# soundcard_v1_1.net
KiCad netlist of a schematic drawn in EAGLE
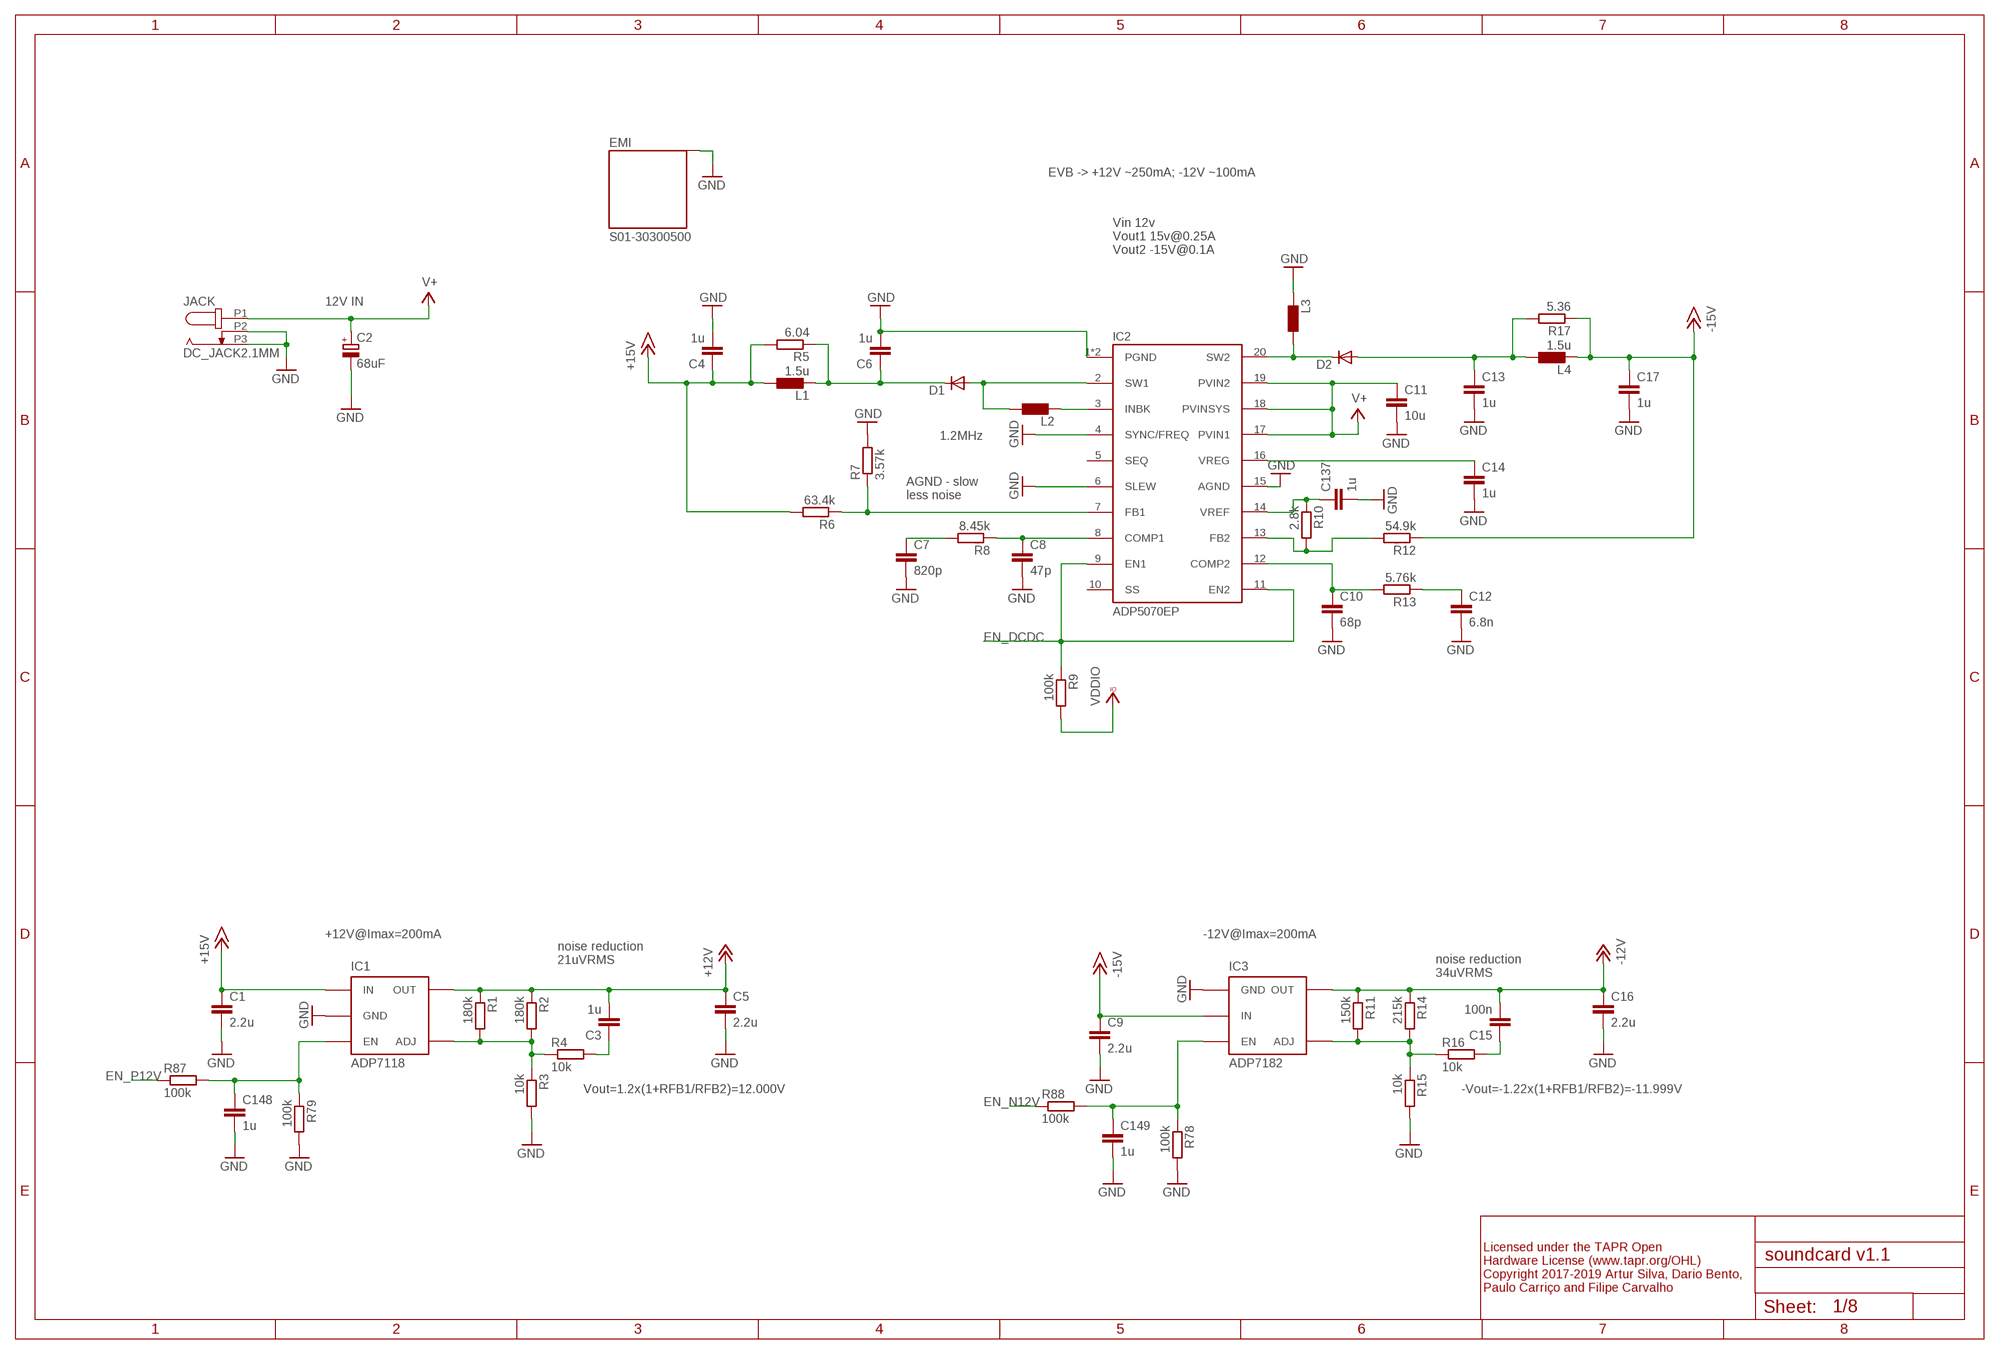
[diagram p0: schematic, sheet 1]
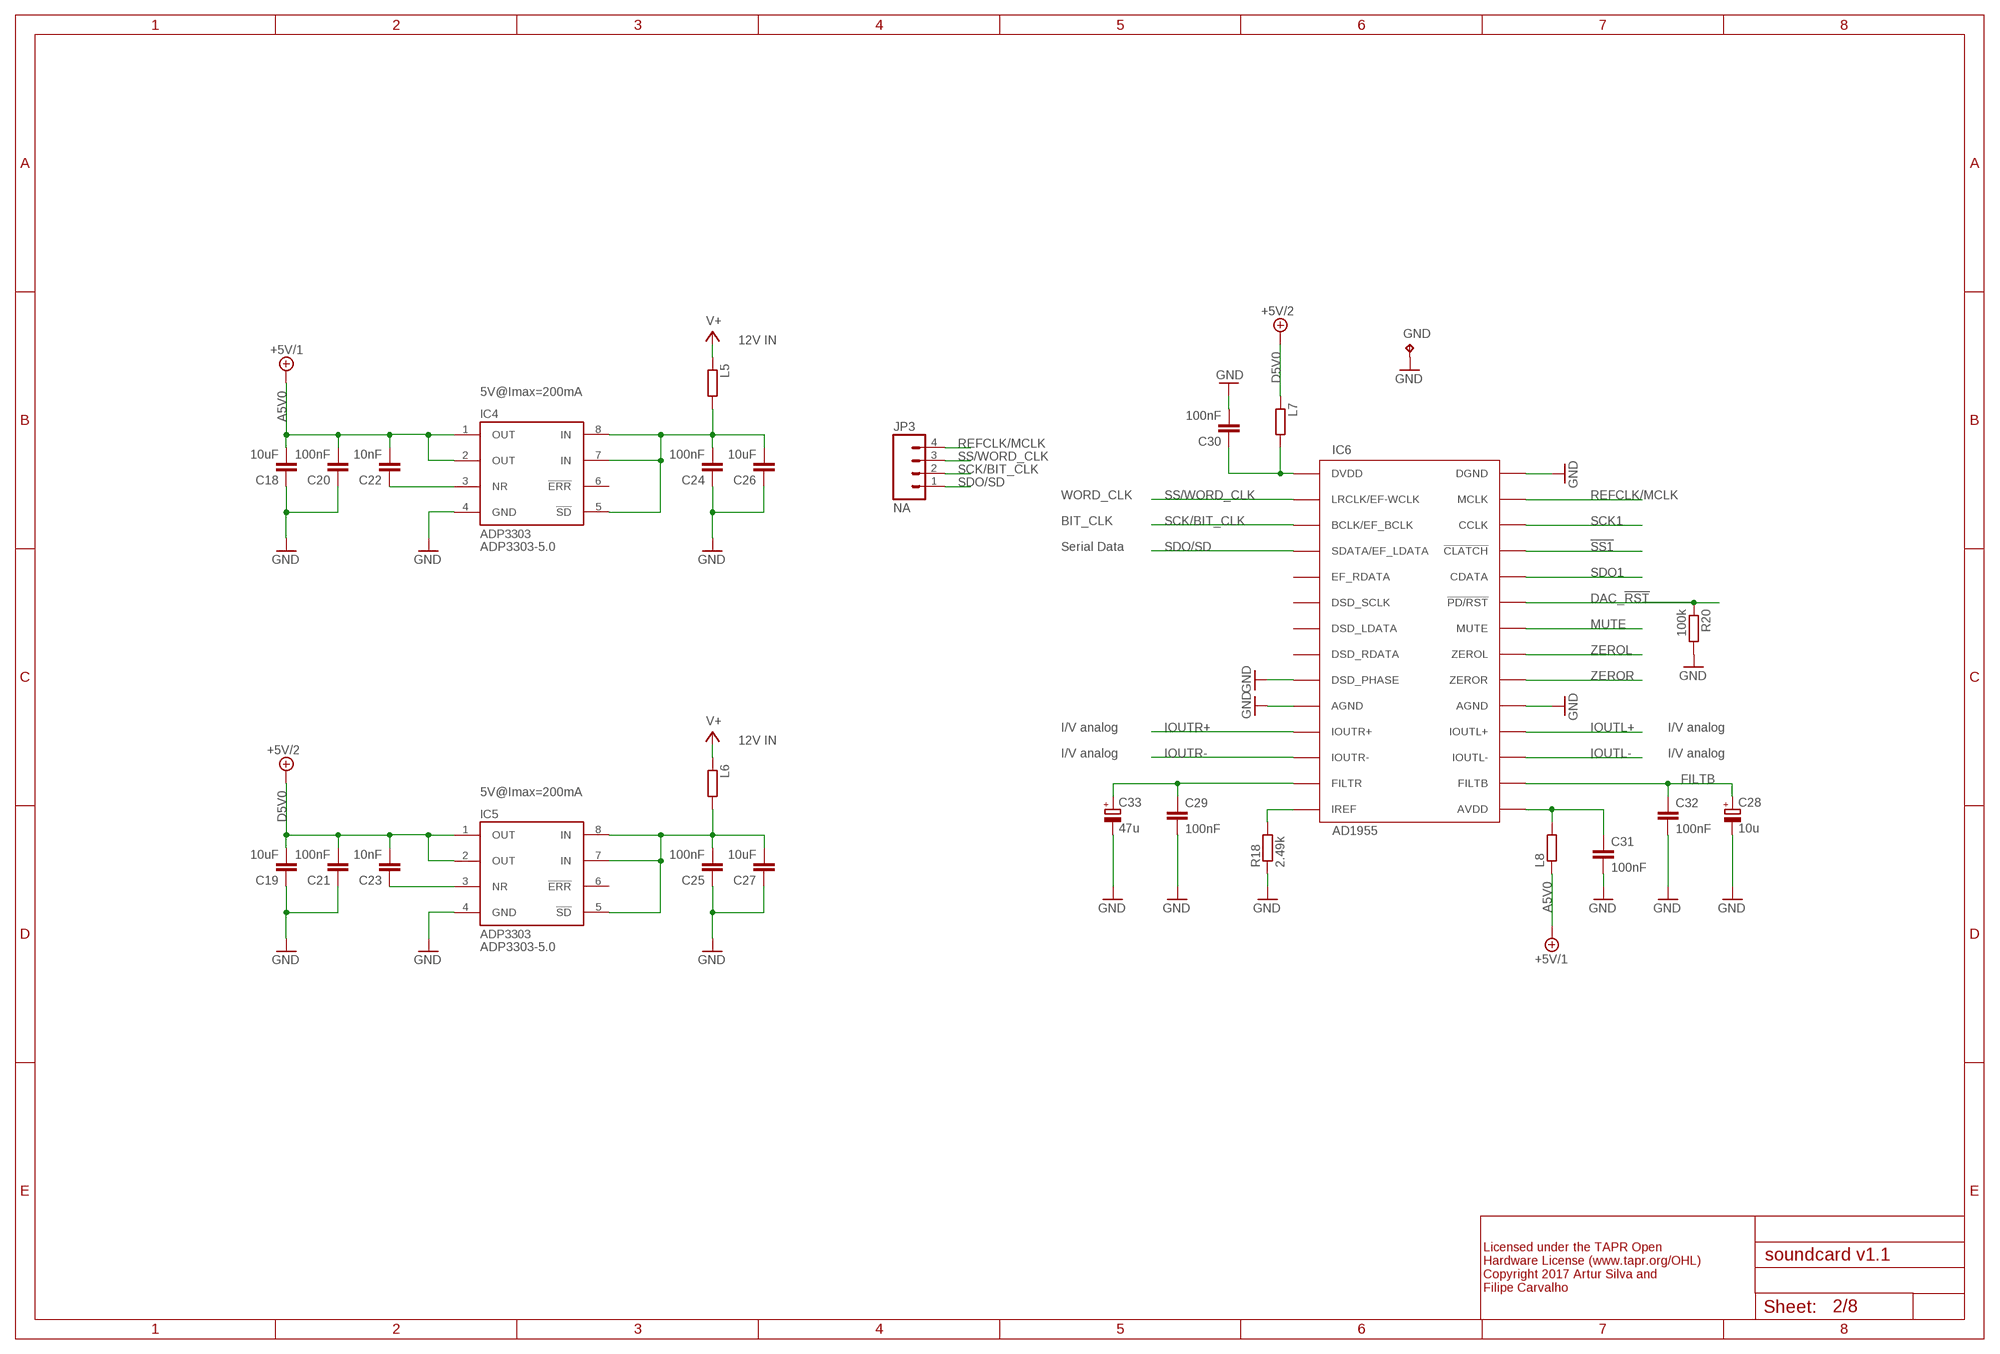
[diagram p1: schematic, sheet 2]
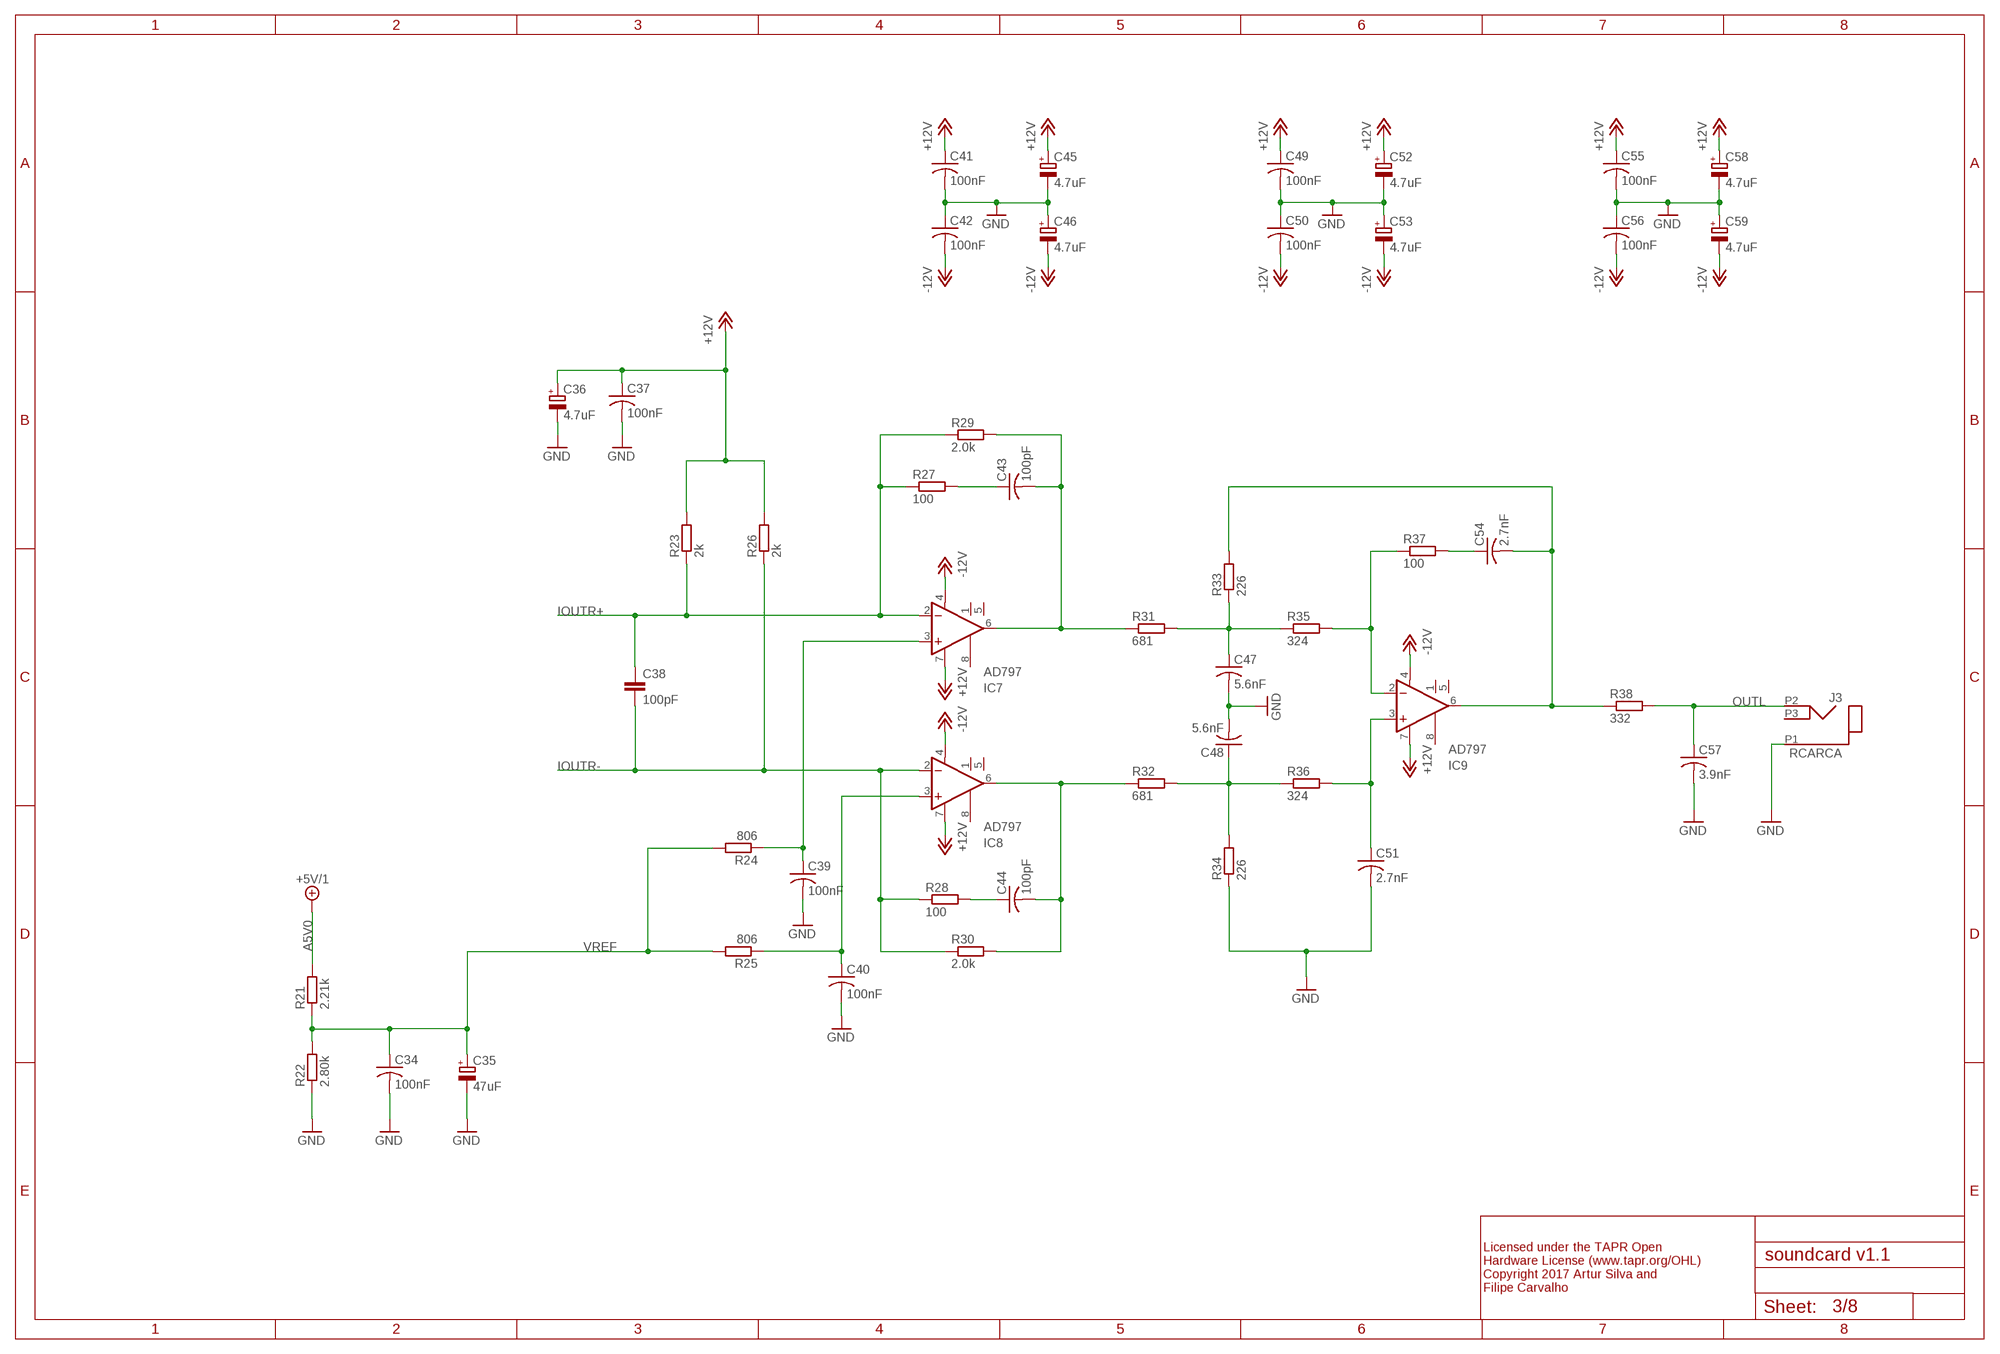
[diagram p2: schematic, sheet 3]
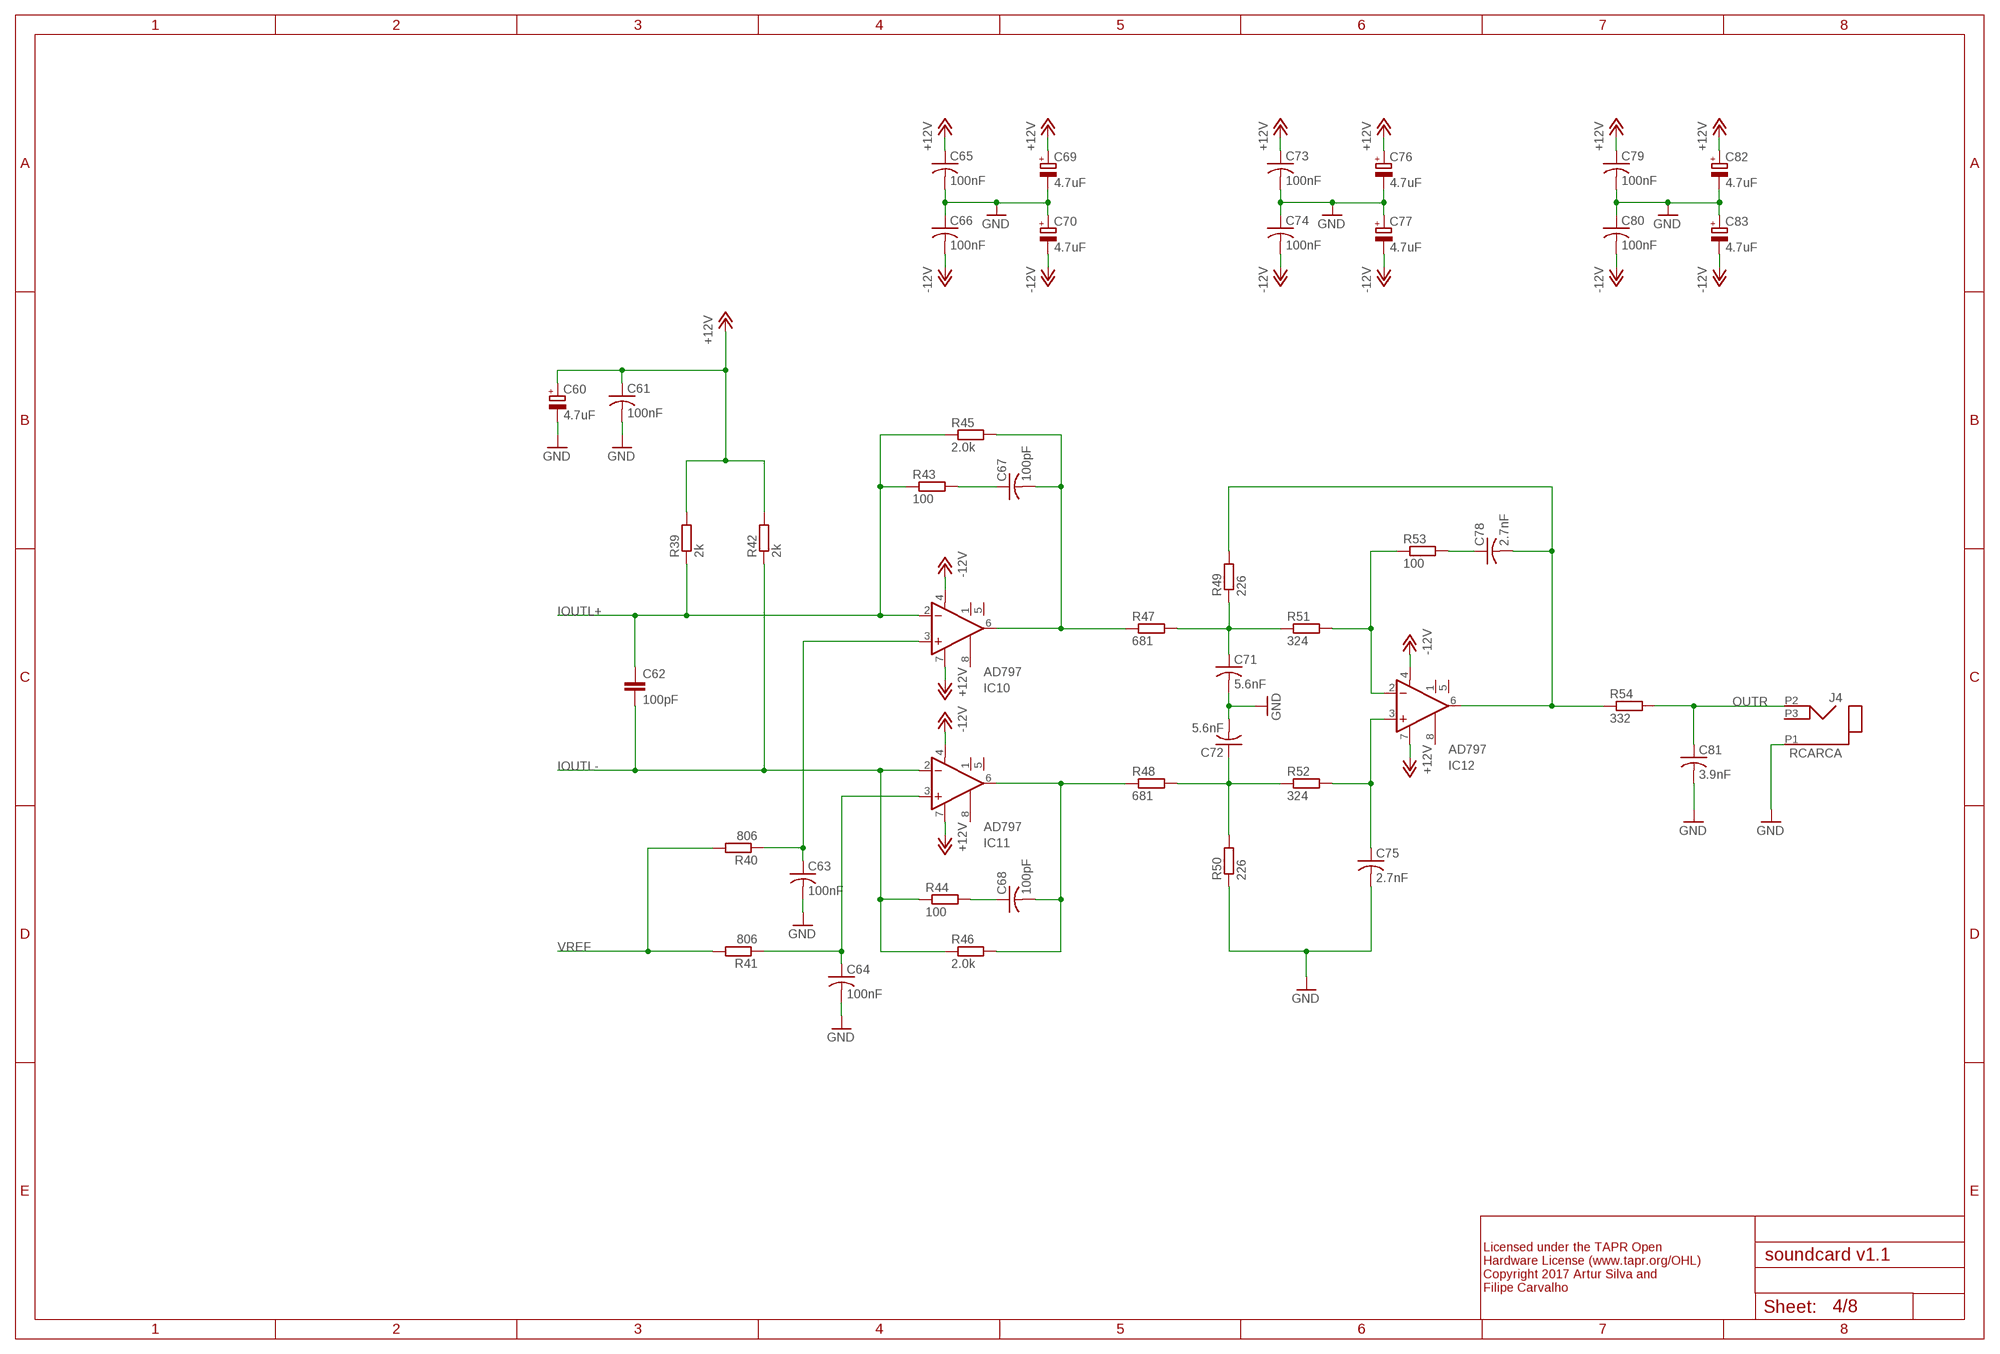
[diagram p3: schematic, sheet 4]
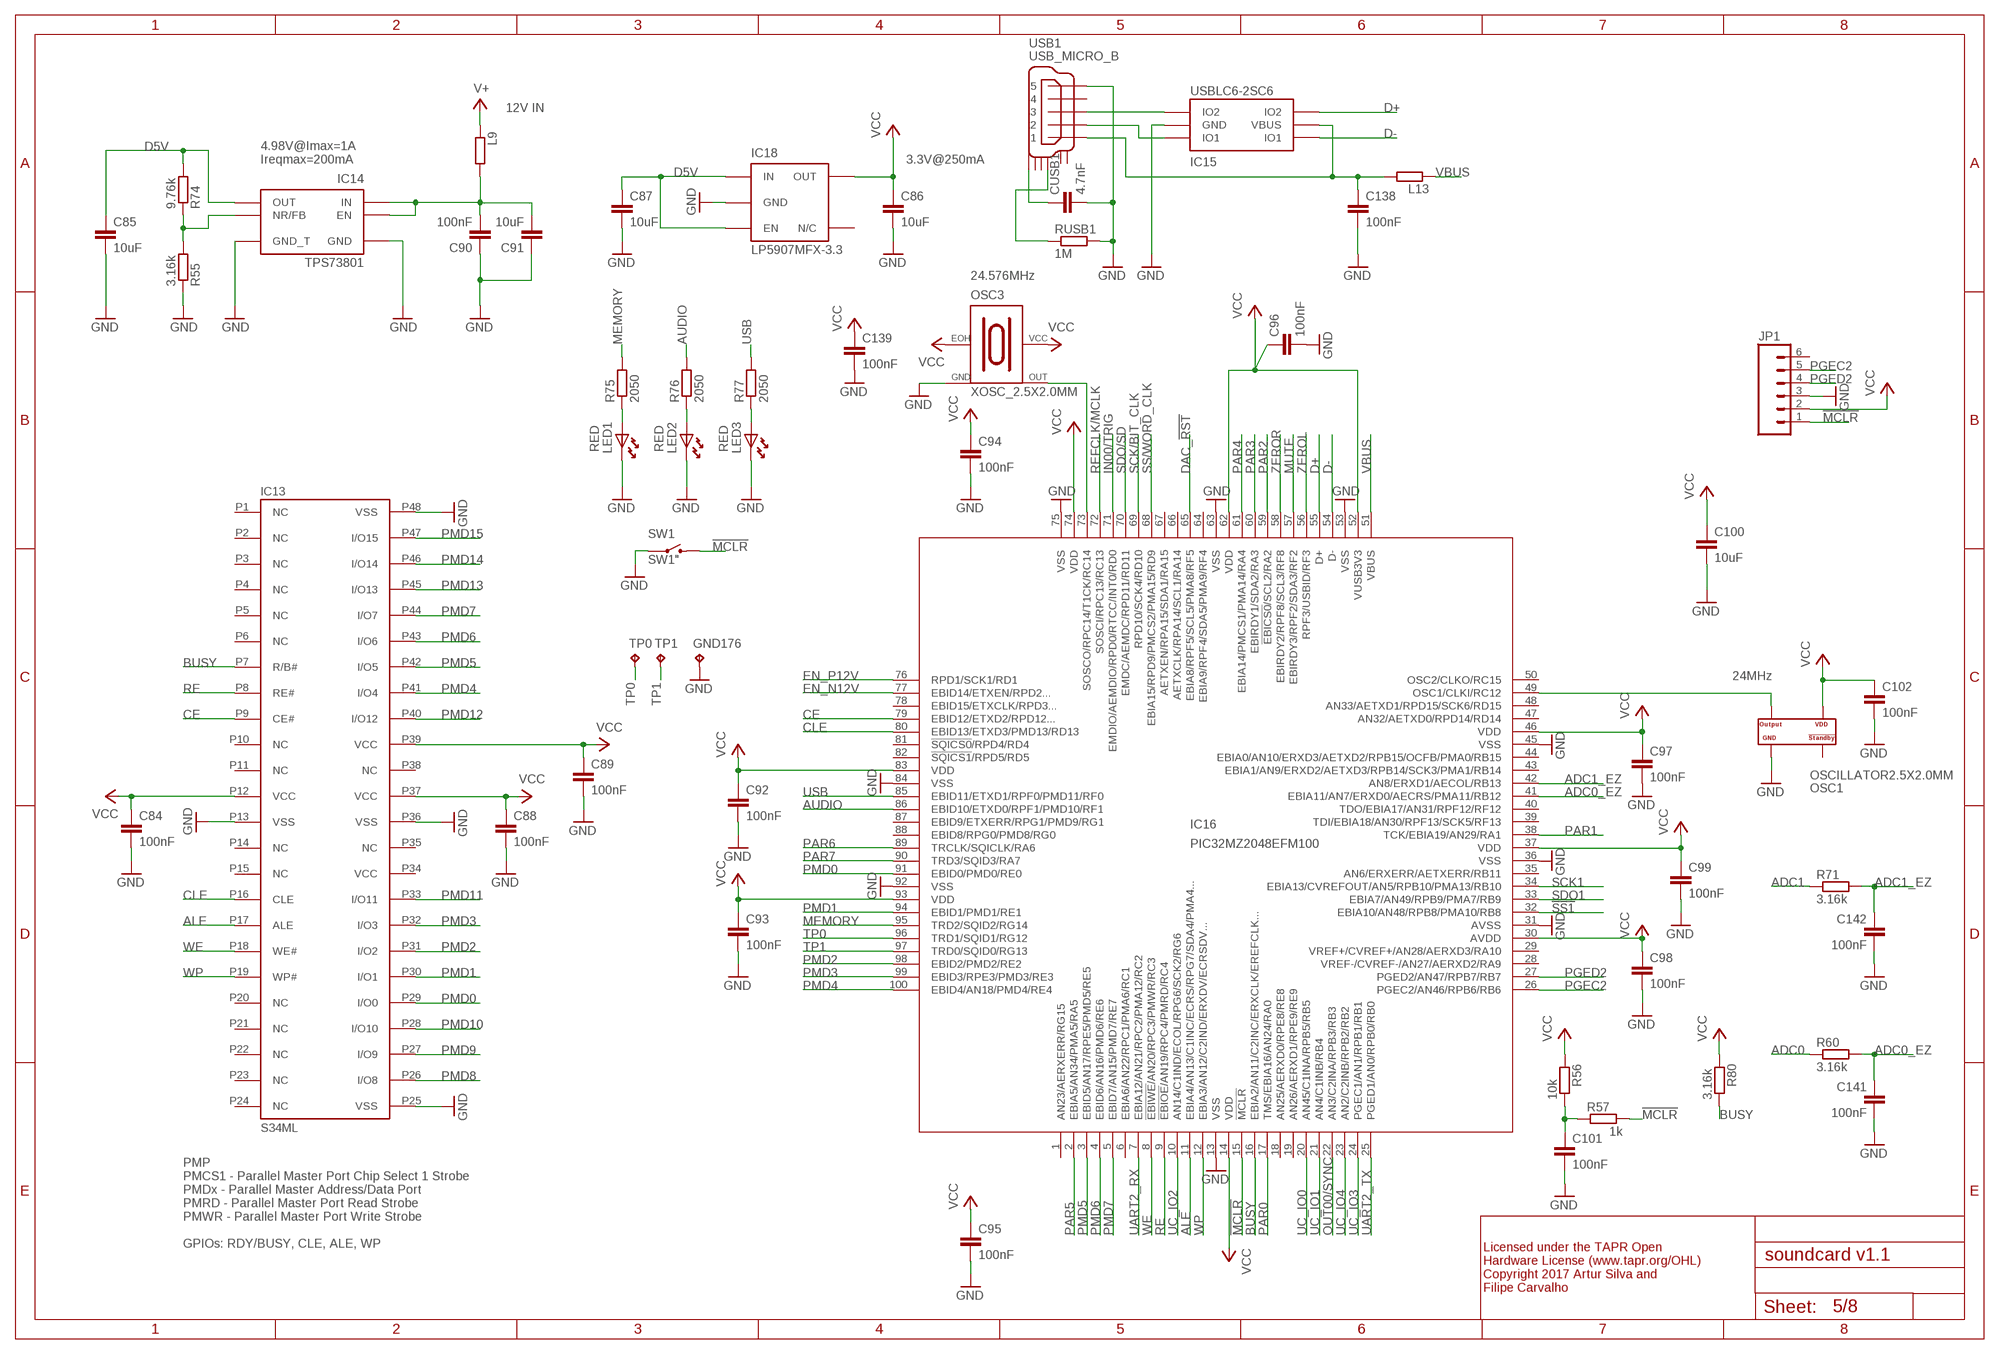
[diagram p4: schematic, sheet 5]
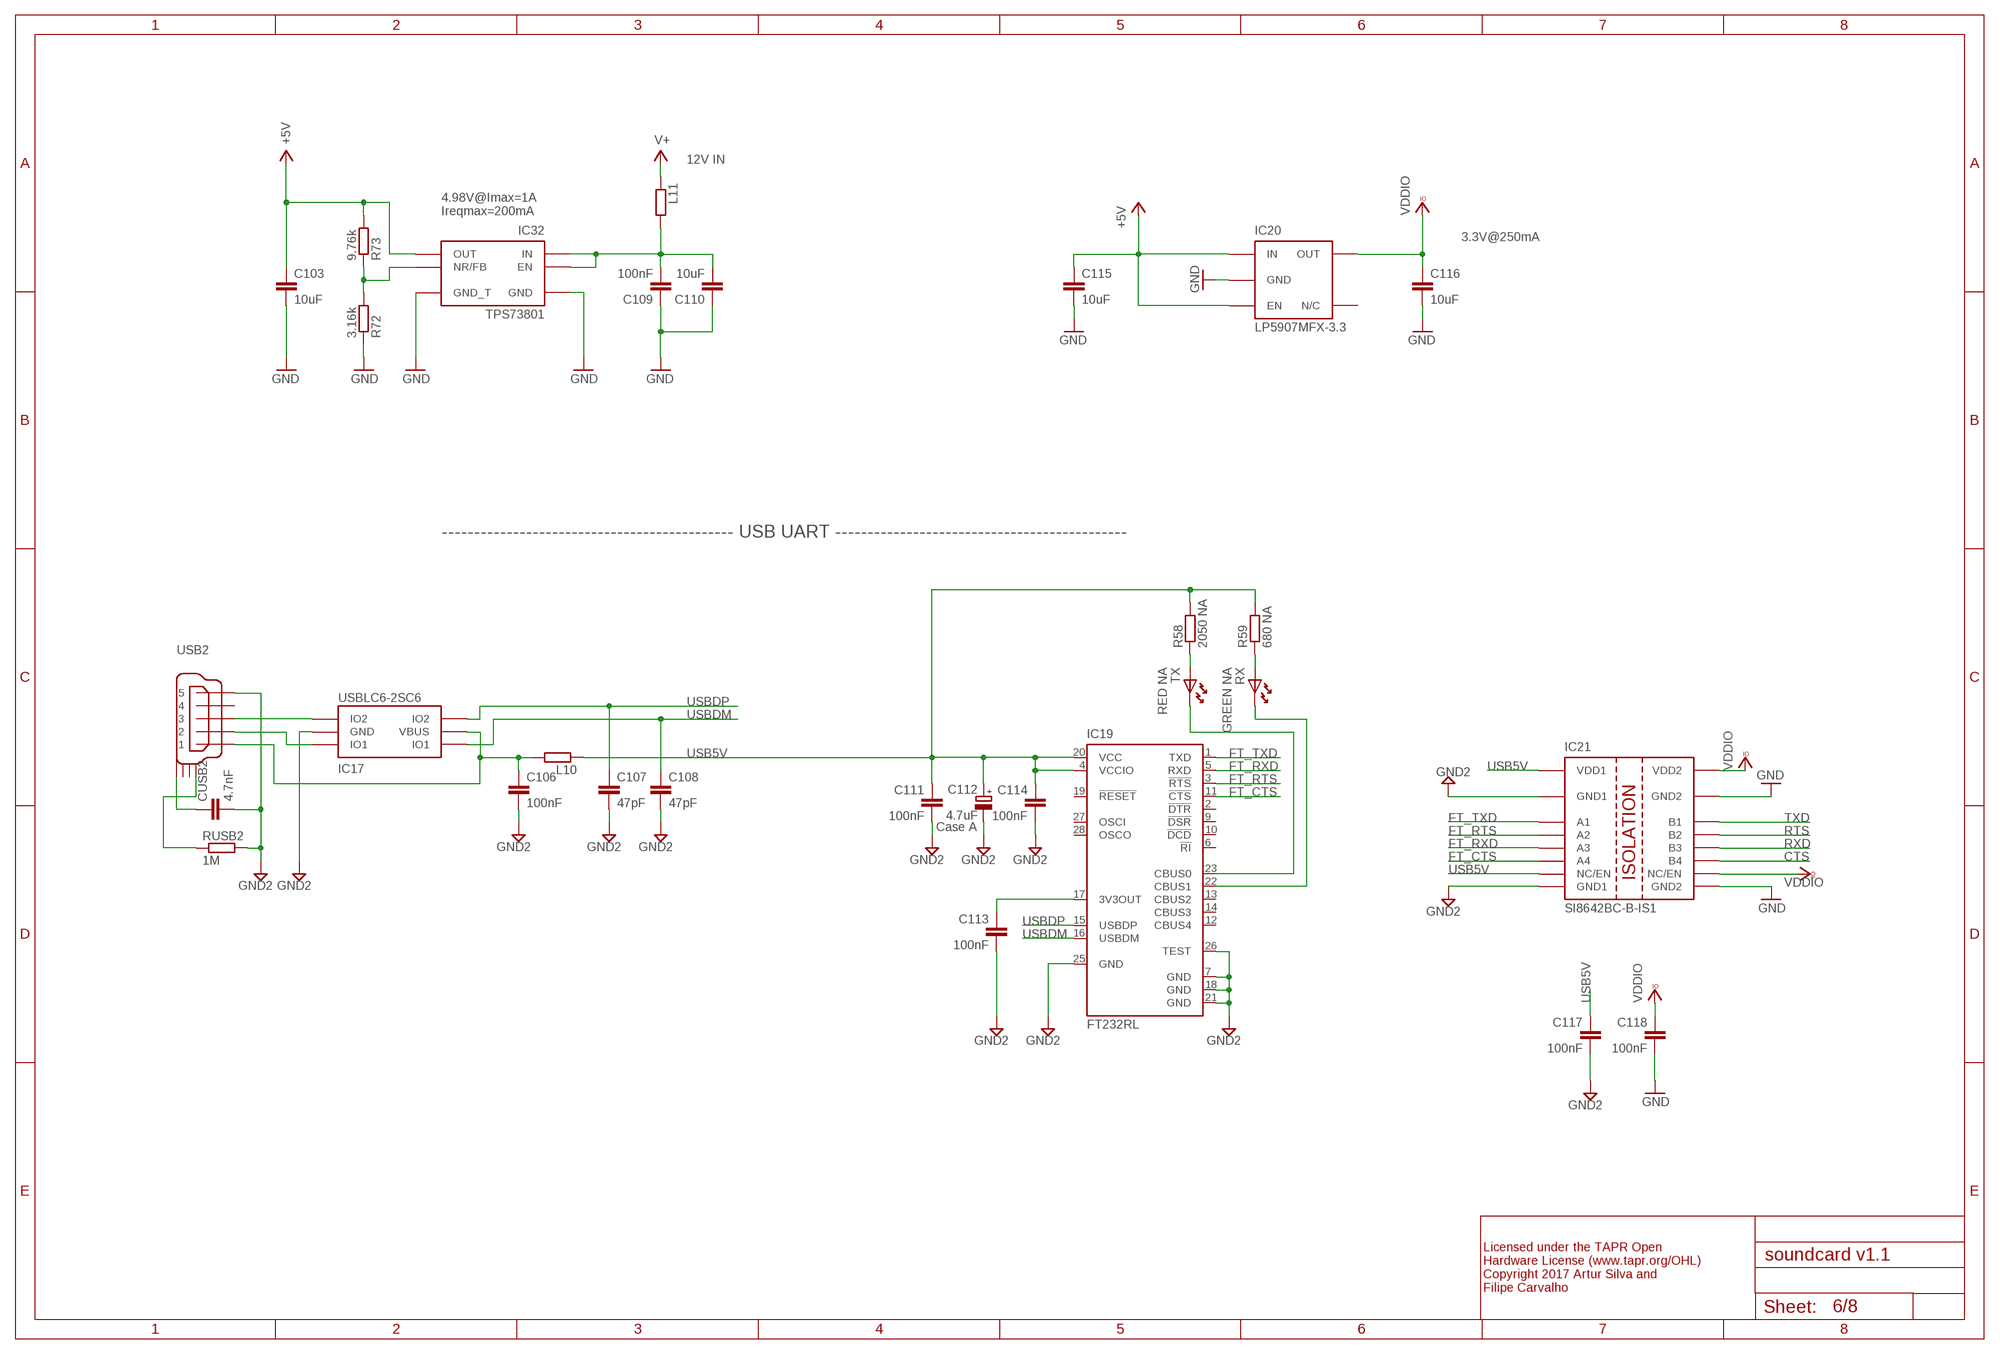
[diagram p5: schematic, sheet 6]
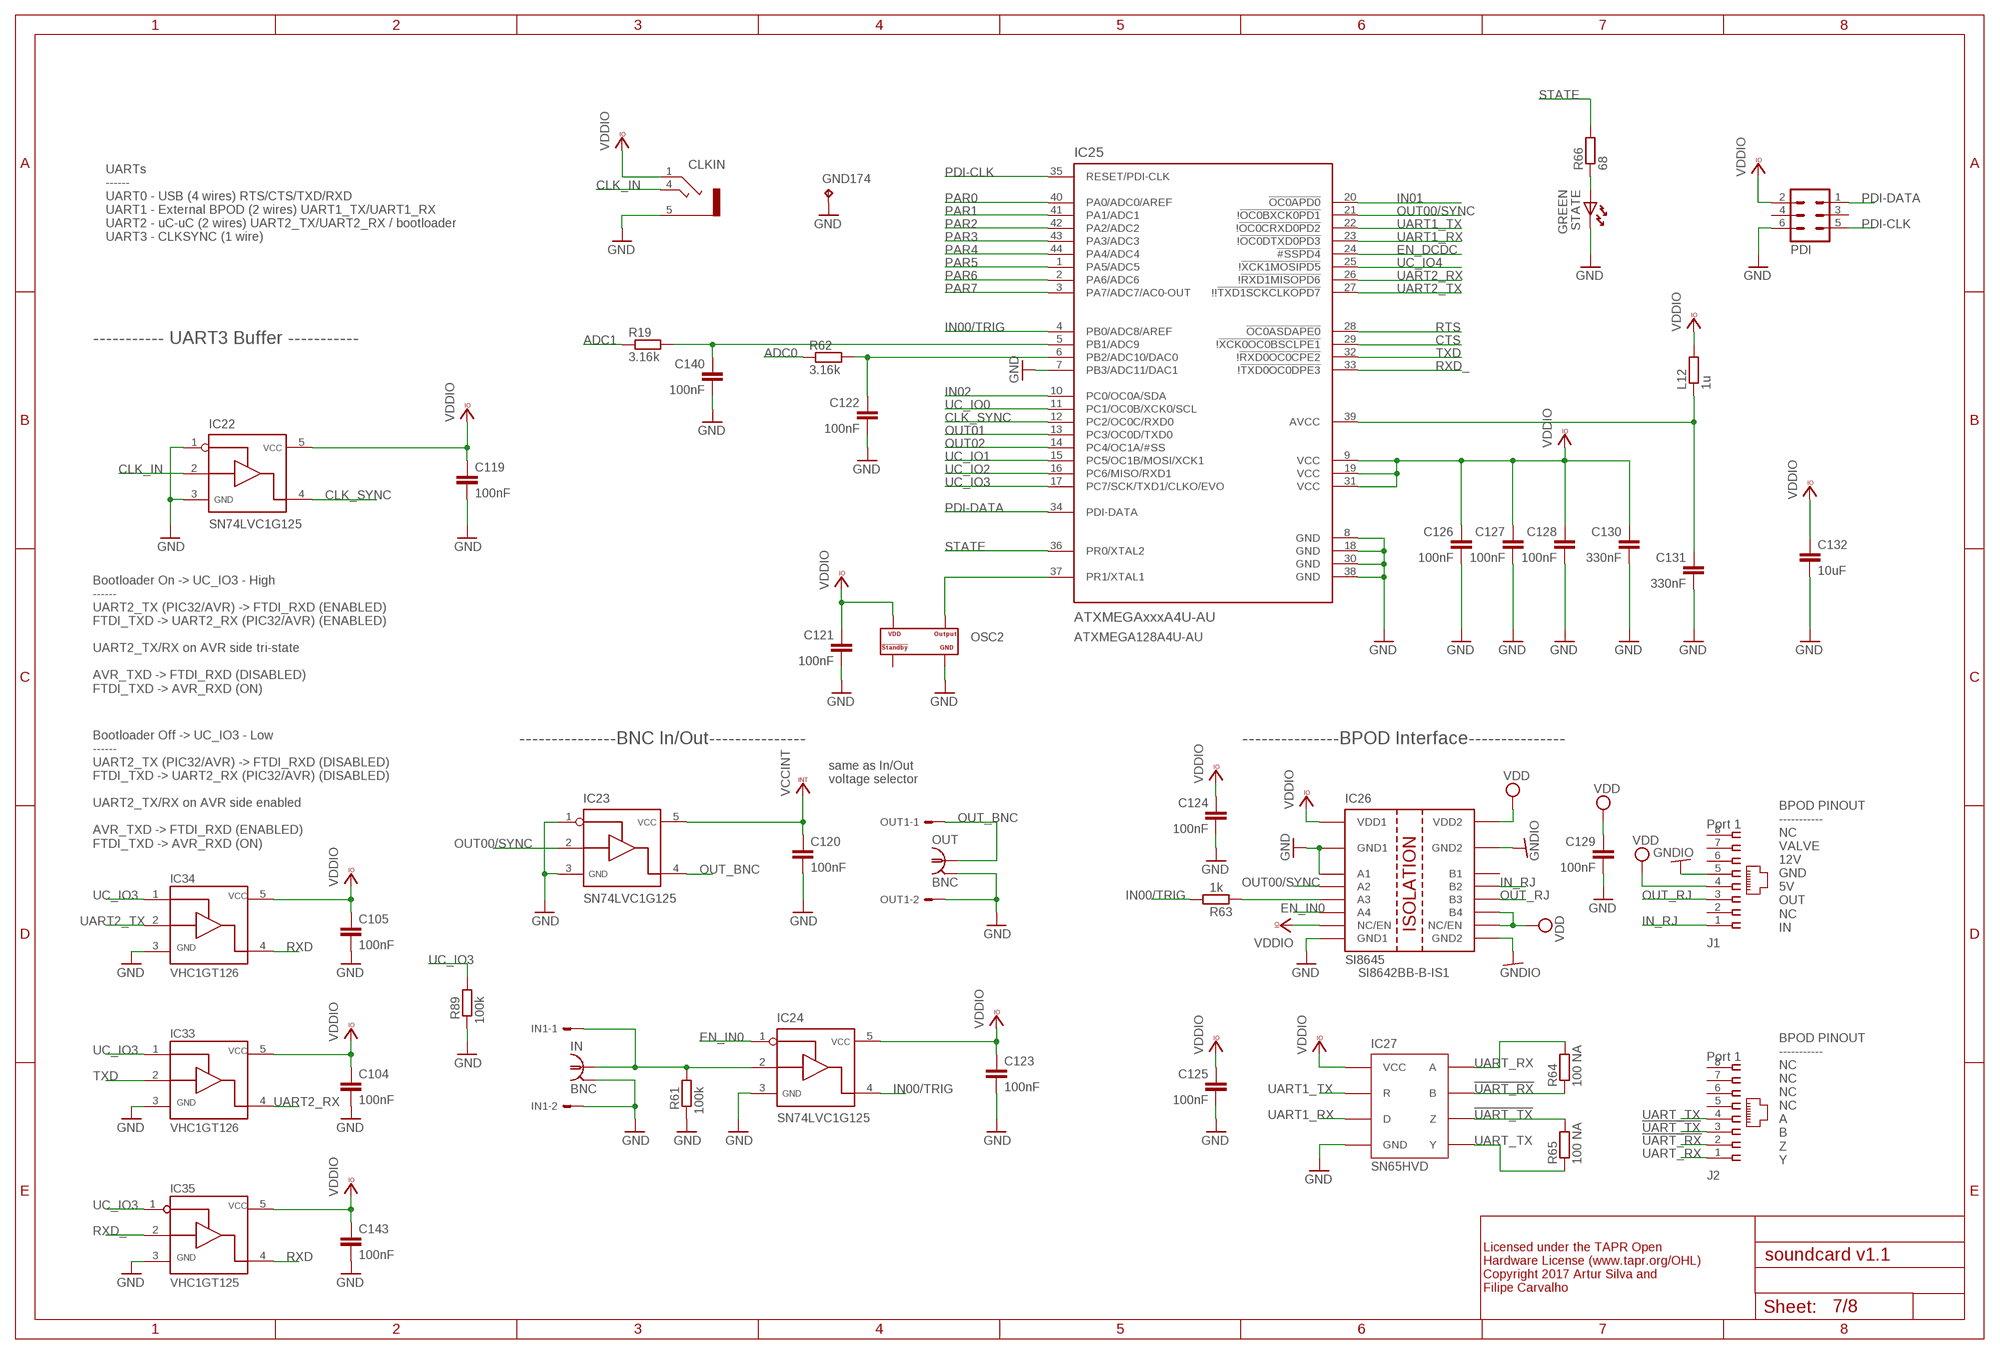
[diagram p6: schematic, sheet 7]
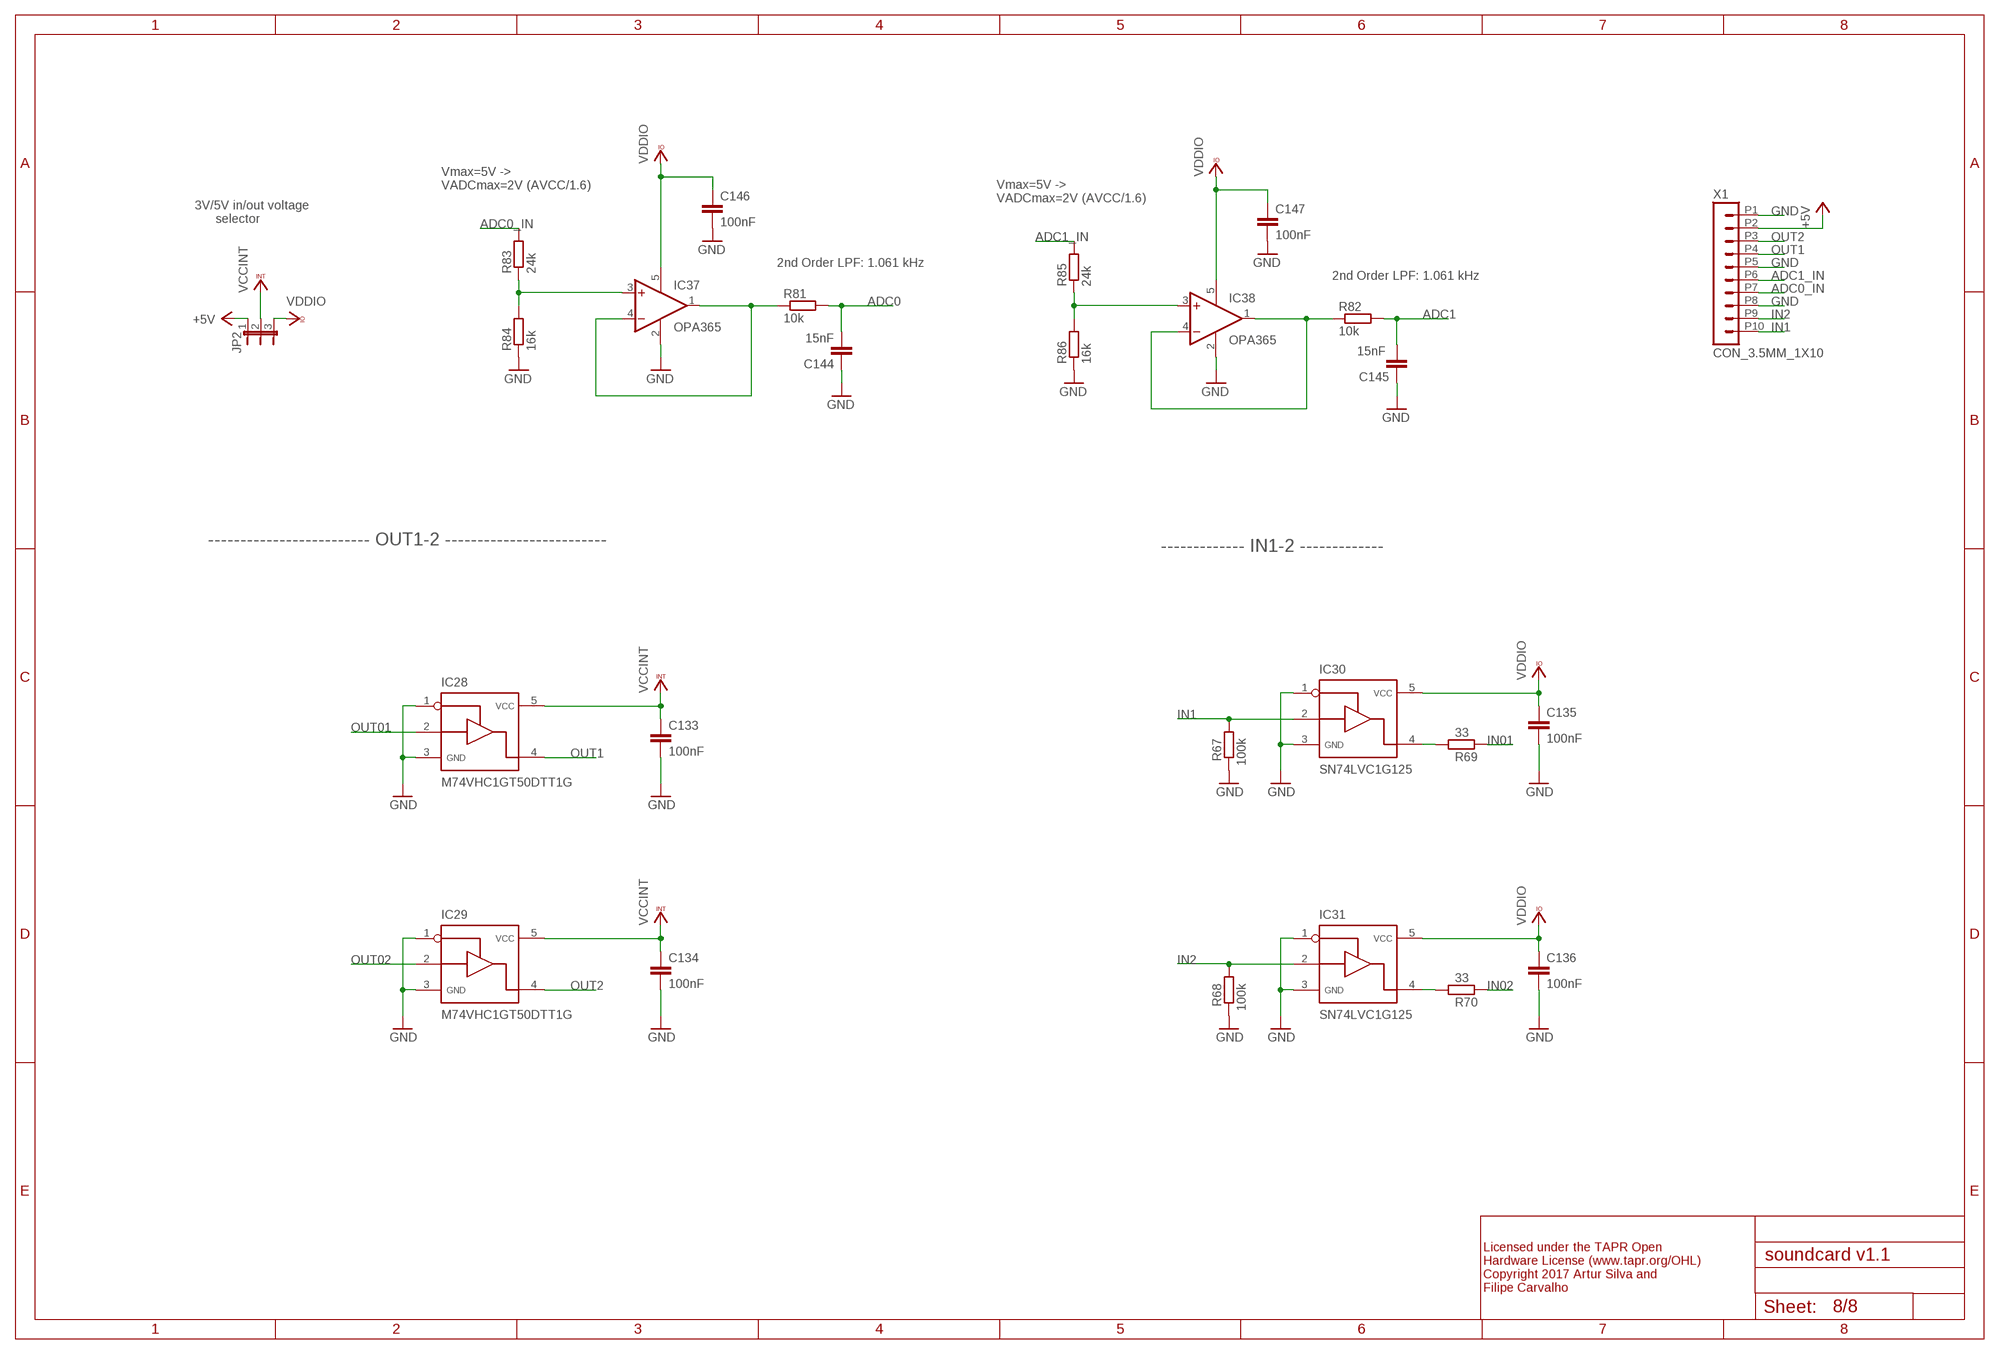
[diagram p7: schematic, sheet 8]

(export (version "E")
  (design (tool "Eeschema 10.0.6"))
  (components
    (comp (ref "C133")
      (value "100nF")
      (footprint "eagle-import:C0402")
      (libsource (lib "eagle-import") (part "C-EUC0402"))
    )
    (comp (ref "C134")
      (value "100nF")
      (footprint "eagle-import:C0402")
      (libsource (lib "eagle-import") (part "C-EUC0402"))
    )
    (comp (ref "C135")
      (value "100nF")
      (footprint "eagle-import:C0402")
      (libsource (lib "eagle-import") (part "C-EUC0402"))
    )
    (comp (ref "C136")
      (value "100nF")
      (footprint "eagle-import:C0402")
      (libsource (lib "eagle-import") (part "C-EUC0402"))
    )
    (comp (ref "C144")
      (value "15nF")
      (footprint "eagle-import:C0402")
      (libsource (lib "eagle-import") (part "C-EUC0402"))
    )
    (comp (ref "C145")
      (value "15nF")
      (footprint "eagle-import:C0402")
      (libsource (lib "eagle-import") (part "C-EUC0402"))
    )
    (comp (ref "C146")
      (value "100nF")
      (footprint "eagle-import:C0402")
      (libsource (lib "eagle-import") (part "C-EUC0402"))
    )
    (comp (ref "C147")
      (value "100nF")
      (footprint "eagle-import:C0402")
      (libsource (lib "eagle-import") (part "C-EUC0402"))
    )
    (comp (ref "IC28")
      (value "M74VHC1GT50DTT1G")
      (footprint "eagle-import:SOT23-5")
      (libsource (lib "eagle-import") (part "SN74LVC1G125"))
    )
    (comp (ref "IC29")
      (value "M74VHC1GT50DTT1G")
      (footprint "eagle-import:SOT23-5")
      (libsource (lib "eagle-import") (part "SN74LVC1G125"))
    )
    (comp (ref "IC30")
      (value "SN74LVC1G125")
      (footprint "eagle-import:SOT23-5")
      (libsource (lib "eagle-import") (part "SN74LVC1G125"))
    )
    (comp (ref "IC31")
      (value "SN74LVC1G125")
      (footprint "eagle-import:SOT23-5")
      (libsource (lib "eagle-import") (part "SN74LVC1G125"))
    )
    (comp (ref "IC37")
      (value "OPA365")
      (footprint "eagle-import:SOT23-5")
      (libsource (lib "eagle-import") (part "OPA365"))
    )
    (comp (ref "IC38")
      (value "OPA365")
      (footprint "eagle-import:SOT23-5")
      (libsource (lib "eagle-import") (part "OPA365"))
    )
    (comp (ref "JP2")
      (value "JP2E")
      (footprint "eagle-import:JP2")
      (libsource (lib "eagle-import") (part "JP2E"))
    )
    (comp (ref "R67")
      (value "100k")
      (footprint "eagle-import:R0402")
      (libsource (lib "eagle-import") (part "R-EU_R0402"))
    )
    (comp (ref "R68")
      (value "100k")
      (footprint "eagle-import:R0402")
      (libsource (lib "eagle-import") (part "R-EU_R0402"))
    )
    (comp (ref "R69")
      (value "33")
      (footprint "eagle-import:R0402")
      (libsource (lib "eagle-import") (part "R-EU_R0402"))
    )
    (comp (ref "R70")
      (value "33")
      (footprint "eagle-import:R0402")
      (libsource (lib "eagle-import") (part "R-EU_R0402"))
    )
    (comp (ref "R81")
      (value "10k")
      (footprint "eagle-import:R0402")
      (libsource (lib "eagle-import") (part "R-EU_R0402"))
    )
    (comp (ref "R82")
      (value "10k")
      (footprint "eagle-import:R0402")
      (libsource (lib "eagle-import") (part "R-EU_R0402"))
    )
    (comp (ref "R83")
      (value "24k")
      (footprint "eagle-import:R0402")
      (libsource (lib "eagle-import") (part "R-EU_R0402"))
    )
    (comp (ref "R84")
      (value "16k")
      (footprint "eagle-import:R0402")
      (libsource (lib "eagle-import") (part "R-EU_R0402"))
    )
    (comp (ref "R85")
      (value "24k")
      (footprint "eagle-import:R0402")
      (libsource (lib "eagle-import") (part "R-EU_R0402"))
    )
    (comp (ref "R86")
      (value "16k")
      (footprint "eagle-import:R0402")
      (libsource (lib "eagle-import") (part "R-EU_R0402"))
    )
    (comp (ref "X1")
      (value "CON_3.5MM_1X10")
      (footprint "eagle-import:CON_3.5MM_1X10")
      (libsource (lib "eagle-import") (part "CON_3.5MM_1X10"))
    )
    (comp (ref "C1")
      (value "2.2u")
      (footprint "eagle-import:C0603")
      (libsource (lib "eagle-import") (part "C-EUC0603"))
    )
    (comp (ref "C2")
      (value "68uF")
      (footprint "eagle-import:E2-5")
      (libsource (lib "eagle-import") (part "resistor_CPOL-EUE2-5"))
    )
    (comp (ref "C3")
      (value "1u")
      (footprint "eagle-import:C0402")
      (libsource (lib "eagle-import") (part "C-EUC0402"))
    )
    (comp (ref "C4")
      (value "1u")
      (footprint "eagle-import:C0603")
      (libsource (lib "eagle-import") (part "C-EUC0603"))
    )
    (comp (ref "C5")
      (value "2.2u")
      (footprint "eagle-import:C0603")
      (libsource (lib "eagle-import") (part "C-EUC0603"))
    )
    (comp (ref "C6")
      (value "1u")
      (footprint "eagle-import:C0603")
      (libsource (lib "eagle-import") (part "C-EUC0603"))
    )
    (comp (ref "C7")
      (value "820p")
      (footprint "eagle-import:C0402")
      (libsource (lib "eagle-import") (part "C-EUC0402"))
    )
    (comp (ref "C8")
      (value "47p")
      (footprint "eagle-import:C0402")
      (libsource (lib "eagle-import") (part "C-EUC0402"))
    )
    (comp (ref "C9")
      (value "2.2u")
      (footprint "eagle-import:C0603")
      (libsource (lib "eagle-import") (part "C-EUC0603"))
    )
    (comp (ref "C10")
      (value "68p")
      (footprint "eagle-import:C0402")
      (libsource (lib "eagle-import") (part "C-EUC0402"))
    )
    (comp (ref "C11")
      (value "10u")
      (footprint "eagle-import:C1206")
      (libsource (lib "eagle-import") (part "C-EUC1206"))
    )
    (comp (ref "C12")
      (value "6.8n")
      (footprint "eagle-import:C0402")
      (libsource (lib "eagle-import") (part "C-EUC0402"))
    )
    (comp (ref "C13")
      (value "1u")
      (footprint "eagle-import:C0603")
      (libsource (lib "eagle-import") (part "C-EUC0603"))
    )
    (comp (ref "C14")
      (value "1u")
      (footprint "eagle-import:C0402")
      (libsource (lib "eagle-import") (part "C-EUC0402"))
    )
    (comp (ref "C15")
      (value "100n")
      (footprint "eagle-import:C0402")
      (libsource (lib "eagle-import") (part "C-EUC0402"))
    )
    (comp (ref "C16")
      (value "2.2u")
      (footprint "eagle-import:C0603")
      (libsource (lib "eagle-import") (part "C-EUC0603"))
    )
    (comp (ref "C17")
      (value "1u")
      (footprint "eagle-import:C0603")
      (libsource (lib "eagle-import") (part "C-EUC0603"))
    )
    (comp (ref "C137")
      (value "1u")
      (footprint "eagle-import:C0402")
      (libsource (lib "eagle-import") (part "C-EUC0402"))
    )
    (comp (ref "C148")
      (value "1u")
      (footprint "eagle-import:C0603")
      (libsource (lib "eagle-import") (part "C-EUC0603"))
    )
    (comp (ref "C149")
      (value "1u")
      (footprint "eagle-import:C0603")
      (libsource (lib "eagle-import") (part "C-EUC0603"))
    )
    (comp (ref "D1")
      (value "DIODE-SOD323-R")
      (footprint "eagle-import:SOD323-R")
      (libsource (lib "eagle-import") (part "DIODE-SOD323-R"))
    )
    (comp (ref "D2")
      (value "DIODE-SOD323-R")
      (footprint "eagle-import:SOD323-R")
      (libsource (lib "eagle-import") (part "DIODE-SOD323-R"))
    )
    (comp (ref "EMI")
      (value "S01-30300500")
      (footprint "eagle-import:S01-30300500")
      (libsource (lib "eagle-import") (part "S01-30300500"))
    )
    (comp (ref "IC1")
      (value "ADP7118")
      (footprint "eagle-import:TSOT23-5")
      (libsource (lib "eagle-import") (part "ADP7118"))
    )
    (comp (ref "IC2")
      (value "ADP5070EP")
      (footprint "eagle-import:TSSOP-EP-20")
      (libsource (lib "eagle-import") (part "ADP5070EP"))
    )
    (comp (ref "IC3")
      (value "ADP7182")
      (footprint "eagle-import:TSOT23-5")
      (libsource (lib "eagle-import") (part "ADP7182"))
    )
    (comp (ref "JACK")
      (value "DC_JACK2.1MM")
      (footprint "eagle-import:DC_POWER_INPUT_2.1MM")
      (libsource (lib "eagle-import") (part "DC_JACK2.1MM"))
    )
    (comp (ref "L1")
      (value "1.5u")
      (footprint "eagle-import:IND_LPS4012")
      (libsource (lib "eagle-import") (part "INDLPS4012"))
    )
    (comp (ref "L2")
      (value "INDLPS6225")
      (footprint "eagle-import:IND_LPS6225")
      (libsource (lib "eagle-import") (part "INDLPS6225"))
    )
    (comp (ref "L3")
      (value "INDLPS6225")
      (footprint "eagle-import:IND_LPS6225")
      (libsource (lib "eagle-import") (part "INDLPS6225"))
    )
    (comp (ref "L4")
      (value "1.5u")
      (footprint "eagle-import:IND_LPS4012")
      (libsource (lib "eagle-import") (part "INDLPS4012"))
    )
    (comp (ref "R1")
      (value "180k")
      (footprint "eagle-import:R0402")
      (libsource (lib "eagle-import") (part "R-EU_R0402"))
    )
    (comp (ref "R2")
      (value "180k")
      (footprint "eagle-import:R0402")
      (libsource (lib "eagle-import") (part "R-EU_R0402"))
    )
    (comp (ref "R3")
      (value "10k")
      (footprint "eagle-import:R0402")
      (libsource (lib "eagle-import") (part "R-EU_R0402"))
    )
    (comp (ref "R4")
      (value "10k")
      (footprint "eagle-import:R0402")
      (libsource (lib "eagle-import") (part "R-EU_R0402"))
    )
    (comp (ref "R5")
      (value "6.04")
      (footprint "eagle-import:R0402")
      (libsource (lib "eagle-import") (part "R-EU_R0402"))
    )
    (comp (ref "R6")
      (value "63.4k")
      (footprint "eagle-import:R0402")
      (libsource (lib "eagle-import") (part "R-EU_R0402"))
    )
    (comp (ref "R7")
      (value "3.57k")
      (footprint "eagle-import:R0402")
      (libsource (lib "eagle-import") (part "R-EU_R0402"))
    )
    (comp (ref "R8")
      (value "8.45k")
      (footprint "eagle-import:R0402")
      (libsource (lib "eagle-import") (part "R-EU_R0402"))
    )
    (comp (ref "R9")
      (value "100k")
      (footprint "eagle-import:R0402")
      (libsource (lib "eagle-import") (part "R-EU_R0402"))
    )
    (comp (ref "R10")
      (value "2.8k")
      (footprint "eagle-import:R0402")
      (libsource (lib "eagle-import") (part "R-EU_R0402"))
    )
    (comp (ref "R11")
      (value "150k")
      (footprint "eagle-import:R0402")
      (libsource (lib "eagle-import") (part "R-EU_R0402"))
    )
    (comp (ref "R12")
      (value "54.9k")
      (footprint "eagle-import:R0402")
      (libsource (lib "eagle-import") (part "R-EU_R0402"))
    )
    (comp (ref "R13")
      (value "5.76k")
      (footprint "eagle-import:R0402")
      (libsource (lib "eagle-import") (part "R-EU_R0402"))
    )
    (comp (ref "R14")
      (value "215k")
      (footprint "eagle-import:R0402")
      (libsource (lib "eagle-import") (part "R-EU_R0402"))
    )
    (comp (ref "R15")
      (value "10k")
      (footprint "eagle-import:R0402")
      (libsource (lib "eagle-import") (part "R-EU_R0402"))
    )
    (comp (ref "R16")
      (value "10k")
      (footprint "eagle-import:R0402")
      (libsource (lib "eagle-import") (part "R-EU_R0402"))
    )
    (comp (ref "R17")
      (value "5.36")
      (footprint "eagle-import:R0402")
      (libsource (lib "eagle-import") (part "R-EU_R0402"))
    )
    (comp (ref "R78")
      (value "100k")
      (footprint "eagle-import:R0402")
      (libsource (lib "eagle-import") (part "R-EU_R0402"))
    )
    (comp (ref "R79")
      (value "100k")
      (footprint "eagle-import:R0402")
      (libsource (lib "eagle-import") (part "R-EU_R0402"))
    )
    (comp (ref "R87")
      (value "100k")
      (footprint "eagle-import:R0402")
      (libsource (lib "eagle-import") (part "R-EU_R0402"))
    )
    (comp (ref "R88")
      (value "100k")
      (footprint "eagle-import:R0402")
      (libsource (lib "eagle-import") (part "R-EU_R0402"))
    )
    (comp (ref "C18")
      (value "10uF")
      (footprint "eagle-import:C0603")
      (libsource (lib "eagle-import") (part "C-EUC0603"))
    )
    (comp (ref "C19")
      (value "10uF")
      (footprint "eagle-import:C0603")
      (libsource (lib "eagle-import") (part "C-EUC0603"))
    )
    (comp (ref "C20")
      (value "100nF")
      (footprint "eagle-import:C0402")
      (libsource (lib "eagle-import") (part "C-EUC0402"))
    )
    (comp (ref "C21")
      (value "100nF")
      (footprint "eagle-import:C0402")
      (libsource (lib "eagle-import") (part "C-EUC0402"))
    )
    (comp (ref "C22")
      (value "10nF")
      (footprint "eagle-import:C0402")
      (libsource (lib "eagle-import") (part "C-EUC0402"))
    )
    (comp (ref "C23")
      (value "10nF")
      (footprint "eagle-import:C0402")
      (libsource (lib "eagle-import") (part "C-EUC0402"))
    )
    (comp (ref "C24")
      (value "100nF")
      (footprint "eagle-import:C0402")
      (libsource (lib "eagle-import") (part "C-EUC0402"))
    )
    (comp (ref "C25")
      (value "100nF")
      (footprint "eagle-import:C0402")
      (libsource (lib "eagle-import") (part "C-EUC0402"))
    )
    (comp (ref "C26")
      (value "10uF")
      (footprint "eagle-import:C0603")
      (libsource (lib "eagle-import") (part "C-EUC0603"))
    )
    (comp (ref "C27")
      (value "10uF")
      (footprint "eagle-import:C0603")
      (libsource (lib "eagle-import") (part "C-EUC0603"))
    )
    (comp (ref "C28")
      (value "10u")
      (footprint "eagle-import:B_3528-21W")
      (libsource (lib "eagle-import") (part "CPOL-EUB/3528-21W"))
    )
    (comp (ref "C29")
      (value "100nF")
      (footprint "eagle-import:C0402")
      (libsource (lib "eagle-import") (part "C-EUC0402"))
    )
    (comp (ref "C30")
      (value "100nF")
      (footprint "eagle-import:C0402")
      (libsource (lib "eagle-import") (part "C-EUC0402"))
    )
    (comp (ref "C31")
      (value "100nF")
      (footprint "eagle-import:C0402")
      (libsource (lib "eagle-import") (part "C-EUC0402"))
    )
    (comp (ref "C32")
      (value "100nF")
      (footprint "eagle-import:C0402")
      (libsource (lib "eagle-import") (part "C-EUC0402"))
    )
    (comp (ref "C33")
      (value "47u")
      (footprint "eagle-import:C_6032-28W")
      (libsource (lib "eagle-import") (part "CPOL-EUC/6032-28W"))
    )
    (comp (ref "GND")
      (value "TP")
      (footprint "eagle-import:TP_1")
      (libsource (lib "eagle-import") (part "TP"))
    )
    (comp (ref "IC4")
      (value "ADP3303")
      (footprint "eagle-import:SO08")
      (libsource (lib "eagle-import") (part "ADP3303"))
    )
    (comp (ref "IC5")
      (value "ADP3303")
      (footprint "eagle-import:SO08")
      (libsource (lib "eagle-import") (part "ADP3303"))
    )
    (comp (ref "IC6")
      (value "AD1955")
      (footprint "eagle-import:SSOP28")
      (libsource (lib "eagle-import") (part "AD1955"))
    )
    (comp (ref "JP3")
      (value "NA")
      (footprint "eagle-import:1X04_NO_SILK")
      (libsource (lib "eagle-import") (part "M041X04_NO_SILK"))
    )
    (comp (ref "L5")
      (value "600@100M")
      (footprint "eagle-import:R0805")
      (libsource (lib "eagle-import") (part "R-EU_R0805"))
    )
    (comp (ref "L6")
      (value "600@100M")
      (footprint "eagle-import:R0805")
      (libsource (lib "eagle-import") (part "R-EU_R0805"))
    )
    (comp (ref "L7")
      (value "600@100M")
      (footprint "eagle-import:R0805")
      (libsource (lib "eagle-import") (part "R-EU_R0805"))
    )
    (comp (ref "L8")
      (value "600@100M")
      (footprint "eagle-import:R0805")
      (libsource (lib "eagle-import") (part "R-EU_R0805"))
    )
    (comp (ref "R18")
      (value "2.49k")
      (footprint "eagle-import:0207_12")
      (libsource (lib "eagle-import") (part "resistor_R-EU_0207/12"))
    )
    (comp (ref "R20")
      (value "100k")
      (footprint "eagle-import:R0402")
      (libsource (lib "eagle-import") (part "R-EU_R0402"))
    )
    (comp (ref "C60")
      (value "4.7uF")
      (footprint "eagle-import:E2-5")
      (libsource (lib "eagle-import") (part "resistor_CPOL-EUE2-5"))
    )
    (comp (ref "C61")
      (value "100nF")
      (footprint "eagle-import:C050-025X075")
      (libsource (lib "eagle-import") (part "C-US050-025X075"))
    )
    (comp (ref "C62")
      (value "100pF")
      (footprint "eagle-import:C0603")
      (libsource (lib "eagle-import") (part "C-EUC0603"))
    )
    (comp (ref "C63")
      (value "100nF")
      (footprint "eagle-import:C050-025X075")
      (libsource (lib "eagle-import") (part "C-US050-025X075"))
    )
    (comp (ref "C64")
      (value "100nF")
      (footprint "eagle-import:C050-025X075")
      (libsource (lib "eagle-import") (part "C-US050-025X075"))
    )
    (comp (ref "C65")
      (value "100nF")
      (footprint "eagle-import:C050-025X075")
      (libsource (lib "eagle-import") (part "C-US050-025X075"))
    )
    (comp (ref "C66")
      (value "100nF")
      (footprint "eagle-import:C050-025X075")
      (libsource (lib "eagle-import") (part "C-US050-025X075"))
    )
    (comp (ref "C67")
      (value "100pF")
      (footprint "eagle-import:C050-025X075")
      (libsource (lib "eagle-import") (part "C-US050-025X075"))
    )
    (comp (ref "C68")
      (value "100pF")
      (footprint "eagle-import:C050-025X075")
      (libsource (lib "eagle-import") (part "C-US050-025X075"))
    )
    (comp (ref "C69")
      (value "4.7uF")
      (footprint "eagle-import:E2-5")
      (libsource (lib "eagle-import") (part "resistor_CPOL-EUE2-5"))
    )
    (comp (ref "C70")
      (value "4.7uF")
      (footprint "eagle-import:E2-5")
      (libsource (lib "eagle-import") (part "resistor_CPOL-EUE2-5"))
    )
    (comp (ref "C71")
      (value "5.6nF")
      (footprint "eagle-import:C050-025X075")
      (libsource (lib "eagle-import") (part "C-US050-025X075"))
    )
    (comp (ref "C72")
      (value "5.6nF")
      (footprint "eagle-import:C050-025X075")
      (libsource (lib "eagle-import") (part "C-US050-025X075"))
    )
    (comp (ref "C73")
      (value "100nF")
      (footprint "eagle-import:C050-025X075")
      (libsource (lib "eagle-import") (part "C-US050-025X075"))
    )
    (comp (ref "C74")
      (value "100nF")
      (footprint "eagle-import:C050-025X075")
      (libsource (lib "eagle-import") (part "C-US050-025X075"))
    )
    (comp (ref "C75")
      (value "2.7nF")
      (footprint "eagle-import:C050-025X075")
      (libsource (lib "eagle-import") (part "C-US050-025X075"))
    )
    (comp (ref "C76")
      (value "4.7uF")
      (footprint "eagle-import:E2-5")
      (libsource (lib "eagle-import") (part "resistor_CPOL-EUE2-5"))
    )
    (comp (ref "C77")
      (value "4.7uF")
      (footprint "eagle-import:E2-5")
      (libsource (lib "eagle-import") (part "resistor_CPOL-EUE2-5"))
    )
    (comp (ref "C78")
      (value "2.7nF")
      (footprint "eagle-import:C050-025X075")
      (libsource (lib "eagle-import") (part "C-US050-025X075"))
    )
    (comp (ref "C79")
      (value "100nF")
      (footprint "eagle-import:C050-025X075")
      (libsource (lib "eagle-import") (part "C-US050-025X075"))
    )
    (comp (ref "C80")
      (value "100nF")
      (footprint "eagle-import:C050-025X075")
      (libsource (lib "eagle-import") (part "C-US050-025X075"))
    )
    (comp (ref "C81")
      (value "3.9nF")
      (footprint "eagle-import:C050-025X075")
      (libsource (lib "eagle-import") (part "C-US050-025X075"))
    )
    (comp (ref "C82")
      (value "4.7uF")
      (footprint "eagle-import:E2-5")
      (libsource (lib "eagle-import") (part "resistor_CPOL-EUE2-5"))
    )
    (comp (ref "C83")
      (value "4.7uF")
      (footprint "eagle-import:E2-5")
      (libsource (lib "eagle-import") (part "resistor_CPOL-EUE2-5"))
    )
    (comp (ref "IC10")
      (value "AD797")
      (footprint "eagle-import:SO08")
      (libsource (lib "eagle-import") (part "AD797"))
    )
    (comp (ref "IC11")
      (value "AD797")
      (footprint "eagle-import:SO08")
      (libsource (lib "eagle-import") (part "AD797"))
    )
    (comp (ref "IC12")
      (value "AD797")
      (footprint "eagle-import:SO08")
      (libsource (lib "eagle-import") (part "AD797"))
    )
    (comp (ref "J4")
      (value "RCARCA")
      (footprint "eagle-import:RCA")
      (libsource (lib "eagle-import") (part "RCARCA"))
    )
    (comp (ref "R39")
      (value "2k")
      (footprint "eagle-import:0207_12")
      (libsource (lib "eagle-import") (part "resistor_R-EU_0207/12"))
    )
    (comp (ref "R40")
      (value "806")
      (footprint "eagle-import:0207_12")
      (libsource (lib "eagle-import") (part "resistor_R-EU_0207/12"))
    )
    (comp (ref "R41")
      (value "806")
      (footprint "eagle-import:0207_12")
      (libsource (lib "eagle-import") (part "resistor_R-EU_0207/12"))
    )
    (comp (ref "R42")
      (value "2k")
      (footprint "eagle-import:0207_12")
      (libsource (lib "eagle-import") (part "resistor_R-EU_0207/12"))
    )
    (comp (ref "R43")
      (value "100")
      (footprint "eagle-import:0207_12")
      (libsource (lib "eagle-import") (part "resistor_R-EU_0207/12"))
    )
    (comp (ref "R44")
      (value "100")
      (footprint "eagle-import:0207_12")
      (libsource (lib "eagle-import") (part "resistor_R-EU_0207/12"))
    )
    (comp (ref "R45")
      (value "2.0k")
      (footprint "eagle-import:0207_12")
      (libsource (lib "eagle-import") (part "resistor_R-EU_0207/12"))
    )
    (comp (ref "R46")
      (value "2.0k")
      (footprint "eagle-import:0207_12")
      (libsource (lib "eagle-import") (part "resistor_R-EU_0207/12"))
    )
    (comp (ref "R47")
      (value "681")
      (footprint "eagle-import:0207_12")
      (libsource (lib "eagle-import") (part "resistor_R-EU_0207/12"))
    )
    (comp (ref "R48")
      (value "681")
      (footprint "eagle-import:0207_12")
      (libsource (lib "eagle-import") (part "resistor_R-EU_0207/12"))
    )
    (comp (ref "R49")
      (value "226")
      (footprint "eagle-import:0207_12")
      (libsource (lib "eagle-import") (part "resistor_R-EU_0207/12"))
    )
    (comp (ref "R50")
      (value "226")
      (footprint "eagle-import:0207_12")
      (libsource (lib "eagle-import") (part "resistor_R-EU_0207/12"))
    )
    (comp (ref "R51")
      (value "324")
      (footprint "eagle-import:0207_12")
      (libsource (lib "eagle-import") (part "resistor_R-EU_0207/12"))
    )
    (comp (ref "R52")
      (value "324")
      (footprint "eagle-import:0207_12")
      (libsource (lib "eagle-import") (part "resistor_R-EU_0207/12"))
    )
    (comp (ref "R53")
      (value "100")
      (footprint "eagle-import:0207_12")
      (libsource (lib "eagle-import") (part "resistor_R-EU_0207/12"))
    )
    (comp (ref "R54")
      (value "332")
      (footprint "eagle-import:0207_12")
      (libsource (lib "eagle-import") (part "resistor_R-EU_0207/12"))
    )
    (comp (ref "C103")
      (value "10uF")
      (footprint "eagle-import:C0603")
      (libsource (lib "eagle-import") (part "C-EUC0603"))
    )
    (comp (ref "C106")
      (value "100nF")
      (footprint "eagle-import:C0402")
      (libsource (lib "eagle-import") (part "C-EUC0402"))
    )
    (comp (ref "C107")
      (value "47pF")
      (footprint "eagle-import:C0402")
      (libsource (lib "eagle-import") (part "C-EUC0402"))
    )
    (comp (ref "C108")
      (value "47pF")
      (footprint "eagle-import:C0402")
      (libsource (lib "eagle-import") (part "C-EUC0402"))
    )
    (comp (ref "C109")
      (value "100nF")
      (footprint "eagle-import:C0402")
      (libsource (lib "eagle-import") (part "C-EUC0402"))
    )
    (comp (ref "C110")
      (value "10uF")
      (footprint "eagle-import:C0603")
      (libsource (lib "eagle-import") (part "C-EUC0603"))
    )
    (comp (ref "C111")
      (value "100nF")
      (footprint "eagle-import:C0402")
      (libsource (lib "eagle-import") (part "C-EUC0402"))
    )
    (comp (ref "C112")
      (value "4.7uF")
      (footprint "eagle-import:A_3216-18W")
      (libsource (lib "eagle-import") (part "CPOL-EUA/3216-18W"))
    )
    (comp (ref "C113")
      (value "100nF")
      (footprint "eagle-import:C0402")
      (libsource (lib "eagle-import") (part "C-EUC0402"))
    )
    (comp (ref "C114")
      (value "100nF")
      (footprint "eagle-import:C0402")
      (libsource (lib "eagle-import") (part "C-EUC0402"))
    )
    (comp (ref "C115")
      (value "10uF")
      (footprint "eagle-import:C0603")
      (libsource (lib "eagle-import") (part "C-EUC0603"))
    )
    (comp (ref "C116")
      (value "10uF")
      (footprint "eagle-import:C0603")
      (libsource (lib "eagle-import") (part "C-EUC0603"))
    )
    (comp (ref "C117")
      (value "100nF")
      (footprint "eagle-import:C0402")
      (libsource (lib "eagle-import") (part "C-EUC0402"))
    )
    (comp (ref "C118")
      (value "100nF")
      (footprint "eagle-import:C0402")
      (libsource (lib "eagle-import") (part "C-EUC0402"))
    )
    (comp (ref "CUSB2")
      (value "4.7nF")
      (footprint "eagle-import:C0402")
      (libsource (lib "eagle-import") (part "C-EUC0402"))
    )
    (comp (ref "IC17")
      (value "USBLC6-2SC6")
      (footprint "eagle-import:SOT23-6L")
      (libsource (lib "eagle-import") (part "USBLC6-2"))
    )
    (comp (ref "IC19")
      (value "FT232RL")
      (footprint "eagle-import:SSOP28")
      (libsource (lib "eagle-import") (part "FT232RL"))
    )
    (comp (ref "IC20")
      (value "LP5907MFX-3.3")
      (footprint "eagle-import:TSOT23-5")
      (libsource (lib "eagle-import") (part "TLV700XX"))
    )
    (comp (ref "IC21")
      (value "SI8642BC-B-IS1")
      (footprint "eagle-import:NSOIC-16")
      (libsource (lib "eagle-import") (part "SI8645"))
    )
    (comp (ref "IC32")
      (value "TPS73801")
      (footprint "eagle-import:SOT223-6")
      (libsource (lib "eagle-import") (part "TPS73801"))
    )
    (comp (ref "L10")
      (value "???")
      (footprint "eagle-import:R0805")
      (libsource (lib "eagle-import") (part "R-EU_R0805"))
    )
    (comp (ref "L11")
      (value "600@100M")
      (footprint "eagle-import:R0805")
      (libsource (lib "eagle-import") (part "R-EU_R0805"))
    )
    (comp (ref "R58")
      (value "2050 NA")
      (footprint "eagle-import:R0402")
      (libsource (lib "eagle-import") (part "R-EU_R0402"))
    )
    (comp (ref "R59")
      (value "680 NA")
      (footprint "eagle-import:R0402")
      (libsource (lib "eagle-import") (part "R-EU_R0402"))
    )
    (comp (ref "R72")
      (value "3.16k")
      (footprint "eagle-import:R0402")
      (libsource (lib "eagle-import") (part "R-EU_R0402"))
    )
    (comp (ref "R73")
      (value "9.76k")
      (footprint "eagle-import:R0402")
      (libsource (lib "eagle-import") (part "R-EU_R0402"))
    )
    (comp (ref "RUSB2")
      (value "1M")
      (footprint "eagle-import:R0402")
      (libsource (lib "eagle-import") (part "R-EU_R0402"))
    )
    (comp (ref "RX")
      (value "GREEN NA")
      (footprint "eagle-import:LED_HAND")
      (libsource (lib "eagle-import") (part "LEDHAND"))
    )
    (comp (ref "TX")
      (value "RED NA")
      (footprint "eagle-import:LED_HAND")
      (libsource (lib "eagle-import") (part "LEDHAND"))
    )
    (comp (ref "USB2")
      (value "USB_MINI_B")
      (footprint "eagle-import:240-0002-1")
      (libsource (lib "eagle-import") (part "USB_MINI_B"))
    )
    (comp (ref "C34")
      (value "100nF")
      (footprint "eagle-import:C050-025X075")
      (libsource (lib "eagle-import") (part "C-US050-025X075"))
    )
    (comp (ref "C35")
      (value "47uF")
      (footprint "eagle-import:E2-5")
      (libsource (lib "eagle-import") (part "resistor_CPOL-EUE2-5"))
    )
    (comp (ref "C36")
      (value "4.7uF")
      (footprint "eagle-import:E2-5")
      (libsource (lib "eagle-import") (part "resistor_CPOL-EUE2-5"))
    )
    (comp (ref "C37")
      (value "100nF")
      (footprint "eagle-import:C050-025X075")
      (libsource (lib "eagle-import") (part "C-US050-025X075"))
    )
    (comp (ref "C38")
      (value "100pF")
      (footprint "eagle-import:C0603")
      (libsource (lib "eagle-import") (part "C-EUC0603"))
    )
    (comp (ref "C39")
      (value "100nF")
      (footprint "eagle-import:C050-025X075")
      (libsource (lib "eagle-import") (part "C-US050-025X075"))
    )
    (comp (ref "C40")
      (value "100nF")
      (footprint "eagle-import:C050-025X075")
      (libsource (lib "eagle-import") (part "C-US050-025X075"))
    )
    (comp (ref "C41")
      (value "100nF")
      (footprint "eagle-import:C050-025X075")
      (libsource (lib "eagle-import") (part "C-US050-025X075"))
    )
    (comp (ref "C42")
      (value "100nF")
      (footprint "eagle-import:C050-025X075")
      (libsource (lib "eagle-import") (part "C-US050-025X075"))
    )
    (comp (ref "C43")
      (value "100pF")
      (footprint "eagle-import:C050-025X075")
      (libsource (lib "eagle-import") (part "C-US050-025X075"))
    )
    (comp (ref "C44")
      (value "100pF")
      (footprint "eagle-import:C050-025X075")
      (libsource (lib "eagle-import") (part "C-US050-025X075"))
    )
    (comp (ref "C45")
      (value "4.7uF")
      (footprint "eagle-import:E2-5")
      (libsource (lib "eagle-import") (part "resistor_CPOL-EUE2-5"))
    )
    (comp (ref "C46")
      (value "4.7uF")
      (footprint "eagle-import:E2-5")
      (libsource (lib "eagle-import") (part "resistor_CPOL-EUE2-5"))
    )
    (comp (ref "C47")
      (value "5.6nF")
      (footprint "eagle-import:C050-025X075")
      (libsource (lib "eagle-import") (part "C-US050-025X075"))
    )
    (comp (ref "C48")
      (value "5.6nF")
      (footprint "eagle-import:C050-025X075")
      (libsource (lib "eagle-import") (part "C-US050-025X075"))
    )
    (comp (ref "C49")
      (value "100nF")
      (footprint "eagle-import:C050-025X075")
      (libsource (lib "eagle-import") (part "C-US050-025X075"))
    )
    (comp (ref "C50")
      (value "100nF")
      (footprint "eagle-import:C050-025X075")
      (libsource (lib "eagle-import") (part "C-US050-025X075"))
    )
    (comp (ref "C51")
      (value "2.7nF")
      (footprint "eagle-import:C050-025X075")
      (libsource (lib "eagle-import") (part "C-US050-025X075"))
    )
    (comp (ref "C52")
      (value "4.7uF")
      (footprint "eagle-import:E2-5")
      (libsource (lib "eagle-import") (part "resistor_CPOL-EUE2-5"))
    )
    (comp (ref "C53")
      (value "4.7uF")
      (footprint "eagle-import:E2-5")
      (libsource (lib "eagle-import") (part "resistor_CPOL-EUE2-5"))
    )
    (comp (ref "C54")
      (value "2.7nF")
      (footprint "eagle-import:C050-025X075")
      (libsource (lib "eagle-import") (part "C-US050-025X075"))
    )
    (comp (ref "C55")
      (value "100nF")
      (footprint "eagle-import:C050-025X075")
      (libsource (lib "eagle-import") (part "C-US050-025X075"))
    )
    (comp (ref "C56")
      (value "100nF")
      (footprint "eagle-import:C050-025X075")
      (libsource (lib "eagle-import") (part "C-US050-025X075"))
    )
    (comp (ref "C57")
      (value "3.9nF")
      (footprint "eagle-import:C050-025X075")
      (libsource (lib "eagle-import") (part "C-US050-025X075"))
    )
    (comp (ref "C58")
      (value "4.7uF")
      (footprint "eagle-import:E2-5")
      (libsource (lib "eagle-import") (part "resistor_CPOL-EUE2-5"))
    )
    (comp (ref "C59")
      (value "4.7uF")
      (footprint "eagle-import:E2-5")
      (libsource (lib "eagle-import") (part "resistor_CPOL-EUE2-5"))
    )
    (comp (ref "IC7")
      (value "AD797")
      (footprint "eagle-import:SO08")
      (libsource (lib "eagle-import") (part "AD797"))
    )
    (comp (ref "IC8")
      (value "AD797")
      (footprint "eagle-import:SO08")
      (libsource (lib "eagle-import") (part "AD797"))
    )
    (comp (ref "IC9")
      (value "AD797")
      (footprint "eagle-import:SO08")
      (libsource (lib "eagle-import") (part "AD797"))
    )
    (comp (ref "J3")
      (value "RCARCA")
      (footprint "eagle-import:RCA")
      (libsource (lib "eagle-import") (part "RCARCA"))
    )
    (comp (ref "R21")
      (value "2.21k")
      (footprint "eagle-import:0207_12")
      (libsource (lib "eagle-import") (part "resistor_R-EU_0207/12"))
    )
    (comp (ref "R22")
      (value "2.80k")
      (footprint "eagle-import:0207_12")
      (libsource (lib "eagle-import") (part "resistor_R-EU_0207/12"))
    )
    (comp (ref "R23")
      (value "2k")
      (footprint "eagle-import:0207_12")
      (libsource (lib "eagle-import") (part "resistor_R-EU_0207/12"))
    )
    (comp (ref "R24")
      (value "806")
      (footprint "eagle-import:0207_12")
      (libsource (lib "eagle-import") (part "resistor_R-EU_0207/12"))
    )
    (comp (ref "R25")
      (value "806")
      (footprint "eagle-import:0207_12")
      (libsource (lib "eagle-import") (part "resistor_R-EU_0207/12"))
    )
    (comp (ref "R26")
      (value "2k")
      (footprint "eagle-import:0207_12")
      (libsource (lib "eagle-import") (part "resistor_R-EU_0207/12"))
    )
    (comp (ref "R27")
      (value "100")
      (footprint "eagle-import:0207_12")
      (libsource (lib "eagle-import") (part "resistor_R-EU_0207/12"))
    )
    (comp (ref "R28")
      (value "100")
      (footprint "eagle-import:0207_12")
      (libsource (lib "eagle-import") (part "resistor_R-EU_0207/12"))
    )
    (comp (ref "R29")
      (value "2.0k")
      (footprint "eagle-import:0207_12")
      (libsource (lib "eagle-import") (part "resistor_R-EU_0207/12"))
    )
    (comp (ref "R30")
      (value "2.0k")
      (footprint "eagle-import:0207_12")
      (libsource (lib "eagle-import") (part "resistor_R-EU_0207/12"))
    )
    (comp (ref "R31")
      (value "681")
      (footprint "eagle-import:0207_12")
      (libsource (lib "eagle-import") (part "resistor_R-EU_0207/12"))
    )
    (comp (ref "R32")
      (value "681")
      (footprint "eagle-import:0207_12")
      (libsource (lib "eagle-import") (part "resistor_R-EU_0207/12"))
    )
    (comp (ref "R33")
      (value "226")
      (footprint "eagle-import:0207_12")
      (libsource (lib "eagle-import") (part "resistor_R-EU_0207/12"))
    )
    (comp (ref "R34")
      (value "226")
      (footprint "eagle-import:0207_12")
      (libsource (lib "eagle-import") (part "resistor_R-EU_0207/12"))
    )
    (comp (ref "R35")
      (value "324")
      (footprint "eagle-import:0207_12")
      (libsource (lib "eagle-import") (part "resistor_R-EU_0207/12"))
    )
    (comp (ref "R36")
      (value "324")
      (footprint "eagle-import:0207_12")
      (libsource (lib "eagle-import") (part "resistor_R-EU_0207/12"))
    )
    (comp (ref "R37")
      (value "100")
      (footprint "eagle-import:0207_12")
      (libsource (lib "eagle-import") (part "resistor_R-EU_0207/12"))
    )
    (comp (ref "R38")
      (value "332")
      (footprint "eagle-import:0207_12")
      (libsource (lib "eagle-import") (part "resistor_R-EU_0207/12"))
    )
    (comp (ref "C104")
      (value "100nF")
      (footprint "eagle-import:C0402")
      (libsource (lib "eagle-import") (part "C-EUC0402"))
    )
    (comp (ref "C105")
      (value "100nF")
      (footprint "eagle-import:C0402")
      (libsource (lib "eagle-import") (part "C-EUC0402"))
    )
    (comp (ref "C119")
      (value "100nF")
      (footprint "eagle-import:C0402")
      (libsource (lib "eagle-import") (part "C-EUC0402"))
    )
    (comp (ref "C120")
      (value "100nF")
      (footprint "eagle-import:C0402")
      (libsource (lib "eagle-import") (part "C-EUC0402"))
    )
    (comp (ref "C121")
      (value "100nF")
      (footprint "eagle-import:C0402")
      (libsource (lib "eagle-import") (part "C-EUC0402"))
    )
    (comp (ref "C122")
      (value "100nF")
      (footprint "eagle-import:C0402")
      (libsource (lib "eagle-import") (part "C-EUC0402"))
    )
    (comp (ref "C123")
      (value "100nF")
      (footprint "eagle-import:C0402")
      (libsource (lib "eagle-import") (part "C-EUC0402"))
    )
    (comp (ref "C124")
      (value "100nF")
      (footprint "eagle-import:C0402")
      (libsource (lib "eagle-import") (part "C-EUC0402"))
    )
    (comp (ref "C125")
      (value "100nF")
      (footprint "eagle-import:C0402")
      (libsource (lib "eagle-import") (part "C-EUC0402"))
    )
    (comp (ref "C126")
      (value "100nF")
      (footprint "eagle-import:C0402")
      (libsource (lib "eagle-import") (part "C-EUC0402"))
    )
    (comp (ref "C127")
      (value "100nF")
      (footprint "eagle-import:C0402")
      (libsource (lib "eagle-import") (part "C-EUC0402"))
    )
    (comp (ref "C128")
      (value "100nF")
      (footprint "eagle-import:C0402")
      (libsource (lib "eagle-import") (part "C-EUC0402"))
    )
    (comp (ref "C129")
      (value "100nF")
      (footprint "eagle-import:C0402")
      (libsource (lib "eagle-import") (part "C-EUC0402"))
    )
    (comp (ref "C130")
      (value "330nF")
      (footprint "eagle-import:C0402")
      (libsource (lib "eagle-import") (part "C-EUC0402"))
    )
    (comp (ref "C131")
      (value "330nF")
      (footprint "eagle-import:C0402")
      (libsource (lib "eagle-import") (part "C-EUC0402"))
    )
    (comp (ref "C132")
      (value "10uF")
      (footprint "eagle-import:C0603")
      (libsource (lib "eagle-import") (part "C-EUC0603"))
    )
    (comp (ref "C140")
      (value "100nF")
      (footprint "eagle-import:C0402")
      (libsource (lib "eagle-import") (part "C-EUC0402"))
    )
    (comp (ref "C143")
      (value "100nF")
      (footprint "eagle-import:C0402")
      (libsource (lib "eagle-import") (part "C-EUC0402"))
    )
    (comp (ref "CLKIN")
      (value "STEREO_JACK")
      (footprint "eagle-import:35RASMT2BHNTRX")
      (libsource (lib "eagle-import") (part "STEREO_JACK"))
    )
    (comp (ref "GND174")
      (value "TP")
      (footprint "eagle-import:TP_1")
      (libsource (lib "eagle-import") (part "TP"))
    )
    (comp (ref "IC22")
      (value "SN74LVC1G125")
      (footprint "eagle-import:SOT23-5")
      (libsource (lib "eagle-import") (part "SN74LVC1G125"))
    )
    (comp (ref "IC23")
      (value "SN74LVC1G125")
      (footprint "eagle-import:SOT23-5")
      (libsource (lib "eagle-import") (part "SN74LVC1G125"))
    )
    (comp (ref "IC24")
      (value "SN74LVC1G125")
      (footprint "eagle-import:SOT23-5")
      (libsource (lib "eagle-import") (part "SN74LVC1G125"))
    )
    (comp (ref "IC25")
      (value "ATXMEGAxxxA4U-AU")
      (footprint "eagle-import:QFP80P1200X1200X120-44N")
      (libsource (lib "eagle-import") (part "AT-XMEGA-XXA4-AU"))
    )
    (comp (ref "IC26")
      (value "SI8645")
      (footprint "eagle-import:NSOIC-16")
      (libsource (lib "eagle-import") (part "SI8645"))
    )
    (comp (ref "IC27")
      (value "SN65HVD")
      (footprint "eagle-import:SO08")
      (libsource (lib "eagle-import") (part "SN65HVD"))
    )
    (comp (ref "IC33")
      (value "VHC1GT126")
      (footprint "eagle-import:SC-70-5")
      (libsource (lib "eagle-import") (part "VHC1GT126"))
    )
    (comp (ref "IC34")
      (value "VHC1GT126")
      (footprint "eagle-import:SC-70-5")
      (libsource (lib "eagle-import") (part "VHC1GT126"))
    )
    (comp (ref "IC35")
      (value "VHC1GT125")
      (footprint "eagle-import:SC-70-5")
      (libsource (lib "eagle-import") (part "VHC1GT125"))
    )
    (comp (ref "IN")
      (value "BNC")
      (footprint "eagle-import:BNC_RA")
      (libsource (lib "eagle-import") (part "BNC"))
    )
    (comp (ref "IN1")
      (value "22-05-7028-02")
      (footprint "eagle-import:7395-02")
      (libsource (lib "eagle-import") (part "22-?-0205-7028"))
    )
    (comp (ref "J1")
      (value "Port 1")
      (footprint "eagle-import:520426-4")
      (libsource (lib "eagle-import") (part "520426-4"))
    )
    (comp (ref "J2")
      (value "Port 1")
      (footprint "eagle-import:520426-4")
      (libsource (lib "eagle-import") (part "520426-4"))
    )
    (comp (ref "L12")
      (value "1u")
      (footprint "eagle-import:R0603")
      (libsource (lib "eagle-import") (part "R-EU_R0603"))
    )
    (comp (ref "OSC2")
      (value "OSCILLATOR")
      (footprint "eagle-import:OSCILLATOR_3.2X2.5")
      (libsource (lib "eagle-import") (part "OSCILLATOR"))
    )
    (comp (ref "OUT")
      (value "BNC")
      (footprint "eagle-import:BNC_RA")
      (libsource (lib "eagle-import") (part "BNC"))
    )
    (comp (ref "OUT1")
      (value "22-05-7028-02")
      (footprint "eagle-import:7395-02")
      (libsource (lib "eagle-import") (part "22-?-0205-7028"))
    )
    (comp (ref "PDI")
      (value "MA03-2")
      (footprint "eagle-import:MA03-2")
      (libsource (lib "eagle-import") (part "MA03-2"))
    )
    (comp (ref "R19")
      (value "3.16k")
      (footprint "eagle-import:R0402")
      (libsource (lib "eagle-import") (part "R-EU_R0402"))
    )
    (comp (ref "R61")
      (value "100k")
      (footprint "eagle-import:R0402")
      (libsource (lib "eagle-import") (part "R-EU_R0402"))
    )
    (comp (ref "R62")
      (value "3.16k")
      (footprint "eagle-import:R0402")
      (libsource (lib "eagle-import") (part "R-EU_R0402"))
    )
    (comp (ref "R63")
      (value "1k")
      (footprint "eagle-import:R0402")
      (libsource (lib "eagle-import") (part "R-EU_R0402"))
    )
    (comp (ref "R64")
      (value "100 NA")
      (footprint "eagle-import:R0402")
      (libsource (lib "eagle-import") (part "R-EU_R0402"))
    )
    (comp (ref "R65")
      (value "100 NA")
      (footprint "eagle-import:R0402")
      (libsource (lib "eagle-import") (part "R-EU_R0402"))
    )
    (comp (ref "R66")
      (value "68")
      (footprint "eagle-import:R0402")
      (libsource (lib "eagle-import") (part "R-EU_R0402"))
    )
    (comp (ref "R89")
      (value "100k")
      (footprint "eagle-import:R0402")
      (libsource (lib "eagle-import") (part "R-EU_R0402"))
    )
    (comp (ref "STATE")
      (value "GREEN")
      (footprint "eagle-import:LED_HAND")
      (libsource (lib "eagle-import") (part "LEDHAND"))
    )
    (comp (ref "C84")
      (value "100nF")
      (footprint "eagle-import:C0402")
      (libsource (lib "eagle-import") (part "C-EUC0402"))
    )
    (comp (ref "C85")
      (value "10uF")
      (footprint "eagle-import:C0603")
      (libsource (lib "eagle-import") (part "C-EUC0603"))
    )
    (comp (ref "C86")
      (value "10uF")
      (footprint "eagle-import:C0603")
      (libsource (lib "eagle-import") (part "C-EUC0603"))
    )
    (comp (ref "C87")
      (value "10uF")
      (footprint "eagle-import:C0603")
      (libsource (lib "eagle-import") (part "C-EUC0603"))
    )
    (comp (ref "C88")
      (value "100nF")
      (footprint "eagle-import:C0402")
      (libsource (lib "eagle-import") (part "C-EUC0402"))
    )
    (comp (ref "C89")
      (value "100nF")
      (footprint "eagle-import:C0402")
      (libsource (lib "eagle-import") (part "C-EUC0402"))
    )
    (comp (ref "C90")
      (value "100nF")
      (footprint "eagle-import:C0402")
      (libsource (lib "eagle-import") (part "C-EUC0402"))
    )
    (comp (ref "C91")
      (value "10uF")
      (footprint "eagle-import:C0603")
      (libsource (lib "eagle-import") (part "C-EUC0603"))
    )
    (comp (ref "C92")
      (value "100nF")
      (footprint "eagle-import:C0402")
      (libsource (lib "eagle-import") (part "C-EUC0402"))
    )
    (comp (ref "C93")
      (value "100nF")
      (footprint "eagle-import:C0402")
      (libsource (lib "eagle-import") (part "C-EUC0402"))
    )
    (comp (ref "C94")
      (value "100nF")
      (footprint "eagle-import:C0402")
      (libsource (lib "eagle-import") (part "C-EUC0402"))
    )
    (comp (ref "C95")
      (value "100nF")
      (footprint "eagle-import:C0402")
      (libsource (lib "eagle-import") (part "C-EUC0402"))
    )
    (comp (ref "C96")
      (value "100nF")
      (footprint "eagle-import:C0402")
      (libsource (lib "eagle-import") (part "C-EUC0402"))
    )
    (comp (ref "C97")
      (value "100nF")
      (footprint "eagle-import:C0402")
      (libsource (lib "eagle-import") (part "C-EUC0402"))
    )
    (comp (ref "C98")
      (value "100nF")
      (footprint "eagle-import:C0402")
      (libsource (lib "eagle-import") (part "C-EUC0402"))
    )
    (comp (ref "C99")
      (value "100nF")
      (footprint "eagle-import:C0402")
      (libsource (lib "eagle-import") (part "C-EUC0402"))
    )
    (comp (ref "C100")
      (value "10uF")
      (footprint "eagle-import:C0603")
      (libsource (lib "eagle-import") (part "C-EUC0603"))
    )
    (comp (ref "C101")
      (value "100nF")
      (footprint "eagle-import:C0402")
      (libsource (lib "eagle-import") (part "C-EUC0402"))
    )
    (comp (ref "C102")
      (value "100nF")
      (footprint "eagle-import:C0402")
      (libsource (lib "eagle-import") (part "C-EUC0402"))
    )
    (comp (ref "C138")
      (value "100nF")
      (footprint "eagle-import:C0402")
      (libsource (lib "eagle-import") (part "C-EUC0402"))
    )
    (comp (ref "C139")
      (value "100nF")
      (footprint "eagle-import:C0402")
      (libsource (lib "eagle-import") (part "C-EUC0402"))
    )
    (comp (ref "C141")
      (value "100nF")
      (footprint "eagle-import:C0402")
      (libsource (lib "eagle-import") (part "C-EUC0402"))
    )
    (comp (ref "C142")
      (value "100nF")
      (footprint "eagle-import:C0402")
      (libsource (lib "eagle-import") (part "C-EUC0402"))
    )
    (comp (ref "CUSB1")
      (value "4.7nF")
      (footprint "eagle-import:C0402")
      (libsource (lib "eagle-import") (part "C-EUC0402"))
    )
    (comp (ref "GND176")
      (value "TP")
      (footprint "eagle-import:TP_1")
      (libsource (lib "eagle-import") (part "TP"))
    )
    (comp (ref "IC13")
      (value "S34ML")
      (footprint "eagle-import:TSOP-48")
      (libsource (lib "eagle-import") (part "S34ML"))
    )
    (comp (ref "IC14")
      (value "TPS73801")
      (footprint "eagle-import:SOT223-6")
      (libsource (lib "eagle-import") (part "TPS73801"))
    )
    (comp (ref "IC15")
      (value "USBLC6-2SC6")
      (footprint "eagle-import:SOT23-6L")
      (libsource (lib "eagle-import") (part "USBLC6-2"))
    )
    (comp (ref "IC16")
      (value "PIC32MZ2048EFM100")
      (footprint "eagle-import:TQFP-100")
      (libsource (lib "eagle-import") (part "PIC32MZ2048EFM100"))
    )
    (comp (ref "IC18")
      (value "LP5907MFX-3.3")
      (footprint "eagle-import:TSOT23-5")
      (libsource (lib "eagle-import") (part "TLV700XX"))
    )
    (comp (ref "JP1")
      (value "M06NO_SILK")
      (footprint "eagle-import:1X06_NO_SILK")
      (libsource (lib "eagle-import") (part "M06NO_SILK"))
    )
    (comp (ref "L9")
      (value "600@100M")
      (footprint "eagle-import:R0805")
      (libsource (lib "eagle-import") (part "R-EU_R0805"))
    )
    (comp (ref "L13")
      (value "???")
      (footprint "eagle-import:R0805")
      (libsource (lib "eagle-import") (part "R-EU_R0805"))
    )
    (comp (ref "LED1")
      (value "RED")
      (footprint "eagle-import:LED_HAND")
      (libsource (lib "eagle-import") (part "LEDHAND"))
    )
    (comp (ref "LED2")
      (value "RED")
      (footprint "eagle-import:LED_HAND")
      (libsource (lib "eagle-import") (part "LEDHAND"))
    )
    (comp (ref "LED3")
      (value "RED")
      (footprint "eagle-import:LED_HAND")
      (libsource (lib "eagle-import") (part "LEDHAND"))
    )
    (comp (ref "OSC1")
      (value "OSCILLATOR2.5X2.0MM")
      (footprint "eagle-import:CRYSTAL_2.5X2.0MM")
      (libsource (lib "eagle-import") (part "OSCILLATOR2.5X2.0MM"))
    )
    (comp (ref "OSC3")
      (value "XOSC_2.5X2.0MM")
      (footprint "eagle-import:CRYSTAL_2.5X2.0MM")
      (libsource (lib "eagle-import") (part "XOSC_2.5X2.0MM"))
    )
    (comp (ref "R55")
      (value "3.16k")
      (footprint "eagle-import:R0402")
      (libsource (lib "eagle-import") (part "R-EU_R0402"))
    )
    (comp (ref "R56")
      (value "10k")
      (footprint "eagle-import:R0402")
      (libsource (lib "eagle-import") (part "R-EU_R0402"))
    )
    (comp (ref "R57")
      (value "1k")
      (footprint "eagle-import:R0402")
      (libsource (lib "eagle-import") (part "R-EU_R0402"))
    )
    (comp (ref "R60")
      (value "3.16k")
      (footprint "eagle-import:R0402")
      (libsource (lib "eagle-import") (part "R-EU_R0402"))
    )
    (comp (ref "R71")
      (value "3.16k")
      (footprint "eagle-import:R0402")
      (libsource (lib "eagle-import") (part "R-EU_R0402"))
    )
    (comp (ref "R74")
      (value "9.76k")
      (footprint "eagle-import:R0402")
      (libsource (lib "eagle-import") (part "R-EU_R0402"))
    )
    (comp (ref "R75")
      (value "2050")
      (footprint "eagle-import:R0402")
      (libsource (lib "eagle-import") (part "R-EU_R0402"))
    )
    (comp (ref "R76")
      (value "2050")
      (footprint "eagle-import:R0402")
      (libsource (lib "eagle-import") (part "R-EU_R0402"))
    )
    (comp (ref "R77")
      (value "2050")
      (footprint "eagle-import:R0402")
      (libsource (lib "eagle-import") (part "R-EU_R0402"))
    )
    (comp (ref "R80")
      (value "3.16k")
      (footprint "eagle-import:R0402")
      (libsource (lib "eagle-import") (part "R-EU_R0402"))
    )
    (comp (ref "RUSB1")
      (value "1M")
      (footprint "eagle-import:R0402")
      (libsource (lib "eagle-import") (part "R-EU_R0402"))
    )
    (comp (ref "SW1")
      (value "SW1\"")
      (footprint "eagle-import:SWITCH_KSS")
      (libsource (lib "eagle-import") (part "SW1{dblquote}"))
    )
    (comp (ref "TP0")
      (value "TP")
      (footprint "eagle-import:TP_1")
      (libsource (lib "eagle-import") (part "TP"))
    )
    (comp (ref "TP1")
      (value "TP")
      (footprint "eagle-import:TP_1")
      (libsource (lib "eagle-import") (part "TP"))
    )
    (comp (ref "USB1")
      (value "USB_MICRO_B")
      (footprint "eagle-import:ZX62D-B-5P8")
      (libsource (lib "eagle-import") (part "USB_MICRO_B"))
    )
  )
  (nets
    (net (code "1") (name "+5V") (class "Default")
      (node (ref "C103") (pin "1") (pinfunction "1_1") (pintype "passive"))
      (node (ref "C115") (pin "1") (pinfunction "1_1") (pintype "passive"))
      (node (ref "IC20") (pin "1") (pinfunction "IN_1") (pintype "bidirectional"))
      (node (ref "IC20") (pin "3") (pinfunction "EN_3") (pintype "bidirectional"))
      (node (ref "IC32") (pin "P$2") (pinfunction "OUT_P$2") (pintype "bidirectional"))
      (node (ref "JP2") (pin "1") (pinfunction "1_1") (pintype "passive"))
      (node (ref "R73") (pin "2") (pinfunction "2_2") (pintype "passive"))
      (node (ref "X1") (pin "P2") (pinfunction "2_P2") (pintype "passive"))
    )
    (net (code "2") (name "+12V") (class "Default")
      (node (ref "C3") (pin "2") (pinfunction "2_2") (pintype "passive"))
      (node (ref "C36") (pin "+") (pinfunction "+_+") (pintype "passive"))
      (node (ref "C37") (pin "1") (pinfunction "1_1") (pintype "passive"))
      (node (ref "C41") (pin "1") (pinfunction "1_1") (pintype "passive"))
      (node (ref "C45") (pin "+") (pinfunction "+_+") (pintype "passive"))
      (node (ref "C49") (pin "1") (pinfunction "1_1") (pintype "passive"))
      (node (ref "C5") (pin "1") (pinfunction "1_1") (pintype "passive"))
      (node (ref "C52") (pin "+") (pinfunction "+_+") (pintype "passive"))
      (node (ref "C55") (pin "1") (pinfunction "1_1") (pintype "passive"))
      (node (ref "C58") (pin "+") (pinfunction "+_+") (pintype "passive"))
      (node (ref "C60") (pin "+") (pinfunction "+_+") (pintype "passive"))
      (node (ref "C61") (pin "1") (pinfunction "1_1") (pintype "passive"))
      (node (ref "C65") (pin "1") (pinfunction "1_1") (pintype "passive"))
      (node (ref "C69") (pin "+") (pinfunction "+_+") (pintype "passive"))
      (node (ref "C73") (pin "1") (pinfunction "1_1") (pintype "passive"))
      (node (ref "C76") (pin "+") (pinfunction "+_+") (pintype "passive"))
      (node (ref "C79") (pin "1") (pinfunction "1_1") (pintype "passive"))
      (node (ref "C82") (pin "+") (pinfunction "+_+") (pintype "passive"))
      (node (ref "IC1") (pin "5") (pinfunction "OUT_5") (pintype "bidirectional"))
      (node (ref "IC10") (pin "7") (pinfunction "V+_7") (pintype "power_in"))
      (node (ref "IC11") (pin "7") (pinfunction "V+_7") (pintype "power_in"))
      (node (ref "IC12") (pin "7") (pinfunction "V+_7") (pintype "power_in"))
      (node (ref "IC7") (pin "7") (pinfunction "V+_7") (pintype "power_in"))
      (node (ref "IC8") (pin "7") (pinfunction "V+_7") (pintype "power_in"))
      (node (ref "IC9") (pin "7") (pinfunction "V+_7") (pintype "power_in"))
      (node (ref "R1") (pin "1") (pinfunction "1_1") (pintype "passive"))
      (node (ref "R2") (pin "1") (pinfunction "1_1") (pintype "passive"))
      (node (ref "R23") (pin "2") (pinfunction "2_2") (pintype "passive"))
      (node (ref "R26") (pin "2") (pinfunction "2_2") (pintype "passive"))
      (node (ref "R39") (pin "2") (pinfunction "2_2") (pintype "passive"))
      (node (ref "R42") (pin "2") (pinfunction "2_2") (pintype "passive"))
    )
    (net (code "3") (name "+15V") (class "Default")
      (node (ref "C1") (pin "1") (pinfunction "1_1") (pintype "passive"))
      (node (ref "C4") (pin "1") (pinfunction "1_1") (pintype "passive"))
      (node (ref "IC1") (pin "1") (pinfunction "IN_1") (pintype "bidirectional"))
      (node (ref "L1") (pin "1") (pinfunction "1_1") (pintype "passive"))
      (node (ref "R5") (pin "2") (pinfunction "2_2") (pintype "passive"))
      (node (ref "R6") (pin "2") (pinfunction "2_2") (pintype "passive"))
    )
    (net (code "4") (name "-12V") (class "Default")
      (node (ref "C15") (pin "2") (pinfunction "2_2") (pintype "passive"))
      (node (ref "C16") (pin "1") (pinfunction "1_1") (pintype "passive"))
      (node (ref "C42") (pin "2") (pinfunction "2_2") (pintype "passive"))
      (node (ref "C46") (pin "-") (pinfunction "-_-") (pintype "passive"))
      (node (ref "C50") (pin "2") (pinfunction "2_2") (pintype "passive"))
      (node (ref "C53") (pin "-") (pinfunction "-_-") (pintype "passive"))
      (node (ref "C56") (pin "2") (pinfunction "2_2") (pintype "passive"))
      (node (ref "C59") (pin "-") (pinfunction "-_-") (pintype "passive"))
      (node (ref "C66") (pin "2") (pinfunction "2_2") (pintype "passive"))
      (node (ref "C70") (pin "-") (pinfunction "-_-") (pintype "passive"))
      (node (ref "C74") (pin "2") (pinfunction "2_2") (pintype "passive"))
      (node (ref "C77") (pin "-") (pinfunction "-_-") (pintype "passive"))
      (node (ref "C80") (pin "2") (pinfunction "2_2") (pintype "passive"))
      (node (ref "C83") (pin "-") (pinfunction "-_-") (pintype "passive"))
      (node (ref "IC10") (pin "4") (pinfunction "V-_4") (pintype "power_in"))
      (node (ref "IC11") (pin "4") (pinfunction "V-_4") (pintype "power_in"))
      (node (ref "IC12") (pin "4") (pinfunction "V-_4") (pintype "power_in"))
      (node (ref "IC3") (pin "5") (pinfunction "OUT_5") (pintype "bidirectional"))
      (node (ref "IC7") (pin "4") (pinfunction "V-_4") (pintype "power_in"))
      (node (ref "IC8") (pin "4") (pinfunction "V-_4") (pintype "power_in"))
      (node (ref "IC9") (pin "4") (pinfunction "V-_4") (pintype "power_in"))
      (node (ref "R11") (pin "1") (pinfunction "1_1") (pintype "passive"))
      (node (ref "R14") (pin "1") (pinfunction "1_1") (pintype "passive"))
    )
    (net (code "5") (name "-15V") (class "Default")
      (node (ref "C17") (pin "1") (pinfunction "1_1") (pintype "passive"))
      (node (ref "C9") (pin "1") (pinfunction "1_1") (pintype "passive"))
      (node (ref "IC3") (pin "2") (pinfunction "IN_2") (pintype "bidirectional"))
      (node (ref "L4") (pin "2") (pinfunction "2_2") (pintype "passive"))
      (node (ref "R12") (pin "1") (pinfunction "1_1") (pintype "passive"))
      (node (ref "R17") (pin "1") (pinfunction "1_1") (pintype "passive"))
    )
    (net (code "6") (name "A5V0") (class "Default")
      (node (ref "C18") (pin "2") (pinfunction "2_2") (pintype "passive"))
      (node (ref "C20") (pin "2") (pinfunction "2_2") (pintype "passive"))
      (node (ref "C22") (pin "2") (pinfunction "2_2") (pintype "passive"))
      (node (ref "IC4") (pin "1") (pinfunction "OUT_1") (pintype "bidirectional"))
      (node (ref "IC4") (pin "2") (pinfunction "OUT_2") (pintype "bidirectional"))
      (node (ref "L8") (pin "1") (pinfunction "1_1") (pintype "passive"))
      (node (ref "R21") (pin "2") (pinfunction "2_2") (pintype "passive"))
    )
    (net (code "7") (name "ADC0") (class "Default")
      (node (ref "C144") (pin "2") (pinfunction "2_2") (pintype "passive"))
      (node (ref "R60") (pin "1") (pinfunction "1_1") (pintype "passive"))
      (node (ref "R62") (pin "1") (pinfunction "1_1") (pintype "passive"))
      (node (ref "R81") (pin "2") (pinfunction "2_2") (pintype "passive"))
    )
    (net (code "8") (name "ADC0_EZ") (class "Default")
      (node (ref "C141") (pin "1") (pinfunction "1_1") (pintype "passive"))
      (node (ref "IC16") (pin "41") (pinfunction "EBIA11/AN7/ERXD0/AECRS/PMA11/RB12_41") (pintype "bidirectional"))
      (node (ref "R60") (pin "2") (pinfunction "2_2") (pintype "passive"))
    )
    (net (code "9") (name "ADC0_IN") (class "Default")
      (node (ref "R83") (pin "2") (pinfunction "2_2") (pintype "passive"))
      (node (ref "X1") (pin "P7") (pinfunction "7_P7") (pintype "passive"))
    )
    (net (code "10") (name "ADC1") (class "Default")
      (node (ref "C145") (pin "2") (pinfunction "2_2") (pintype "passive"))
      (node (ref "R19") (pin "1") (pinfunction "1_1") (pintype "passive"))
      (node (ref "R71") (pin "1") (pinfunction "1_1") (pintype "passive"))
      (node (ref "R82") (pin "2") (pinfunction "2_2") (pintype "passive"))
    )
    (net (code "11") (name "ADC1_EZ") (class "Default")
      (node (ref "C142") (pin "1") (pinfunction "1_1") (pintype "passive"))
      (node (ref "IC16") (pin "42") (pinfunction "AN8/ERXD1/AECOL/RB13_42") (pintype "bidirectional"))
      (node (ref "R71") (pin "2") (pinfunction "2_2") (pintype "passive"))
    )
    (net (code "12") (name "ADC1_IN") (class "Default")
      (node (ref "R85") (pin "2") (pinfunction "2_2") (pintype "passive"))
      (node (ref "X1") (pin "P6") (pinfunction "6_P6") (pintype "passive"))
    )
    (net (code "13") (name "ALE") (class "Default")
      (node (ref "IC13") (pin "P17") (pinfunction "ALE_P17") (pintype "bidirectional"))
      (node (ref "IC16") (pin "11") (pinfunction "EBIA4/AN13/C1INC/ECRS/RPG7/SDA4/PMA4..._11") (pintype "bidirectional"))
    )
    (net (code "14") (name "AUDIO") (class "Default")
      (node (ref "IC16") (pin "86") (pinfunction "EBID10/ETXD0/RPF1/PMD10/RF1_86") (pintype "bidirectional"))
      (node (ref "R76") (pin "2") (pinfunction "2_2") (pintype "passive"))
    )
    (net (code "15") (name "BUSY") (class "Default")
      (node (ref "IC13") (pin "P7") (pinfunction "R/B#_P7") (pintype "bidirectional"))
      (node (ref "IC16") (pin "16") (pinfunction "EBIA2/AN11/C2INC/ERXCLK/EREFCLK..._16") (pintype "bidirectional"))
      (node (ref "R80") (pin "1") (pinfunction "1_1") (pintype "passive"))
    )
    (net (code "16") (name "CE") (class "Default")
      (node (ref "IC13") (pin "P9") (pinfunction "CE#_P9") (pintype "bidirectional"))
      (node (ref "IC16") (pin "79") (pinfunction "EBID12/ETXD2/RPD12..._79") (pintype "bidirectional"))
    )
    (net (code "17") (name "CLE") (class "Default")
      (node (ref "IC13") (pin "P16") (pinfunction "CLE_P16") (pintype "bidirectional"))
      (node (ref "IC16") (pin "80") (pinfunction "EBID13/ETXD3/PMD13/RD13_80") (pintype "bidirectional"))
    )
    (net (code "18") (name "CLK_IN") (class "Default")
      (node (ref "CLKIN") (pin "4") (pinfunction "4_4") (pintype "passive"))
      (node (ref "IC22") (pin "2") (pinfunction "P$2_2") (pintype "bidirectional"))
    )
    (net (code "19") (name "CLK_SYNC") (class "Default")
      (node (ref "IC22") (pin "4") (pinfunction "P$4_4") (pintype "bidirectional"))
      (node (ref "IC25") (pin "12") (pinfunction "PC2/OC0C/RXD0_12") (pintype "bidirectional"))
    )
    (net (code "20") (name "CTS") (class "Default")
      (node (ref "IC21") (pin "11") (pinfunction "B4_11") (pintype "bidirectional"))
      (node (ref "IC25") (pin "29") (pinfunction "~XCK0OC0BSCLPE1_29") (pintype "bidirectional"))
    )
    (net (code "21") (name "D+") (class "Default")
      (node (ref "IC15") (pin "P$4") (pinfunction "IO2_P$4") (pintype "bidirectional"))
      (node (ref "IC16") (pin "55") (pinfunction "D+_55") (pintype "bidirectional"))
    )
    (net (code "22") (name "D-") (class "Default")
      (node (ref "IC15") (pin "P$6") (pinfunction "IO1_P$6") (pintype "bidirectional"))
      (node (ref "IC16") (pin "54") (pinfunction "D-_54") (pintype "bidirectional"))
    )
    (net (code "23") (name "D5V") (class "Default")
      (node (ref "C85") (pin "1") (pinfunction "1_1") (pintype "passive"))
      (node (ref "C87") (pin "1") (pinfunction "1_1") (pintype "passive"))
      (node (ref "IC14") (pin "P$2") (pinfunction "OUT_P$2") (pintype "bidirectional"))
      (node (ref "IC18") (pin "1") (pinfunction "IN_1") (pintype "bidirectional"))
      (node (ref "IC18") (pin "3") (pinfunction "EN_3") (pintype "bidirectional"))
      (node (ref "R74") (pin "2") (pinfunction "2_2") (pintype "passive"))
    )
    (net (code "24") (name "D5V0") (class "Default")
      (node (ref "C19") (pin "2") (pinfunction "2_2") (pintype "passive"))
      (node (ref "C21") (pin "2") (pinfunction "2_2") (pintype "passive"))
      (node (ref "C23") (pin "2") (pinfunction "2_2") (pintype "passive"))
      (node (ref "IC5") (pin "1") (pinfunction "OUT_1") (pintype "bidirectional"))
      (node (ref "IC5") (pin "2") (pinfunction "OUT_2") (pintype "bidirectional"))
      (node (ref "L7") (pin "1") (pinfunction "1_1") (pintype "passive"))
    )
    (net (code "25") (name "DAC_~{RST}") (class "Default")
      (node (ref "IC16") (pin "65") (pinfunction "EBIA8/RPF5/SCL5/PMA8/RF5_65") (pintype "bidirectional"))
      (node (ref "IC6") (pin "P23") (pinfunction "~{PD/RST}_P23") (pintype "bidirectional"))
      (node (ref "R20") (pin "1") (pinfunction "1_1") (pintype "passive"))
    )
    (net (code "26") (name "EN_DCDC") (class "Default")
      (node (ref "IC2") (pin "11") (pinfunction "EN2_11") (pintype "bidirectional"))
      (node (ref "IC2") (pin "9") (pinfunction "EN1_9") (pintype "bidirectional"))
      (node (ref "IC25") (pin "24") (pinfunction "~{#SSPD4}_24") (pintype "bidirectional"))
      (node (ref "R9") (pin "1") (pinfunction "1_1") (pintype "passive"))
    )
    (net (code "27") (name "EN_IN0") (class "Default")
      (node (ref "IC24") (pin "1") (pinfunction "P$1_1") (pintype "bidirectional"))
      (node (ref "IC26") (pin "6") (pinfunction "A4_6") (pintype "bidirectional"))
    )
    (net (code "28") (name "EN_N12V") (class "Default")
      (node (ref "IC16") (pin "77") (pinfunction "EBID14/ETXEN/RPD2..._77") (pintype "bidirectional"))
      (node (ref "R88") (pin "1") (pinfunction "1_1") (pintype "passive"))
    )
    (net (code "29") (name "EN_P12V") (class "Default")
      (node (ref "IC16") (pin "76") (pinfunction "RPD1/SCK1/RD1_76") (pintype "bidirectional"))
      (node (ref "R87") (pin "1") (pinfunction "1_1") (pintype "passive"))
    )
    (net (code "30") (name "FILTB") (class "Default")
      (node (ref "C28") (pin "+") (pinfunction "+_+") (pintype "passive"))
      (node (ref "C32") (pin "1") (pinfunction "1_1") (pintype "passive"))
      (node (ref "IC6") (pin "P16") (pinfunction "FILTB_P16") (pintype "bidirectional"))
    )
    (net (code "31") (name "FT_CTS") (class "Default")
      (node (ref "IC19") (pin "11") (pinfunction "~{CTS}_11") (pintype "input"))
      (node (ref "IC21") (pin "6") (pinfunction "A4_6") (pintype "bidirectional"))
    )
    (net (code "32") (name "FT_RTS") (class "Default")
      (node (ref "IC19") (pin "3") (pinfunction "~{RTS}_3") (pintype "output"))
      (node (ref "IC21") (pin "4") (pinfunction "A2_4") (pintype "bidirectional"))
    )
    (net (code "33") (name "FT_RXD") (class "Default")
      (node (ref "IC19") (pin "5") (pinfunction "RXD_5") (pintype "input"))
      (node (ref "IC21") (pin "5") (pinfunction "A3_5") (pintype "bidirectional"))
    )
    (net (code "34") (name "FT_TXD") (class "Default")
      (node (ref "IC19") (pin "1") (pinfunction "TXD_1") (pintype "output"))
      (node (ref "IC21") (pin "3") (pinfunction "A1_3") (pintype "bidirectional"))
    )
    (net (code "35") (name "GND") (class "Default")
      (node (ref "C1") (pin "2") (pinfunction "2_2") (pintype "passive"))
      (node (ref "C10") (pin "2") (pinfunction "2_2") (pintype "passive"))
      (node (ref "C100") (pin "2") (pinfunction "2_2") (pintype "passive"))
      (node (ref "C101") (pin "2") (pinfunction "2_2") (pintype "passive"))
      (node (ref "C102") (pin "2") (pinfunction "2_2") (pintype "passive"))
      (node (ref "C103") (pin "2") (pinfunction "2_2") (pintype "passive"))
      (node (ref "C104") (pin "2") (pinfunction "2_2") (pintype "passive"))
      (node (ref "C105") (pin "2") (pinfunction "2_2") (pintype "passive"))
      (node (ref "C109") (pin "1") (pinfunction "1_1") (pintype "passive"))
      (node (ref "C11") (pin "2") (pinfunction "2_2") (pintype "passive"))
      (node (ref "C110") (pin "1") (pinfunction "1_1") (pintype "passive"))
      (node (ref "C115") (pin "2") (pinfunction "2_2") (pintype "passive"))
      (node (ref "C116") (pin "2") (pinfunction "2_2") (pintype "passive"))
      (node (ref "C118") (pin "2") (pinfunction "2_2") (pintype "passive"))
      (node (ref "C119") (pin "2") (pinfunction "2_2") (pintype "passive"))
      (node (ref "C12") (pin "2") (pinfunction "2_2") (pintype "passive"))
      (node (ref "C120") (pin "2") (pinfunction "2_2") (pintype "passive"))
      (node (ref "C121") (pin "2") (pinfunction "2_2") (pintype "passive"))
      (node (ref "C122") (pin "2") (pinfunction "2_2") (pintype "passive"))
      (node (ref "C123") (pin "2") (pinfunction "2_2") (pintype "passive"))
      (node (ref "C124") (pin "2") (pinfunction "2_2") (pintype "passive"))
      (node (ref "C125") (pin "2") (pinfunction "2_2") (pintype "passive"))
      (node (ref "C126") (pin "2") (pinfunction "2_2") (pintype "passive"))
      (node (ref "C127") (pin "2") (pinfunction "2_2") (pintype "passive"))
      (node (ref "C128") (pin "2") (pinfunction "2_2") (pintype "passive"))
      (node (ref "C129") (pin "2") (pinfunction "2_2") (pintype "passive"))
      (node (ref "C13") (pin "2") (pinfunction "2_2") (pintype "passive"))
      (node (ref "C130") (pin "2") (pinfunction "2_2") (pintype "passive"))
      (node (ref "C131") (pin "2") (pinfunction "2_2") (pintype "passive"))
      (node (ref "C132") (pin "2") (pinfunction "2_2") (pintype "passive"))
      (node (ref "C133") (pin "2") (pinfunction "2_2") (pintype "passive"))
      (node (ref "C134") (pin "2") (pinfunction "2_2") (pintype "passive"))
      (node (ref "C135") (pin "2") (pinfunction "2_2") (pintype "passive"))
      (node (ref "C136") (pin "2") (pinfunction "2_2") (pintype "passive"))
      (node (ref "C137") (pin "2") (pinfunction "2_2") (pintype "passive"))
      (node (ref "C138") (pin "2") (pinfunction "2_2") (pintype "passive"))
      (node (ref "C139") (pin "2") (pinfunction "2_2") (pintype "passive"))
      (node (ref "C14") (pin "2") (pinfunction "2_2") (pintype "passive"))
      (node (ref "C140") (pin "2") (pinfunction "2_2") (pintype "passive"))
      (node (ref "C141") (pin "2") (pinfunction "2_2") (pintype "passive"))
      (node (ref "C142") (pin "2") (pinfunction "2_2") (pintype "passive"))
      (node (ref "C143") (pin "2") (pinfunction "2_2") (pintype "passive"))
      (node (ref "C144") (pin "1") (pinfunction "1_1") (pintype "passive"))
      (node (ref "C145") (pin "1") (pinfunction "1_1") (pintype "passive"))
      (node (ref "C146") (pin "2") (pinfunction "2_2") (pintype "passive"))
      (node (ref "C147") (pin "2") (pinfunction "2_2") (pintype "passive"))
      (node (ref "C148") (pin "2") (pinfunction "2_2") (pintype "passive"))
      (node (ref "C149") (pin "2") (pinfunction "2_2") (pintype "passive"))
      (node (ref "C16") (pin "2") (pinfunction "2_2") (pintype "passive"))
      (node (ref "C17") (pin "2") (pinfunction "2_2") (pintype "passive"))
      (node (ref "C18") (pin "1") (pinfunction "1_1") (pintype "passive"))
      (node (ref "C19") (pin "1") (pinfunction "1_1") (pintype "passive"))
      (node (ref "C2") (pin "-") (pinfunction "-_-") (pintype "passive"))
      (node (ref "C20") (pin "1") (pinfunction "1_1") (pintype "passive"))
      (node (ref "C21") (pin "1") (pinfunction "1_1") (pintype "passive"))
      (node (ref "C24") (pin "1") (pinfunction "1_1") (pintype "passive"))
      (node (ref "C25") (pin "1") (pinfunction "1_1") (pintype "passive"))
      (node (ref "C26") (pin "1") (pinfunction "1_1") (pintype "passive"))
      (node (ref "C27") (pin "1") (pinfunction "1_1") (pintype "passive"))
      (node (ref "C28") (pin "-") (pinfunction "-_-") (pintype "passive"))
      (node (ref "C29") (pin "2") (pinfunction "2_2") (pintype "passive"))
      (node (ref "C30") (pin "2") (pinfunction "2_2") (pintype "passive"))
      (node (ref "C31") (pin "2") (pinfunction "2_2") (pintype "passive"))
      (node (ref "C32") (pin "2") (pinfunction "2_2") (pintype "passive"))
      (node (ref "C33") (pin "-") (pinfunction "-_-") (pintype "passive"))
      (node (ref "C34") (pin "2") (pinfunction "2_2") (pintype "passive"))
      (node (ref "C35") (pin "-") (pinfunction "-_-") (pintype "passive"))
      (node (ref "C36") (pin "-") (pinfunction "-_-") (pintype "passive"))
      (node (ref "C37") (pin "2") (pinfunction "2_2") (pintype "passive"))
      (node (ref "C39") (pin "2") (pinfunction "2_2") (pintype "passive"))
      (node (ref "C4") (pin "2") (pinfunction "2_2") (pintype "passive"))
      (node (ref "C40") (pin "2") (pinfunction "2_2") (pintype "passive"))
      (node (ref "C41") (pin "2") (pinfunction "2_2") (pintype "passive"))
      (node (ref "C42") (pin "1") (pinfunction "1_1") (pintype "passive"))
      (node (ref "C45") (pin "-") (pinfunction "-_-") (pintype "passive"))
      (node (ref "C46") (pin "+") (pinfunction "+_+") (pintype "passive"))
      (node (ref "C47") (pin "2") (pinfunction "2_2") (pintype "passive"))
      (node (ref "C48") (pin "2") (pinfunction "2_2") (pintype "passive"))
      (node (ref "C49") (pin "2") (pinfunction "2_2") (pintype "passive"))
      (node (ref "C5") (pin "2") (pinfunction "2_2") (pintype "passive"))
      (node (ref "C50") (pin "1") (pinfunction "1_1") (pintype "passive"))
      (node (ref "C51") (pin "2") (pinfunction "2_2") (pintype "passive"))
      (node (ref "C52") (pin "-") (pinfunction "-_-") (pintype "passive"))
      (node (ref "C53") (pin "+") (pinfunction "+_+") (pintype "passive"))
      (node (ref "C55") (pin "2") (pinfunction "2_2") (pintype "passive"))
      (node (ref "C56") (pin "1") (pinfunction "1_1") (pintype "passive"))
      (node (ref "C57") (pin "2") (pinfunction "2_2") (pintype "passive"))
      (node (ref "C58") (pin "-") (pinfunction "-_-") (pintype "passive"))
      (node (ref "C59") (pin "+") (pinfunction "+_+") (pintype "passive"))
      (node (ref "C6") (pin "2") (pinfunction "2_2") (pintype "passive"))
      (node (ref "C60") (pin "-") (pinfunction "-_-") (pintype "passive"))
      (node (ref "C61") (pin "2") (pinfunction "2_2") (pintype "passive"))
      (node (ref "C63") (pin "2") (pinfunction "2_2") (pintype "passive"))
      (node (ref "C64") (pin "2") (pinfunction "2_2") (pintype "passive"))
      (node (ref "C65") (pin "2") (pinfunction "2_2") (pintype "passive"))
      (node (ref "C66") (pin "1") (pinfunction "1_1") (pintype "passive"))
      (node (ref "C69") (pin "-") (pinfunction "-_-") (pintype "passive"))
      (node (ref "C7") (pin "2") (pinfunction "2_2") (pintype "passive"))
      (node (ref "C70") (pin "+") (pinfunction "+_+") (pintype "passive"))
      (node (ref "C71") (pin "2") (pinfunction "2_2") (pintype "passive"))
      (node (ref "C72") (pin "2") (pinfunction "2_2") (pintype "passive"))
      (node (ref "C73") (pin "2") (pinfunction "2_2") (pintype "passive"))
      (node (ref "C74") (pin "1") (pinfunction "1_1") (pintype "passive"))
      (node (ref "C75") (pin "2") (pinfunction "2_2") (pintype "passive"))
      (node (ref "C76") (pin "-") (pinfunction "-_-") (pintype "passive"))
      (node (ref "C77") (pin "+") (pinfunction "+_+") (pintype "passive"))
      (node (ref "C79") (pin "2") (pinfunction "2_2") (pintype "passive"))
      (node (ref "C8") (pin "2") (pinfunction "2_2") (pintype "passive"))
      (node (ref "C80") (pin "1") (pinfunction "1_1") (pintype "passive"))
      (node (ref "C81") (pin "2") (pinfunction "2_2") (pintype "passive"))
      (node (ref "C82") (pin "-") (pinfunction "-_-") (pintype "passive"))
      (node (ref "C83") (pin "+") (pinfunction "+_+") (pintype "passive"))
      (node (ref "C84") (pin "2") (pinfunction "2_2") (pintype "passive"))
      (node (ref "C85") (pin "2") (pinfunction "2_2") (pintype "passive"))
      (node (ref "C86") (pin "2") (pinfunction "2_2") (pintype "passive"))
      (node (ref "C87") (pin "2") (pinfunction "2_2") (pintype "passive"))
      (node (ref "C88") (pin "2") (pinfunction "2_2") (pintype "passive"))
      (node (ref "C89") (pin "2") (pinfunction "2_2") (pintype "passive"))
      (node (ref "C9") (pin "2") (pinfunction "2_2") (pintype "passive"))
      (node (ref "C90") (pin "1") (pinfunction "1_1") (pintype "passive"))
      (node (ref "C91") (pin "1") (pinfunction "1_1") (pintype "passive"))
      (node (ref "C92") (pin "2") (pinfunction "2_2") (pintype "passive"))
      (node (ref "C93") (pin "2") (pinfunction "2_2") (pintype "passive"))
      (node (ref "C94") (pin "2") (pinfunction "2_2") (pintype "passive"))
      (node (ref "C95") (pin "2") (pinfunction "2_2") (pintype "passive"))
      (node (ref "C96") (pin "2") (pinfunction "2_2") (pintype "passive"))
      (node (ref "C97") (pin "2") (pinfunction "2_2") (pintype "passive"))
      (node (ref "C98") (pin "2") (pinfunction "2_2") (pintype "passive"))
      (node (ref "C99") (pin "2") (pinfunction "2_2") (pintype "passive"))
      (node (ref "CLKIN") (pin "5") (pinfunction "5_5") (pintype "passive"))
      (node (ref "CUSB1") (pin "2") (pinfunction "2_2") (pintype "passive"))
      (node (ref "EMI") (pin "P$1") (pinfunction "O_P$1") (pintype "power_in"))
      (node (ref "EMI") (pin "P$10") (pinfunction "O_P$10") (pintype "power_in"))
      (node (ref "EMI") (pin "P$11") (pinfunction "O_P$11") (pintype "power_in"))
      (node (ref "EMI") (pin "P$12") (pinfunction "O_P$12") (pintype "power_in"))
      (node (ref "EMI") (pin "P$2") (pinfunction "O_P$2") (pintype "power_in"))
      (node (ref "EMI") (pin "P$3") (pinfunction "O_P$3") (pintype "power_in"))
      (node (ref "EMI") (pin "P$4") (pinfunction "O_P$4") (pintype "power_in"))
      (node (ref "EMI") (pin "P$5") (pinfunction "O_P$5") (pintype "power_in"))
      (node (ref "EMI") (pin "P$6") (pinfunction "O_P$6") (pintype "power_in"))
      (node (ref "EMI") (pin "P$7") (pinfunction "O_P$7") (pintype "power_in"))
      (node (ref "EMI") (pin "P$8") (pinfunction "O_P$8") (pintype "power_in"))
      (node (ref "EMI") (pin "P$9") (pinfunction "O_P$9") (pintype "power_in"))
      (node (ref "GND") (pin "TP") (pinfunction "TP_TP") (pintype "input"))
      (node (ref "GND174") (pin "TP") (pinfunction "TP_TP") (pintype "input"))
      (node (ref "GND176") (pin "TP") (pinfunction "TP_TP") (pintype "input"))
      (node (ref "IC1") (pin "2") (pinfunction "GND_2") (pintype "bidirectional"))
      (node (ref "IC13") (pin "P13") (pinfunction "VSS_P13") (pintype "bidirectional"))
      (node (ref "IC13") (pin "P25") (pinfunction "VSS_P25") (pintype "bidirectional"))
      (node (ref "IC13") (pin "P36") (pinfunction "VSS_P36") (pintype "bidirectional"))
      (node (ref "IC13") (pin "P48") (pinfunction "VSS_P48") (pintype "bidirectional"))
      (node (ref "IC14") (pin "P$3") (pinfunction "GND_P$3") (pintype "bidirectional"))
      (node (ref "IC14") (pin "P$6") (pinfunction "GND_T_P$6") (pintype "bidirectional"))
      (node (ref "IC15") (pin "P$2") (pinfunction "GND_P$2") (pintype "bidirectional"))
      (node (ref "IC16") (pin "13") (pinfunction "VSS_13") (pintype "input"))
      (node (ref "IC16") (pin "31") (pinfunction "AVSS_31") (pintype "bidirectional"))
      (node (ref "IC16") (pin "36") (pinfunction "VSS_36") (pintype "bidirectional"))
      (node (ref "IC16") (pin "45") (pinfunction "VSS_45") (pintype "bidirectional"))
      (node (ref "IC16") (pin "53") (pinfunction "VSS_53") (pintype "bidirectional"))
      (node (ref "IC16") (pin "63") (pinfunction "VSS_63") (pintype "bidirectional"))
      (node (ref "IC16") (pin "75") (pinfunction "VSS_75") (pintype "bidirectional"))
      (node (ref "IC16") (pin "84") (pinfunction "VSS_84") (pintype "bidirectional"))
      (node (ref "IC16") (pin "92") (pinfunction "VSS_92") (pintype "input"))
      (node (ref "IC18") (pin "2") (pinfunction "GND_2") (pintype "bidirectional"))
      (node (ref "IC2") (pin "1") (pinfunction "PGND_1") (pintype "bidirectional"))
      (node (ref "IC2") (pin "15") (pinfunction "AGND_15") (pintype "bidirectional"))
      (node (ref "IC2") (pin "4") (pinfunction "SYNC/FREQ_4") (pintype "bidirectional"))
      (node (ref "IC2") (pin "6") (pinfunction "SLEW_6") (pintype "bidirectional"))
      (node (ref "IC2") (pin "EPAD") (pinfunction "PGND_EPAD") (pintype "bidirectional"))
      (node (ref "IC20") (pin "2") (pinfunction "GND_2") (pintype "bidirectional"))
      (node (ref "IC21") (pin "15") (pinfunction "GND2_15") (pintype "bidirectional"))
      (node (ref "IC21") (pin "9") (pinfunction "GND2_9") (pintype "bidirectional"))
      (node (ref "IC22") (pin "1") (pinfunction "P$1_1") (pintype "bidirectional"))
      (node (ref "IC22") (pin "3") (pinfunction "P$3_3") (pintype "bidirectional"))
      (node (ref "IC23") (pin "1") (pinfunction "P$1_1") (pintype "bidirectional"))
      (node (ref "IC23") (pin "3") (pinfunction "P$3_3") (pintype "bidirectional"))
      (node (ref "IC24") (pin "3") (pinfunction "P$3_3") (pintype "bidirectional"))
      (node (ref "IC25") (pin "18") (pinfunction "GND_18") (pintype "power_in"))
      (node (ref "IC25") (pin "30") (pinfunction "GND_30") (pintype "power_in"))
      (node (ref "IC25") (pin "38") (pinfunction "GND_38") (pintype "power_in"))
      (node (ref "IC25") (pin "7") (pinfunction "PB3/ADC11/DAC1_7") (pintype "bidirectional"))
      (node (ref "IC25") (pin "8") (pinfunction "GND_8") (pintype "power_in"))
      (node (ref "IC26") (pin "2") (pinfunction "GND1_2") (pintype "bidirectional"))
      (node (ref "IC26") (pin "3") (pinfunction "A1_3") (pintype "bidirectional"))
      (node (ref "IC26") (pin "8") (pinfunction "GND1_8") (pintype "bidirectional"))
      (node (ref "IC27") (pin "4") (pinfunction "GND_4") (pintype "bidirectional"))
      (node (ref "IC28") (pin "1") (pinfunction "P$1_1") (pintype "bidirectional"))
      (node (ref "IC28") (pin "3") (pinfunction "P$3_3") (pintype "bidirectional"))
      (node (ref "IC29") (pin "1") (pinfunction "P$1_1") (pintype "bidirectional"))
      (node (ref "IC29") (pin "3") (pinfunction "P$3_3") (pintype "bidirectional"))
      (node (ref "IC3") (pin "1") (pinfunction "GND_1") (pintype "bidirectional"))
      (node (ref "IC30") (pin "1") (pinfunction "P$1_1") (pintype "bidirectional"))
      (node (ref "IC30") (pin "3") (pinfunction "P$3_3") (pintype "bidirectional"))
      (node (ref "IC31") (pin "1") (pinfunction "P$1_1") (pintype "bidirectional"))
      (node (ref "IC31") (pin "3") (pinfunction "P$3_3") (pintype "bidirectional"))
      (node (ref "IC32") (pin "P$3") (pinfunction "GND_P$3") (pintype "bidirectional"))
      (node (ref "IC32") (pin "P$6") (pinfunction "GND_T_P$6") (pintype "bidirectional"))
      (node (ref "IC33") (pin "3") (pinfunction "GND_3") (pintype "bidirectional"))
      (node (ref "IC34") (pin "3") (pinfunction "GND_3") (pintype "bidirectional"))
      (node (ref "IC35") (pin "3") (pinfunction "GND_3") (pintype "bidirectional"))
      (node (ref "IC37") (pin "2") (pinfunction "V-_2") (pintype "power_in"))
      (node (ref "IC38") (pin "2") (pinfunction "V-_2") (pintype "power_in"))
      (node (ref "IC4") (pin "4") (pinfunction "GND_4") (pintype "bidirectional"))
      (node (ref "IC5") (pin "4") (pinfunction "GND_4") (pintype "bidirectional"))
      (node (ref "IC6") (pin "P10") (pinfunction "AGND_P10") (pintype "bidirectional"))
      (node (ref "IC6") (pin "P19") (pinfunction "AGND_P19") (pintype "bidirectional"))
      (node (ref "IC6") (pin "P28") (pinfunction "DGND_P28") (pintype "bidirectional"))
      (node (ref "IC6") (pin "P9") (pinfunction "DSD_PHASE_P9") (pintype "bidirectional"))
      (node (ref "IN") (pin "2") (pinfunction "2_2") (pintype "passive"))
      (node (ref "IN1") (pin "2") (pinfunction "S_2") (pintype "passive"))
      (node (ref "J3") (pin "P1") (pinfunction "1_P1") (pintype "passive"))
      (node (ref "J4") (pin "P1") (pinfunction "1_P1") (pintype "passive"))
      (node (ref "JACK") (pin "P2") (pinfunction "2_P2") (pintype "passive"))
      (node (ref "JACK") (pin "P3") (pinfunction "3_P3") (pintype "passive"))
      (node (ref "JP1") (pin "3") (pinfunction "3_3") (pintype "passive"))
      (node (ref "L3") (pin "2") (pinfunction "2_2") (pintype "passive"))
      (node (ref "LED1") (pin "K") (pinfunction "K_K") (pintype "bidirectional"))
      (node (ref "LED2") (pin "K") (pinfunction "K_K") (pintype "bidirectional"))
      (node (ref "LED3") (pin "K") (pinfunction "K_K") (pintype "bidirectional"))
      (node (ref "OSC1") (pin "P$2") (pinfunction "GND_P$2") (pintype "passive"))
      (node (ref "OSC2") (pin "P$2") (pinfunction "GND_P$2") (pintype "passive"))
      (node (ref "OSC3") (pin "P$2") (pinfunction "GND_P$2") (pintype "bidirectional"))
      (node (ref "OUT") (pin "2") (pinfunction "2_2") (pintype "passive"))
      (node (ref "OUT1") (pin "2") (pinfunction "S_2") (pintype "passive"))
      (node (ref "PDI") (pin "6") (pinfunction "6_6") (pintype "passive"))
      (node (ref "R15") (pin "2") (pinfunction "2_2") (pintype "passive"))
      (node (ref "R18") (pin "1") (pinfunction "1_1") (pintype "passive"))
      (node (ref "R20") (pin "2") (pinfunction "2_2") (pintype "passive"))
      (node (ref "R22") (pin "1") (pinfunction "1_1") (pintype "passive"))
      (node (ref "R3") (pin "2") (pinfunction "2_2") (pintype "passive"))
      (node (ref "R34") (pin "1") (pinfunction "1_1") (pintype "passive"))
      (node (ref "R50") (pin "1") (pinfunction "1_1") (pintype "passive"))
      (node (ref "R55") (pin "1") (pinfunction "1_1") (pintype "passive"))
      (node (ref "R61") (pin "2") (pinfunction "2_2") (pintype "passive"))
      (node (ref "R67") (pin "2") (pinfunction "2_2") (pintype "passive"))
      (node (ref "R68") (pin "2") (pinfunction "2_2") (pintype "passive"))
      (node (ref "R7") (pin "2") (pinfunction "2_2") (pintype "passive"))
      (node (ref "R72") (pin "1") (pinfunction "1_1") (pintype "passive"))
      (node (ref "R78") (pin "2") (pinfunction "2_2") (pintype "passive"))
      (node (ref "R79") (pin "2") (pinfunction "2_2") (pintype "passive"))
      (node (ref "R84") (pin "1") (pinfunction "1_1") (pintype "passive"))
      (node (ref "R86") (pin "1") (pinfunction "1_1") (pintype "passive"))
      (node (ref "R89") (pin "2") (pinfunction "2_2") (pintype "passive"))
      (node (ref "RUSB1") (pin "2") (pinfunction "2_2") (pintype "passive"))
      (node (ref "STATE") (pin "K") (pinfunction "K_K") (pintype "bidirectional"))
      (node (ref "SW1") (pin "P") (pinfunction "P_P") (pintype "passive"))
      (node (ref "USB1") (pin "P$5") (pinfunction "5_P$5") (pintype "bidirectional"))
      (node (ref "X1") (pin "P1") (pinfunction "1_P1") (pintype "passive"))
      (node (ref "X1") (pin "P5") (pinfunction "5_P5") (pintype "passive"))
      (node (ref "X1") (pin "P8") (pinfunction "8_P8") (pintype "passive"))
    )
    (net (code "36") (name "GND2") (class "Default")
      (node (ref "C106") (pin "2") (pinfunction "2_2") (pintype "passive"))
      (node (ref "C107") (pin "2") (pinfunction "2_2") (pintype "passive"))
      (node (ref "C108") (pin "2") (pinfunction "2_2") (pintype "passive"))
      (node (ref "C111") (pin "2") (pinfunction "2_2") (pintype "passive"))
      (node (ref "C112") (pin "-") (pinfunction "-_-") (pintype "passive"))
      (node (ref "C113") (pin "2") (pinfunction "2_2") (pintype "passive"))
      (node (ref "C114") (pin "2") (pinfunction "2_2") (pintype "passive"))
      (node (ref "C117") (pin "2") (pinfunction "2_2") (pintype "passive"))
      (node (ref "CUSB2") (pin "2") (pinfunction "2_2") (pintype "passive"))
      (node (ref "IC17") (pin "P$2") (pinfunction "GND_P$2") (pintype "bidirectional"))
      (node (ref "IC19") (pin "18") (pinfunction "GND_18") (pintype "power_in"))
      (node (ref "IC19") (pin "21") (pinfunction "GND_21") (pintype "power_in"))
      (node (ref "IC19") (pin "25") (pinfunction "GND_25") (pintype "power_in"))
      (node (ref "IC19") (pin "26") (pinfunction "TEST_26") (pintype "input"))
      (node (ref "IC19") (pin "7") (pinfunction "GND_7") (pintype "power_in"))
      (node (ref "IC21") (pin "2") (pinfunction "GND1_2") (pintype "bidirectional"))
      (node (ref "IC21") (pin "8") (pinfunction "GND1_8") (pintype "bidirectional"))
      (node (ref "RUSB2") (pin "2") (pinfunction "2_2") (pintype "passive"))
      (node (ref "USB2") (pin "P$5") (pinfunction "5_P$5") (pintype "bidirectional"))
    )
    (net (code "37") (name "GNDIO") (class "Default")
      (node (ref "IC26") (pin "15") (pinfunction "GND2_15") (pintype "bidirectional"))
      (node (ref "IC26") (pin "9") (pinfunction "GND2_9") (pintype "bidirectional"))
      (node (ref "J1") (pin "5") (pinfunction "5_5") (pintype "passive"))
    )
    (net (code "38") (name "IN00{slash}TRIG") (class "Default")
      (node (ref "IC16") (pin "71") (pinfunction "EMDIO/AEMDIO/RPD0/RTCC/INT0/RD0_71") (pintype "bidirectional"))
      (node (ref "IC24") (pin "4") (pinfunction "P$4_4") (pintype "bidirectional"))
      (node (ref "IC25") (pin "4") (pinfunction "PB0/ADC8/AREF_4") (pintype "bidirectional"))
      (node (ref "R63") (pin "1") (pinfunction "1_1") (pintype "passive"))
    )
    (net (code "39") (name "IN01") (class "Default")
      (node (ref "IC25") (pin "20") (pinfunction "~{OC0APD0}_20") (pintype "bidirectional"))
      (node (ref "R69") (pin "2") (pinfunction "2_2") (pintype "passive"))
    )
    (net (code "40") (name "IN1") (class "Default")
      (node (ref "IC30") (pin "2") (pinfunction "P$2_2") (pintype "bidirectional"))
      (node (ref "R67") (pin "1") (pinfunction "1_1") (pintype "passive"))
      (node (ref "X1") (pin "P10") (pinfunction "10_P10") (pintype "passive"))
    )
    (net (code "41") (name "IN02") (class "Default")
      (node (ref "IC25") (pin "10") (pinfunction "PC0/OC0A/SDA_10") (pintype "bidirectional"))
      (node (ref "R70") (pin "2") (pinfunction "2_2") (pintype "passive"))
    )
    (net (code "42") (name "IN2") (class "Default")
      (node (ref "IC31") (pin "2") (pinfunction "P$2_2") (pintype "bidirectional"))
      (node (ref "R68") (pin "1") (pinfunction "1_1") (pintype "passive"))
      (node (ref "X1") (pin "P9") (pinfunction "9_P9") (pintype "passive"))
    )
    (net (code "43") (name "IN_RJ") (class "Default")
      (node (ref "IC26") (pin "13") (pinfunction "B2_13") (pintype "bidirectional"))
      (node (ref "J1") (pin "1") (pinfunction "1_1") (pintype "passive"))
    )
    (net (code "44") (name "IOUTL+") (class "Default")
      (node (ref "C62") (pin "1") (pinfunction "1_1") (pintype "passive"))
      (node (ref "IC10") (pin "2") (pinfunction "-IN_2") (pintype "input"))
      (node (ref "IC6") (pin "P18") (pinfunction "IOUTL+_P18") (pintype "bidirectional"))
      (node (ref "R39") (pin "1") (pinfunction "1_1") (pintype "passive"))
      (node (ref "R43") (pin "1") (pinfunction "1_1") (pintype "passive"))
      (node (ref "R45") (pin "1") (pinfunction "1_1") (pintype "passive"))
    )
    (net (code "45") (name "IOUTL-") (class "Default")
      (node (ref "C62") (pin "2") (pinfunction "2_2") (pintype "passive"))
      (node (ref "IC11") (pin "2") (pinfunction "-IN_2") (pintype "input"))
      (node (ref "IC6") (pin "P17") (pinfunction "IOUTL-_P17") (pintype "bidirectional"))
      (node (ref "R42") (pin "1") (pinfunction "1_1") (pintype "passive"))
      (node (ref "R44") (pin "1") (pinfunction "1_1") (pintype "passive"))
      (node (ref "R46") (pin "1") (pinfunction "1_1") (pintype "passive"))
    )
    (net (code "46") (name "IOUTR+") (class "Default")
      (node (ref "C38") (pin "1") (pinfunction "1_1") (pintype "passive"))
      (node (ref "IC6") (pin "P11") (pinfunction "IOUTR+_P11") (pintype "bidirectional"))
      (node (ref "IC7") (pin "2") (pinfunction "-IN_2") (pintype "input"))
      (node (ref "R23") (pin "1") (pinfunction "1_1") (pintype "passive"))
      (node (ref "R27") (pin "1") (pinfunction "1_1") (pintype "passive"))
      (node (ref "R29") (pin "1") (pinfunction "1_1") (pintype "passive"))
    )
    (net (code "47") (name "IOUTR-") (class "Default")
      (node (ref "C38") (pin "2") (pinfunction "2_2") (pintype "passive"))
      (node (ref "IC6") (pin "P12") (pinfunction "IOUTR-_P12") (pintype "bidirectional"))
      (node (ref "IC8") (pin "2") (pinfunction "-IN_2") (pintype "input"))
      (node (ref "R26") (pin "1") (pinfunction "1_1") (pintype "passive"))
      (node (ref "R28") (pin "1") (pinfunction "1_1") (pintype "passive"))
      (node (ref "R30") (pin "1") (pinfunction "1_1") (pintype "passive"))
    )
    (net (code "48") (name "MEMORY") (class "Default")
      (node (ref "IC16") (pin "95") (pinfunction "TRD2/SQID2/RG14_95") (pintype "bidirectional"))
      (node (ref "R75") (pin "2") (pinfunction "2_2") (pintype "passive"))
    )
    (net (code "49") (name "MUTE") (class "Default")
      (node (ref "IC16") (pin "57") (pinfunction "EBIRDY3/RPF2/SDA3/RF2_57") (pintype "bidirectional"))
      (node (ref "IC6") (pin "P22") (pinfunction "MUTE_P22") (pintype "bidirectional"))
    )
    (net (code "50") (name "Net-(C3-Pad1)") (class "Default")
      (node (ref "C3") (pin "1") (pinfunction "1_1") (pintype "passive"))
      (node (ref "R4") (pin "2") (pinfunction "2_2") (pintype "passive"))
    )
    (net (code "51") (name "Net-(C6-Pad1)") (class "Default")
      (node (ref "C6") (pin "1") (pinfunction "1_1") (pintype "passive"))
      (node (ref "D1") (pin "C") (pinfunction "C_C") (pintype "passive"))
      (node (ref "L1") (pin "2") (pinfunction "2_2") (pintype "passive"))
      (node (ref "R5") (pin "1") (pinfunction "1_1") (pintype "passive"))
    )
    (net (code "52") (name "Net-(C7-Pad1)") (class "Default")
      (node (ref "C7") (pin "1") (pinfunction "1_1") (pintype "passive"))
      (node (ref "R8") (pin "2") (pinfunction "2_2") (pintype "passive"))
    )
    (net (code "53") (name "Net-(C12-Pad1)") (class "Default")
      (node (ref "C12") (pin "1") (pinfunction "1_1") (pintype "passive"))
      (node (ref "R13") (pin "1") (pinfunction "1_1") (pintype "passive"))
    )
    (net (code "54") (name "Net-(C13-Pad1)") (class "Default")
      (node (ref "C13") (pin "1") (pinfunction "1_1") (pintype "passive"))
      (node (ref "D2") (pin "A") (pinfunction "A_A") (pintype "passive"))
      (node (ref "L4") (pin "1") (pinfunction "1_1") (pintype "passive"))
      (node (ref "R17") (pin "2") (pinfunction "2_2") (pintype "passive"))
    )
    (net (code "55") (name "Net-(C15-Pad1)") (class "Default")
      (node (ref "C15") (pin "1") (pinfunction "1_1") (pintype "passive"))
      (node (ref "R16") (pin "2") (pinfunction "2_2") (pintype "passive"))
    )
    (net (code "56") (name "Net-(C43-Pad1)") (class "Default")
      (node (ref "C43") (pin "1") (pinfunction "1_1") (pintype "passive"))
      (node (ref "R27") (pin "2") (pinfunction "2_2") (pintype "passive"))
    )
    (net (code "57") (name "Net-(C44-Pad1)") (class "Default")
      (node (ref "C44") (pin "1") (pinfunction "1_1") (pintype "passive"))
      (node (ref "R28") (pin "2") (pinfunction "2_2") (pintype "passive"))
    )
    (net (code "58") (name "Net-(C47-Pad1)") (class "Default")
      (node (ref "C47") (pin "1") (pinfunction "1_1") (pintype "passive"))
      (node (ref "R31") (pin "2") (pinfunction "2_2") (pintype "passive"))
      (node (ref "R33") (pin "1") (pinfunction "1_1") (pintype "passive"))
      (node (ref "R35") (pin "1") (pinfunction "1_1") (pintype "passive"))
    )
    (net (code "59") (name "Net-(C48-Pad1)") (class "Default")
      (node (ref "C48") (pin "1") (pinfunction "1_1") (pintype "passive"))
      (node (ref "R32") (pin "2") (pinfunction "2_2") (pintype "passive"))
      (node (ref "R34") (pin "2") (pinfunction "2_2") (pintype "passive"))
      (node (ref "R36") (pin "1") (pinfunction "1_1") (pintype "passive"))
    )
    (net (code "60") (name "Net-(C54-Pad1)") (class "Default")
      (node (ref "C54") (pin "1") (pinfunction "1_1") (pintype "passive"))
      (node (ref "R37") (pin "2") (pinfunction "2_2") (pintype "passive"))
    )
    (net (code "61") (name "Net-(C67-Pad1)") (class "Default")
      (node (ref "C67") (pin "1") (pinfunction "1_1") (pintype "passive"))
      (node (ref "R43") (pin "2") (pinfunction "2_2") (pintype "passive"))
    )
    (net (code "62") (name "Net-(C68-Pad1)") (class "Default")
      (node (ref "C68") (pin "1") (pinfunction "1_1") (pintype "passive"))
      (node (ref "R44") (pin "2") (pinfunction "2_2") (pintype "passive"))
    )
    (net (code "63") (name "Net-(C71-Pad1)") (class "Default")
      (node (ref "C71") (pin "1") (pinfunction "1_1") (pintype "passive"))
      (node (ref "R47") (pin "2") (pinfunction "2_2") (pintype "passive"))
      (node (ref "R49") (pin "1") (pinfunction "1_1") (pintype "passive"))
      (node (ref "R51") (pin "1") (pinfunction "1_1") (pintype "passive"))
    )
    (net (code "64") (name "Net-(C72-Pad1)") (class "Default")
      (node (ref "C72") (pin "1") (pinfunction "1_1") (pintype "passive"))
      (node (ref "R48") (pin "2") (pinfunction "2_2") (pintype "passive"))
      (node (ref "R50") (pin "2") (pinfunction "2_2") (pintype "passive"))
      (node (ref "R52") (pin "1") (pinfunction "1_1") (pintype "passive"))
    )
    (net (code "65") (name "Net-(C78-Pad1)") (class "Default")
      (node (ref "C78") (pin "1") (pinfunction "1_1") (pintype "passive"))
      (node (ref "R53") (pin "2") (pinfunction "2_2") (pintype "passive"))
    )
    (net (code "66") (name "Net-(C101-Pad1)") (class "Default")
      (node (ref "C101") (pin "1") (pinfunction "1_1") (pintype "passive"))
      (node (ref "R56") (pin "1") (pinfunction "1_1") (pintype "passive"))
      (node (ref "R57") (pin "2") (pinfunction "2_2") (pintype "passive"))
    )
    (net (code "67") (name "Net-(IC1-ADJ)") (class "Default")
      (node (ref "IC1") (pin "4") (pinfunction "ADJ_4") (pintype "bidirectional"))
      (node (ref "R1") (pin "2") (pinfunction "2_2") (pintype "passive"))
      (node (ref "R2") (pin "2") (pinfunction "2_2") (pintype "passive"))
      (node (ref "R3") (pin "1") (pinfunction "1_1") (pintype "passive"))
      (node (ref "R4") (pin "1") (pinfunction "1_1") (pintype "passive"))
    )
    (net (code "68") (name "Net-(IC1-EN)") (class "Default")
      (node (ref "C148") (pin "1") (pinfunction "1_1") (pintype "passive"))
      (node (ref "IC1") (pin "3") (pinfunction "EN_3") (pintype "bidirectional"))
      (node (ref "R79") (pin "1") (pinfunction "1_1") (pintype "passive"))
      (node (ref "R87") (pin "2") (pinfunction "2_2") (pintype "passive"))
    )
    (net (code "69") (name "Net-(IC2-COMP1)") (class "Default")
      (node (ref "C8") (pin "1") (pinfunction "1_1") (pintype "passive"))
      (node (ref "IC2") (pin "8") (pinfunction "COMP1_8") (pintype "bidirectional"))
      (node (ref "R8") (pin "1") (pinfunction "1_1") (pintype "passive"))
    )
    (net (code "70") (name "Net-(IC2-COMP2)") (class "Default")
      (node (ref "C10") (pin "1") (pinfunction "1_1") (pintype "passive"))
      (node (ref "IC2") (pin "12") (pinfunction "COMP2_12") (pintype "bidirectional"))
      (node (ref "R13") (pin "2") (pinfunction "2_2") (pintype "passive"))
    )
    (net (code "71") (name "Net-(IC2-FB1)") (class "Default")
      (node (ref "IC2") (pin "7") (pinfunction "FB1_7") (pintype "bidirectional"))
      (node (ref "R6") (pin "1") (pinfunction "1_1") (pintype "passive"))
      (node (ref "R7") (pin "1") (pinfunction "1_1") (pintype "passive"))
    )
    (net (code "72") (name "Net-(IC2-FB2)") (class "Default")
      (node (ref "IC2") (pin "13") (pinfunction "FB2_13") (pintype "bidirectional"))
      (node (ref "R10") (pin "2") (pinfunction "2_2") (pintype "passive"))
      (node (ref "R12") (pin "2") (pinfunction "2_2") (pintype "passive"))
    )
    (net (code "73") (name "Net-(IC2-INBK)") (class "Default")
      (node (ref "IC2") (pin "3") (pinfunction "INBK_3") (pintype "bidirectional"))
      (node (ref "L2") (pin "2") (pinfunction "2_2") (pintype "passive"))
    )
    (net (code "74") (name "Net-(IC2-SW1)") (class "Default")
      (node (ref "D1") (pin "A") (pinfunction "A_A") (pintype "passive"))
      (node (ref "IC2") (pin "2") (pinfunction "SW1_2") (pintype "bidirectional"))
      (node (ref "L2") (pin "1") (pinfunction "1_1") (pintype "passive"))
    )
    (net (code "75") (name "Net-(IC2-SW2)") (class "Default")
      (node (ref "D2") (pin "C") (pinfunction "C_C") (pintype "passive"))
      (node (ref "IC2") (pin "20") (pinfunction "SW2_20") (pintype "bidirectional"))
      (node (ref "L3") (pin "1") (pinfunction "1_1") (pintype "passive"))
    )
    (net (code "76") (name "Net-(IC2-VREF)") (class "Default")
      (node (ref "C137") (pin "1") (pinfunction "1_1") (pintype "passive"))
      (node (ref "IC2") (pin "14") (pinfunction "VREF_14") (pintype "bidirectional"))
      (node (ref "R10") (pin "1") (pinfunction "1_1") (pintype "passive"))
    )
    (net (code "77") (name "Net-(IC2-VREG)") (class "Default")
      (node (ref "C14") (pin "1") (pinfunction "1_1") (pintype "passive"))
      (node (ref "IC2") (pin "16") (pinfunction "VREG_16") (pintype "bidirectional"))
    )
    (net (code "78") (name "Net-(IC3-ADJ)") (class "Default")
      (node (ref "IC3") (pin "4") (pinfunction "ADJ_4") (pintype "bidirectional"))
      (node (ref "R11") (pin "2") (pinfunction "2_2") (pintype "passive"))
      (node (ref "R14") (pin "2") (pinfunction "2_2") (pintype "passive"))
      (node (ref "R15") (pin "1") (pinfunction "1_1") (pintype "passive"))
      (node (ref "R16") (pin "1") (pinfunction "1_1") (pintype "passive"))
    )
    (net (code "79") (name "Net-(IC3-EN)") (class "Default")
      (node (ref "C149") (pin "1") (pinfunction "1_1") (pintype "passive"))
      (node (ref "IC3") (pin "3") (pinfunction "EN_3") (pintype "bidirectional"))
      (node (ref "R78") (pin "1") (pinfunction "1_1") (pintype "passive"))
      (node (ref "R88") (pin "2") (pinfunction "2_2") (pintype "passive"))
    )
    (net (code "80") (name "Net-(IC4-NR)") (class "Default")
      (node (ref "C22") (pin "1") (pinfunction "1_1") (pintype "passive"))
      (node (ref "IC4") (pin "3") (pinfunction "NR_3") (pintype "bidirectional"))
    )
    (net (code "81") (name "Net-(IC4-~{SD})") (class "Default")
      (node (ref "C24") (pin "2") (pinfunction "2_2") (pintype "passive"))
      (node (ref "C26") (pin "2") (pinfunction "2_2") (pintype "passive"))
      (node (ref "IC4") (pin "5") (pinfunction "~{SD}_5") (pintype "bidirectional"))
      (node (ref "IC4") (pin "7") (pinfunction "IN_7") (pintype "bidirectional"))
      (node (ref "IC4") (pin "8") (pinfunction "IN_8") (pintype "bidirectional"))
      (node (ref "L5") (pin "2") (pinfunction "2_2") (pintype "passive"))
    )
    (net (code "82") (name "Net-(IC5-NR)") (class "Default")
      (node (ref "C23") (pin "1") (pinfunction "1_1") (pintype "passive"))
      (node (ref "IC5") (pin "3") (pinfunction "NR_3") (pintype "bidirectional"))
    )
    (net (code "83") (name "Net-(IC5-~{SD})") (class "Default")
      (node (ref "C25") (pin "2") (pinfunction "2_2") (pintype "passive"))
      (node (ref "C27") (pin "2") (pinfunction "2_2") (pintype "passive"))
      (node (ref "IC5") (pin "5") (pinfunction "~{SD}_5") (pintype "bidirectional"))
      (node (ref "IC5") (pin "7") (pinfunction "IN_7") (pintype "bidirectional"))
      (node (ref "IC5") (pin "8") (pinfunction "IN_8") (pintype "bidirectional"))
      (node (ref "L6") (pin "2") (pinfunction "2_2") (pintype "passive"))
    )
    (net (code "84") (name "Net-(IC6-AVDD)") (class "Default")
      (node (ref "C31") (pin "1") (pinfunction "1_1") (pintype "passive"))
      (node (ref "IC6") (pin "P15") (pinfunction "AVDD_P15") (pintype "bidirectional"))
      (node (ref "L8") (pin "2") (pinfunction "2_2") (pintype "passive"))
    )
    (net (code "85") (name "Net-(IC6-DVDD)") (class "Default")
      (node (ref "C30") (pin "1") (pinfunction "1_1") (pintype "passive"))
      (node (ref "IC6") (pin "P1") (pinfunction "DVDD_P1") (pintype "bidirectional"))
      (node (ref "L7") (pin "2") (pinfunction "2_2") (pintype "passive"))
    )
    (net (code "86") (name "Net-(IC6-FILTR)") (class "Default")
      (node (ref "C29") (pin "1") (pinfunction "1_1") (pintype "passive"))
      (node (ref "C33") (pin "+") (pinfunction "+_+") (pintype "passive"))
      (node (ref "IC6") (pin "P13") (pinfunction "FILTR_P13") (pintype "bidirectional"))
    )
    (net (code "87") (name "Net-(IC6-IREF)") (class "Default")
      (node (ref "IC6") (pin "P14") (pinfunction "IREF_P14") (pintype "bidirectional"))
      (node (ref "R18") (pin "2") (pinfunction "2_2") (pintype "passive"))
    )
    (net (code "88") (name "Net-(IC7-+IN)") (class "Default")
      (node (ref "C39") (pin "1") (pinfunction "1_1") (pintype "passive"))
      (node (ref "IC7") (pin "3") (pinfunction "+IN_3") (pintype "input"))
      (node (ref "R24") (pin "1") (pinfunction "1_1") (pintype "passive"))
    )
    (net (code "89") (name "Net-(IC7-OUT)") (class "Default")
      (node (ref "C43") (pin "2") (pinfunction "2_2") (pintype "passive"))
      (node (ref "IC7") (pin "6") (pinfunction "OUT_6") (pintype "output"))
      (node (ref "R29") (pin "2") (pinfunction "2_2") (pintype "passive"))
      (node (ref "R31") (pin "1") (pinfunction "1_1") (pintype "passive"))
    )
    (net (code "90") (name "Net-(IC8-+IN)") (class "Default")
      (node (ref "C40") (pin "1") (pinfunction "1_1") (pintype "passive"))
      (node (ref "IC8") (pin "3") (pinfunction "+IN_3") (pintype "input"))
      (node (ref "R25") (pin "1") (pinfunction "1_1") (pintype "passive"))
    )
    (net (code "91") (name "Net-(IC8-OUT)") (class "Default")
      (node (ref "C44") (pin "2") (pinfunction "2_2") (pintype "passive"))
      (node (ref "IC8") (pin "6") (pinfunction "OUT_6") (pintype "output"))
      (node (ref "R30") (pin "2") (pinfunction "2_2") (pintype "passive"))
      (node (ref "R32") (pin "1") (pinfunction "1_1") (pintype "passive"))
    )
    (net (code "92") (name "Net-(IC9-+IN)") (class "Default")
      (node (ref "C51") (pin "1") (pinfunction "1_1") (pintype "passive"))
      (node (ref "IC9") (pin "3") (pinfunction "+IN_3") (pintype "input"))
      (node (ref "R36") (pin "2") (pinfunction "2_2") (pintype "passive"))
    )
    (net (code "93") (name "Net-(IC9--IN)") (class "Default")
      (node (ref "IC9") (pin "2") (pinfunction "-IN_2") (pintype "input"))
      (node (ref "R35") (pin "2") (pinfunction "2_2") (pintype "passive"))
      (node (ref "R37") (pin "1") (pinfunction "1_1") (pintype "passive"))
    )
    (net (code "94") (name "Net-(IC9-OUT)") (class "Default")
      (node (ref "C54") (pin "2") (pinfunction "2_2") (pintype "passive"))
      (node (ref "IC9") (pin "6") (pinfunction "OUT_6") (pintype "output"))
      (node (ref "R33") (pin "2") (pinfunction "2_2") (pintype "passive"))
      (node (ref "R38") (pin "1") (pinfunction "1_1") (pintype "passive"))
    )
    (net (code "95") (name "Net-(IC10-+IN)") (class "Default")
      (node (ref "C63") (pin "1") (pinfunction "1_1") (pintype "passive"))
      (node (ref "IC10") (pin "3") (pinfunction "+IN_3") (pintype "input"))
      (node (ref "R40") (pin "1") (pinfunction "1_1") (pintype "passive"))
    )
    (net (code "96") (name "Net-(IC10-OUT)") (class "Default")
      (node (ref "C67") (pin "2") (pinfunction "2_2") (pintype "passive"))
      (node (ref "IC10") (pin "6") (pinfunction "OUT_6") (pintype "output"))
      (node (ref "R45") (pin "2") (pinfunction "2_2") (pintype "passive"))
      (node (ref "R47") (pin "1") (pinfunction "1_1") (pintype "passive"))
    )
    (net (code "97") (name "Net-(IC11-+IN)") (class "Default")
      (node (ref "C64") (pin "1") (pinfunction "1_1") (pintype "passive"))
      (node (ref "IC11") (pin "3") (pinfunction "+IN_3") (pintype "input"))
      (node (ref "R41") (pin "1") (pinfunction "1_1") (pintype "passive"))
    )
    (net (code "98") (name "Net-(IC11-OUT)") (class "Default")
      (node (ref "C68") (pin "2") (pinfunction "2_2") (pintype "passive"))
      (node (ref "IC11") (pin "6") (pinfunction "OUT_6") (pintype "output"))
      (node (ref "R46") (pin "2") (pinfunction "2_2") (pintype "passive"))
      (node (ref "R48") (pin "1") (pinfunction "1_1") (pintype "passive"))
    )
    (net (code "99") (name "Net-(IC12-+IN)") (class "Default")
      (node (ref "C75") (pin "1") (pinfunction "1_1") (pintype "passive"))
      (node (ref "IC12") (pin "3") (pinfunction "+IN_3") (pintype "input"))
      (node (ref "R52") (pin "2") (pinfunction "2_2") (pintype "passive"))
    )
    (net (code "100") (name "Net-(IC12--IN)") (class "Default")
      (node (ref "IC12") (pin "2") (pinfunction "-IN_2") (pintype "input"))
      (node (ref "R51") (pin "2") (pinfunction "2_2") (pintype "passive"))
      (node (ref "R53") (pin "1") (pinfunction "1_1") (pintype "passive"))
    )
    (net (code "101") (name "Net-(IC12-OUT)") (class "Default")
      (node (ref "C78") (pin "2") (pinfunction "2_2") (pintype "passive"))
      (node (ref "IC12") (pin "6") (pinfunction "OUT_6") (pintype "output"))
      (node (ref "R49") (pin "2") (pinfunction "2_2") (pintype "passive"))
      (node (ref "R54") (pin "1") (pinfunction "1_1") (pintype "passive"))
    )
    (net (code "102") (name "Net-(IC14-EN)") (class "Default")
      (node (ref "C90") (pin "2") (pinfunction "2_2") (pintype "passive"))
      (node (ref "C91") (pin "2") (pinfunction "2_2") (pintype "passive"))
      (node (ref "IC14") (pin "P$1") (pinfunction "IN_P$1") (pintype "bidirectional"))
      (node (ref "IC14") (pin "P$5") (pinfunction "EN_P$5") (pintype "bidirectional"))
      (node (ref "L9") (pin "2") (pinfunction "2_2") (pintype "passive"))
    )
    (net (code "103") (name "Net-(IC14-NR{slash}FB)") (class "Default")
      (node (ref "IC14") (pin "P$4") (pinfunction "NR/FB_P$4") (pintype "bidirectional"))
      (node (ref "R55") (pin "2") (pinfunction "2_2") (pintype "passive"))
      (node (ref "R74") (pin "1") (pinfunction "1_1") (pintype "passive"))
    )
    (net (code "104") (name "Net-(IC15-VBUS)") (class "Default")
      (node (ref "C138") (pin "1") (pinfunction "1_1") (pintype "passive"))
      (node (ref "IC15") (pin "P$5") (pinfunction "VBUS_P$5") (pintype "bidirectional"))
      (node (ref "L13") (pin "2") (pinfunction "2_2") (pintype "passive"))
      (node (ref "USB1") (pin "P$1") (pinfunction "1_P$1") (pintype "bidirectional"))
    )
    (net (code "105") (name "Net-(IC16-OSC1{slash}CLKI{slash}RC12)") (class "Default")
      (node (ref "IC16") (pin "49") (pinfunction "OSC1/CLKI/RC12_49") (pintype "bidirectional"))
      (node (ref "OSC1") (pin "P$3") (pinfunction "OUTPUT_P$3") (pintype "passive"))
    )
    (net (code "106") (name "Net-(IC16-SOSCO{slash}RPC14{slash}T1CK{slash}RC14)") (class "Default")
      (node (ref "IC16") (pin "73") (pinfunction "SOSCO/RPC14/T1CK/RC14_73") (pintype "bidirectional"))
      (node (ref "OSC3") (pin "P$3") (pinfunction "OUT_P$3") (pintype "bidirectional"))
    )
    (net (code "107") (name "Net-(IC17-VBUS)") (class "Default")
      (node (ref "C106") (pin "1") (pinfunction "1_1") (pintype "passive"))
      (node (ref "IC17") (pin "P$5") (pinfunction "VBUS_P$5") (pintype "bidirectional"))
      (node (ref "L10") (pin "2") (pinfunction "2_2") (pintype "passive"))
      (node (ref "USB2") (pin "P$1") (pinfunction "1_P$1") (pintype "bidirectional"))
    )
    (net (code "108") (name "Net-(IC19-3V3OUT)") (class "Default")
      (node (ref "C113") (pin "1") (pinfunction "1_1") (pintype "passive"))
      (node (ref "IC19") (pin "17") (pinfunction "3V3OUT_17") (pintype "output"))
    )
    (net (code "109") (name "Net-(IC19-CBUS0)") (class "Default")
      (node (ref "IC19") (pin "23") (pinfunction "CBUS0_23") (pintype "bidirectional"))
      (node (ref "TX") (pin "K") (pinfunction "K_K") (pintype "bidirectional"))
    )
    (net (code "110") (name "Net-(IC19-CBUS1)") (class "Default")
      (node (ref "IC19") (pin "22") (pinfunction "CBUS1_22") (pintype "bidirectional"))
      (node (ref "RX") (pin "K") (pinfunction "K_K") (pintype "bidirectional"))
    )
    (net (code "111") (name "Net-(IC24-P$2)") (class "Default")
      (node (ref "IC24") (pin "2") (pinfunction "P$2_2") (pintype "bidirectional"))
      (node (ref "IN") (pin "1") (pinfunction "1_1") (pintype "passive"))
      (node (ref "IN1") (pin "1") (pinfunction "S_1") (pintype "passive"))
      (node (ref "R61") (pin "1") (pinfunction "1_1") (pintype "passive"))
    )
    (net (code "112") (name "Net-(IC25-AVCC)") (class "Default")
      (node (ref "C131") (pin "1") (pinfunction "1_1") (pintype "passive"))
      (node (ref "IC25") (pin "39") (pinfunction "AVCC_39") (pintype "power_in"))
      (node (ref "L12") (pin "1") (pinfunction "1_1") (pintype "passive"))
    )
    (net (code "113") (name "Net-(IC25-PB1{slash}ADC9)") (class "Default")
      (node (ref "C140") (pin "1") (pinfunction "1_1") (pintype "passive"))
      (node (ref "IC25") (pin "5") (pinfunction "PB1/ADC9_5") (pintype "bidirectional"))
      (node (ref "R19") (pin "2") (pinfunction "2_2") (pintype "passive"))
    )
    (net (code "114") (name "Net-(IC25-PB2{slash}ADC10{slash}DAC0)") (class "Default")
      (node (ref "C122") (pin "1") (pinfunction "1_1") (pintype "passive"))
      (node (ref "IC25") (pin "6") (pinfunction "PB2/ADC10/DAC0_6") (pintype "bidirectional"))
      (node (ref "R62") (pin "2") (pinfunction "2_2") (pintype "passive"))
    )
    (net (code "115") (name "Net-(IC25-PR1{slash}XTAL1)") (class "Default")
      (node (ref "IC25") (pin "37") (pinfunction "PR1/XTAL1_37") (pintype "bidirectional"))
      (node (ref "OSC2") (pin "P$3") (pinfunction "OUTPUT_P$3") (pintype "passive"))
    )
    (net (code "116") (name "Net-(IC26-A3)") (class "Default")
      (node (ref "IC26") (pin "5") (pinfunction "A3_5") (pintype "bidirectional"))
      (node (ref "R63") (pin "2") (pinfunction "2_2") (pintype "passive"))
    )
    (net (code "117") (name "Net-(IC30-P$4)") (class "Default")
      (node (ref "IC30") (pin "4") (pinfunction "P$4_4") (pintype "bidirectional"))
      (node (ref "R69") (pin "1") (pinfunction "1_1") (pintype "passive"))
    )
    (net (code "118") (name "Net-(IC31-P$4)") (class "Default")
      (node (ref "IC31") (pin "4") (pinfunction "P$4_4") (pintype "bidirectional"))
      (node (ref "R70") (pin "1") (pinfunction "1_1") (pintype "passive"))
    )
    (net (code "119") (name "Net-(IC32-EN)") (class "Default")
      (node (ref "C109") (pin "2") (pinfunction "2_2") (pintype "passive"))
      (node (ref "C110") (pin "2") (pinfunction "2_2") (pintype "passive"))
      (node (ref "IC32") (pin "P$1") (pinfunction "IN_P$1") (pintype "bidirectional"))
      (node (ref "IC32") (pin "P$5") (pinfunction "EN_P$5") (pintype "bidirectional"))
      (node (ref "L11") (pin "2") (pinfunction "2_2") (pintype "passive"))
    )
    (net (code "120") (name "Net-(IC32-NR{slash}FB)") (class "Default")
      (node (ref "IC32") (pin "P$4") (pinfunction "NR/FB_P$4") (pintype "bidirectional"))
      (node (ref "R72") (pin "2") (pinfunction "2_2") (pintype "passive"))
      (node (ref "R73") (pin "1") (pinfunction "1_1") (pintype "passive"))
    )
    (net (code "121") (name "Net-(IC37-+IN)") (class "Default")
      (node (ref "IC37") (pin "3") (pinfunction "+IN_3") (pintype "input"))
      (node (ref "R83") (pin "1") (pinfunction "1_1") (pintype "passive"))
      (node (ref "R84") (pin "2") (pinfunction "2_2") (pintype "passive"))
    )
    (net (code "122") (name "Net-(IC37--IN)") (class "Default")
      (node (ref "IC37") (pin "1") (pinfunction "OUT_1") (pintype "output"))
      (node (ref "IC37") (pin "4") (pinfunction "-IN_4") (pintype "input"))
      (node (ref "R81") (pin "1") (pinfunction "1_1") (pintype "passive"))
    )
    (net (code "123") (name "Net-(IC38-+IN)") (class "Default")
      (node (ref "IC38") (pin "3") (pinfunction "+IN_3") (pintype "input"))
      (node (ref "R85") (pin "1") (pinfunction "1_1") (pintype "passive"))
      (node (ref "R86") (pin "2") (pinfunction "2_2") (pintype "passive"))
    )
    (net (code "124") (name "Net-(IC38--IN)") (class "Default")
      (node (ref "IC38") (pin "1") (pinfunction "OUT_1") (pintype "output"))
      (node (ref "IC38") (pin "4") (pinfunction "-IN_4") (pintype "input"))
      (node (ref "R82") (pin "1") (pinfunction "1_1") (pintype "passive"))
    )
    (net (code "125") (name "Net-(LED1-PadA)") (class "Default")
      (node (ref "LED1") (pin "A") (pinfunction "A_A") (pintype "bidirectional"))
      (node (ref "R75") (pin "1") (pinfunction "1_1") (pintype "passive"))
    )
    (net (code "126") (name "Net-(LED2-PadA)") (class "Default")
      (node (ref "LED2") (pin "A") (pinfunction "A_A") (pintype "bidirectional"))
      (node (ref "R76") (pin "1") (pinfunction "1_1") (pintype "passive"))
    )
    (net (code "127") (name "Net-(LED3-PadA)") (class "Default")
      (node (ref "LED3") (pin "A") (pinfunction "A_A") (pintype "bidirectional"))
      (node (ref "R77") (pin "1") (pinfunction "1_1") (pintype "passive"))
    )
    (net (code "128") (name "Net-(R58-Pad1)") (class "Default")
      (node (ref "R58") (pin "1") (pinfunction "1_1") (pintype "passive"))
      (node (ref "TX") (pin "A") (pinfunction "A_A") (pintype "bidirectional"))
    )
    (net (code "129") (name "Net-(R59-Pad1)") (class "Default")
      (node (ref "R59") (pin "1") (pinfunction "1_1") (pintype "passive"))
      (node (ref "RX") (pin "A") (pinfunction "A_A") (pintype "bidirectional"))
    )
    (net (code "130") (name "Net-(R66-Pad1)") (class "Default")
      (node (ref "R66") (pin "1") (pinfunction "1_1") (pintype "passive"))
      (node (ref "STATE") (pin "A") (pinfunction "A_A") (pintype "bidirectional"))
    )
    (net (code "131") (name "Net-(USB1-2)") (class "Default")
      (node (ref "IC15") (pin "P$1") (pinfunction "IO1_P$1") (pintype "bidirectional"))
      (node (ref "USB1") (pin "P$2") (pinfunction "2_P$2") (pintype "bidirectional"))
    )
    (net (code "132") (name "Net-(USB1-3)") (class "Default")
      (node (ref "IC15") (pin "P$3") (pinfunction "IO2_P$3") (pintype "bidirectional"))
      (node (ref "USB1") (pin "P$3") (pinfunction "3_P$3") (pintype "bidirectional"))
    )
    (net (code "133") (name "Net-(USB1-P$1)") (class "Default")
      (node (ref "RUSB1") (pin "1") (pinfunction "1_1") (pintype "passive"))
      (node (ref "USB1") (pin "SHIELD_3") (pinfunction "P$1_SHIELD_3") (pintype "bidirectional"))
    )
    (net (code "134") (name "Net-(USB1-P$4)") (class "Default")
      (node (ref "CUSB1") (pin "1") (pinfunction "1_1") (pintype "passive"))
      (node (ref "USB1") (pin "SHIELD_4") (pinfunction "P$4_SHIELD_4") (pintype "bidirectional"))
    )
    (net (code "135") (name "Net-(USB2-2)") (class "Default")
      (node (ref "IC17") (pin "P$1") (pinfunction "IO1_P$1") (pintype "bidirectional"))
      (node (ref "USB2") (pin "P$2") (pinfunction "2_P$2") (pintype "bidirectional"))
    )
    (net (code "136") (name "Net-(USB2-3)") (class "Default")
      (node (ref "IC17") (pin "P$3") (pinfunction "IO2_P$3") (pintype "bidirectional"))
      (node (ref "USB2") (pin "P$3") (pinfunction "3_P$3") (pintype "bidirectional"))
    )
    (net (code "137") (name "Net-(USB2-P$1)") (class "Default")
      (node (ref "RUSB2") (pin "1") (pinfunction "1_1") (pintype "passive"))
      (node (ref "USB2") (pin "SHIELD_1") (pinfunction "P$1_SHIELD_1") (pintype "bidirectional"))
    )
    (net (code "138") (name "Net-(USB2-P$4)") (class "Default")
      (node (ref "CUSB2") (pin "1") (pinfunction "1_1") (pintype "passive"))
      (node (ref "USB2") (pin "SHIELD_4") (pinfunction "P$4_SHIELD_4") (pintype "bidirectional"))
    )
    (net (code "139") (name "OUT00{slash}SYNC") (class "Default")
      (node (ref "IC16") (pin "22") (pinfunction "AN3/C2INA/RPB3/RB3_22") (pintype "bidirectional"))
      (node (ref "IC23") (pin "2") (pinfunction "P$2_2") (pintype "bidirectional"))
      (node (ref "IC25") (pin "21") (pinfunction "~OC0BXCK0PD1_21") (pintype "bidirectional"))
      (node (ref "IC26") (pin "4") (pinfunction "A2_4") (pintype "bidirectional"))
    )
    (net (code "140") (name "OUT1") (class "Default")
      (node (ref "IC28") (pin "4") (pinfunction "P$4_4") (pintype "bidirectional"))
      (node (ref "X1") (pin "P4") (pinfunction "4_P4") (pintype "passive"))
    )
    (net (code "141") (name "OUT01") (class "Default")
      (node (ref "IC25") (pin "13") (pinfunction "PC3/OC0D/TXD0_13") (pintype "bidirectional"))
      (node (ref "IC28") (pin "2") (pinfunction "P$2_2") (pintype "bidirectional"))
    )
    (net (code "142") (name "OUT2") (class "Default")
      (node (ref "IC29") (pin "4") (pinfunction "P$4_4") (pintype "bidirectional"))
      (node (ref "X1") (pin "P3") (pinfunction "3_P3") (pintype "passive"))
    )
    (net (code "143") (name "OUT02") (class "Default")
      (node (ref "IC25") (pin "14") (pinfunction "PC4/OC1A/#SS_14") (pintype "bidirectional"))
      (node (ref "IC29") (pin "2") (pinfunction "P$2_2") (pintype "bidirectional"))
    )
    (net (code "144") (name "OUTL") (class "Default")
      (node (ref "C57") (pin "1") (pinfunction "1_1") (pintype "passive"))
      (node (ref "J3") (pin "P2") (pinfunction "2_P2") (pintype "passive"))
      (node (ref "R38") (pin "2") (pinfunction "2_2") (pintype "passive"))
    )
    (net (code "145") (name "OUTR") (class "Default")
      (node (ref "C81") (pin "1") (pinfunction "1_1") (pintype "passive"))
      (node (ref "J4") (pin "P2") (pinfunction "2_P2") (pintype "passive"))
      (node (ref "R54") (pin "2") (pinfunction "2_2") (pintype "passive"))
    )
    (net (code "146") (name "OUT_BNC") (class "Default")
      (node (ref "IC23") (pin "4") (pinfunction "P$4_4") (pintype "bidirectional"))
      (node (ref "OUT") (pin "1") (pinfunction "1_1") (pintype "passive"))
      (node (ref "OUT1") (pin "1") (pinfunction "S_1") (pintype "passive"))
    )
    (net (code "147") (name "OUT_RJ") (class "Default")
      (node (ref "IC26") (pin "12") (pinfunction "B3_12") (pintype "bidirectional"))
      (node (ref "J1") (pin "3") (pinfunction "3_3") (pintype "passive"))
    )
    (net (code "148") (name "PAR0") (class "Default")
      (node (ref "IC16") (pin "17") (pinfunction "TMS/EBIA16/AN24/RA0_17") (pintype "bidirectional"))
      (node (ref "IC25") (pin "40") (pinfunction "PA0/ADC0/AREF_40") (pintype "bidirectional"))
    )
    (net (code "149") (name "PAR1") (class "Default")
      (node (ref "IC16") (pin "38") (pinfunction "TCK/EBIA19/AN29/RA1_38") (pintype "bidirectional"))
      (node (ref "IC25") (pin "41") (pinfunction "PA1/ADC1_41") (pintype "bidirectional"))
    )
    (net (code "150") (name "PAR2") (class "Default")
      (node (ref "IC16") (pin "59") (pinfunction "~{EBICS0}/SCL2/RA2_59") (pintype "bidirectional"))
      (node (ref "IC25") (pin "42") (pinfunction "PA2/ADC2_42") (pintype "bidirectional"))
    )
    (net (code "151") (name "PAR3") (class "Default")
      (node (ref "IC16") (pin "60") (pinfunction "EBIRDY1/SDA2/RA3_60") (pintype "bidirectional"))
      (node (ref "IC25") (pin "43") (pinfunction "PA3/ADC3_43") (pintype "bidirectional"))
    )
    (net (code "152") (name "PAR4") (class "Default")
      (node (ref "IC16") (pin "61") (pinfunction "EBIA14/PMCS1/PMA14/RA4_61") (pintype "bidirectional"))
      (node (ref "IC25") (pin "44") (pinfunction "PA4/ADC4_44") (pintype "bidirectional"))
    )
    (net (code "153") (name "PAR5") (class "Default")
      (node (ref "IC16") (pin "2") (pinfunction "EBIA5/AN34/PMA5/RA5_2") (pintype "bidirectional"))
      (node (ref "IC25") (pin "1") (pinfunction "PA5/ADC5_1") (pintype "bidirectional"))
    )
    (net (code "154") (name "PAR6") (class "Default")
      (node (ref "IC16") (pin "89") (pinfunction "TRCLK/SQICLK/RA6_89") (pintype "bidirectional"))
      (node (ref "IC25") (pin "2") (pinfunction "PA6/ADC6_2") (pintype "bidirectional"))
    )
    (net (code "155") (name "PAR7") (class "Default")
      (node (ref "IC16") (pin "90") (pinfunction "TRD3/SQID3/RA7_90") (pintype "bidirectional"))
      (node (ref "IC25") (pin "3") (pinfunction "PA7/ADC7/AC0-OUT_3") (pintype "bidirectional"))
    )
    (net (code "156") (name "PDI-CLK") (class "Default")
      (node (ref "IC25") (pin "35") (pinfunction "RESET/PDI-CLK_35") (pintype "input"))
      (node (ref "PDI") (pin "5") (pinfunction "5_5") (pintype "passive"))
    )
    (net (code "157") (name "PDI-DATA") (class "Default")
      (node (ref "IC25") (pin "34") (pinfunction "PDI-DATA_34") (pintype "bidirectional"))
      (node (ref "PDI") (pin "1") (pinfunction "1_1") (pintype "passive"))
    )
    (net (code "158") (name "PGEC2") (class "Default")
      (node (ref "IC16") (pin "26") (pinfunction "PGEC2/AN46/RPB6/RB6_26") (pintype "bidirectional"))
      (node (ref "JP1") (pin "5") (pinfunction "5_5") (pintype "passive"))
    )
    (net (code "159") (name "PGED2") (class "Default")
      (node (ref "IC16") (pin "27") (pinfunction "PGED2/AN47/RPB7/RB7_27") (pintype "bidirectional"))
      (node (ref "JP1") (pin "4") (pinfunction "4_4") (pintype "passive"))
    )
    (net (code "160") (name "PMD0") (class "Default")
      (node (ref "IC13") (pin "P29") (pinfunction "I/O0_P29") (pintype "bidirectional"))
      (node (ref "IC16") (pin "91") (pinfunction "EBID0/PMD0/RE0_91") (pintype "bidirectional"))
    )
    (net (code "161") (name "PMD1") (class "Default")
      (node (ref "IC13") (pin "P30") (pinfunction "I/O1_P30") (pintype "bidirectional"))
      (node (ref "IC16") (pin "94") (pinfunction "EBID1/PMD1/RE1_94") (pintype "bidirectional"))
    )
    (net (code "162") (name "PMD2") (class "Default")
      (node (ref "IC13") (pin "P31") (pinfunction "I/O2_P31") (pintype "bidirectional"))
      (node (ref "IC16") (pin "98") (pinfunction "EBID2/PMD2/RE2_98") (pintype "bidirectional"))
    )
    (net (code "163") (name "PMD3") (class "Default")
      (node (ref "IC13") (pin "P32") (pinfunction "I/O3_P32") (pintype "bidirectional"))
      (node (ref "IC16") (pin "99") (pinfunction "EBID3/RPE3/PMD3/RE3_99") (pintype "bidirectional"))
    )
    (net (code "164") (name "PMD4") (class "Default")
      (node (ref "IC13") (pin "P41") (pinfunction "I/O4_P41") (pintype "bidirectional"))
      (node (ref "IC16") (pin "100") (pinfunction "EBID4/AN18/PMD4/RE4_100") (pintype "bidirectional"))
    )
    (net (code "165") (name "PMD5") (class "Default")
      (node (ref "IC13") (pin "P42") (pinfunction "I/O5_P42") (pintype "bidirectional"))
      (node (ref "IC16") (pin "3") (pinfunction "EBID5/AN17/RPE5/PMD5/RE5_3") (pintype "bidirectional"))
    )
    (net (code "166") (name "PMD6") (class "Default")
      (node (ref "IC13") (pin "P43") (pinfunction "I/O6_P43") (pintype "bidirectional"))
      (node (ref "IC16") (pin "4") (pinfunction "EBID6/AN16/PMD6/RE6_4") (pintype "bidirectional"))
    )
    (net (code "167") (name "PMD7") (class "Default")
      (node (ref "IC13") (pin "P44") (pinfunction "I/O7_P44") (pintype "bidirectional"))
      (node (ref "IC16") (pin "5") (pinfunction "EBID7/AN15/PMD7/RE7_5") (pintype "bidirectional"))
    )
    (net (code "168") (name "PMD8") (class "Default")
      (node (ref "IC13") (pin "P26") (pinfunction "I/O8_P26") (pintype "bidirectional"))
    )
    (net (code "169") (name "PMD9") (class "Default")
      (node (ref "IC13") (pin "P27") (pinfunction "I/O9_P27") (pintype "bidirectional"))
    )
    (net (code "170") (name "PMD10") (class "Default")
      (node (ref "IC13") (pin "P28") (pinfunction "I/O10_P28") (pintype "bidirectional"))
    )
    (net (code "171") (name "PMD11") (class "Default")
      (node (ref "IC13") (pin "P33") (pinfunction "I/O11_P33") (pintype "bidirectional"))
    )
    (net (code "172") (name "PMD12") (class "Default")
      (node (ref "IC13") (pin "P40") (pinfunction "I/O12_P40") (pintype "bidirectional"))
    )
    (net (code "173") (name "PMD13") (class "Default")
      (node (ref "IC13") (pin "P45") (pinfunction "I/O13_P45") (pintype "bidirectional"))
    )
    (net (code "174") (name "PMD14") (class "Default")
      (node (ref "IC13") (pin "P46") (pinfunction "I/O14_P46") (pintype "bidirectional"))
    )
    (net (code "175") (name "PMD15") (class "Default")
      (node (ref "IC13") (pin "P47") (pinfunction "I/O15_P47") (pintype "bidirectional"))
    )
    (net (code "176") (name "RE") (class "Default")
      (node (ref "IC13") (pin "P8") (pinfunction "RE#_P8") (pintype "bidirectional"))
      (node (ref "IC16") (pin "9") (pinfunction "~{EBIOE}/AN19/RPC4/PMRD/RC4_9") (pintype "bidirectional"))
    )
    (net (code "177") (name "REFCLK{slash}MCLK") (class "Default")
      (node (ref "IC16") (pin "72") (pinfunction "SOSCI/RPC13/RC13_72") (pintype "bidirectional"))
      (node (ref "IC6") (pin "P27") (pinfunction "MCLK_P27") (pintype "bidirectional"))
      (node (ref "JP3") (pin "4") (pinfunction "4_4") (pintype "passive"))
    )
    (net (code "178") (name "RTS") (class "Default")
      (node (ref "IC21") (pin "13") (pinfunction "B2_13") (pintype "bidirectional"))
      (node (ref "IC25") (pin "28") (pinfunction "~{OC0ASDAPE0}_28") (pintype "bidirectional"))
    )
    (net (code "179") (name "RXD") (class "Default")
      (node (ref "IC21") (pin "12") (pinfunction "B3_12") (pintype "bidirectional"))
      (node (ref "IC34") (pin "4") (pinfunction "OUT_4") (pintype "bidirectional"))
      (node (ref "IC35") (pin "4") (pinfunction "OUT_4") (pintype "bidirectional"))
    )
    (net (code "180") (name "RXD_") (class "Default")
      (node (ref "IC25") (pin "33") (pinfunction "~TXD0OC0DPE3_33") (pintype "bidirectional"))
      (node (ref "IC35") (pin "2") (pinfunction "IN_2") (pintype "bidirectional"))
    )
    (net (code "181") (name "SCK1") (class "Default")
      (node (ref "IC16") (pin "34") (pinfunction "EBIA13/CVREFOUT/AN5/RPB10/PMA13/RB10_34") (pintype "bidirectional"))
      (node (ref "IC6") (pin "P26") (pinfunction "CCLK_P26") (pintype "bidirectional"))
    )
    (net (code "182") (name "SCK{slash}BIT_CLK") (class "Default")
      (node (ref "IC16") (pin "69") (pinfunction "RPD10/SCK4/RD10_69") (pintype "bidirectional"))
      (node (ref "IC6") (pin "P3") (pinfunction "BCLK/EF_BCLK_P3") (pintype "bidirectional"))
      (node (ref "JP3") (pin "2") (pinfunction "2_2") (pintype "passive"))
    )
    (net (code "183") (name "SDO1") (class "Default")
      (node (ref "IC16") (pin "33") (pinfunction "EBIA7/AN49/RPB9/PMA7/RB9_33") (pintype "bidirectional"))
      (node (ref "IC6") (pin "P24") (pinfunction "CDATA_P24") (pintype "bidirectional"))
    )
    (net (code "184") (name "SDO{slash}SD") (class "Default")
      (node (ref "IC16") (pin "70") (pinfunction "EMDC/AEMDC/RPD11/RD11_70") (pintype "bidirectional"))
      (node (ref "IC6") (pin "P4") (pinfunction "SDATA/EF_LDATA_P4") (pintype "bidirectional"))
      (node (ref "JP3") (pin "1") (pinfunction "1_1") (pintype "passive"))
    )
    (net (code "185") (name "SS{slash}WORD_CLK") (class "Default")
      (node (ref "IC16") (pin "68") (pinfunction "EBIA15/RPD9/PMCS2/PMA15/RD9_68") (pintype "bidirectional"))
      (node (ref "IC6") (pin "P2") (pinfunction "LRCLK/EF-WCLK_P2") (pintype "bidirectional"))
      (node (ref "JP3") (pin "3") (pinfunction "3_3") (pintype "passive"))
    )
    (net (code "186") (name "STATE") (class "Default")
      (node (ref "IC25") (pin "36") (pinfunction "PR0/XTAL2_36") (pintype "bidirectional"))
      (node (ref "R66") (pin "2") (pinfunction "2_2") (pintype "passive"))
    )
    (net (code "187") (name "TP0") (class "Default")
      (node (ref "IC16") (pin "96") (pinfunction "TRD1/SQID1/RG12_96") (pintype "bidirectional"))
      (node (ref "TP0") (pin "TP") (pinfunction "TP_TP") (pintype "input"))
    )
    (net (code "188") (name "TP1") (class "Default")
      (node (ref "IC16") (pin "97") (pinfunction "TRD0/SQID0/RG13_97") (pintype "bidirectional"))
      (node (ref "TP1") (pin "TP") (pinfunction "TP_TP") (pintype "input"))
    )
    (net (code "189") (name "TXD") (class "Default")
      (node (ref "IC21") (pin "14") (pinfunction "B1_14") (pintype "bidirectional"))
      (node (ref "IC25") (pin "32") (pinfunction "~RXD0OC0CPE2_32") (pintype "bidirectional"))
      (node (ref "IC33") (pin "2") (pinfunction "IN_2") (pintype "bidirectional"))
    )
    (net (code "190") (name "UART1_RX") (class "Default")
      (node (ref "IC25") (pin "23") (pinfunction "~OC0DTXD0PD3_23") (pintype "bidirectional"))
      (node (ref "IC27") (pin "3") (pinfunction "D_3") (pintype "bidirectional"))
    )
    (net (code "191") (name "UART1_TX") (class "Default")
      (node (ref "IC25") (pin "22") (pinfunction "~OC0CRXD0PD2_22") (pintype "bidirectional"))
      (node (ref "IC27") (pin "2") (pinfunction "R_2") (pintype "bidirectional"))
    )
    (net (code "192") (name "UART2_RX") (class "Default")
      (node (ref "IC16") (pin "7") (pinfunction "EBIA12/AN21/RPC2/PMA12/RC2_7") (pintype "bidirectional"))
      (node (ref "IC25") (pin "26") (pinfunction "~RXD1MISOPD6_26") (pintype "bidirectional"))
      (node (ref "IC33") (pin "4") (pinfunction "OUT_4") (pintype "bidirectional"))
    )
    (net (code "193") (name "UART2_TX") (class "Default")
      (node (ref "IC16") (pin "25") (pinfunction "PGED1/AN0/RPB0/RB0_25") (pintype "bidirectional"))
      (node (ref "IC25") (pin "27") (pinfunction "~~{TXD1SCKCLKOPD7}_27") (pintype "bidirectional"))
      (node (ref "IC34") (pin "2") (pinfunction "IN_2") (pintype "bidirectional"))
    )
    (net (code "194") (name "UART_RX") (class "Default")
      (node (ref "IC27") (pin "8") (pinfunction "A_8") (pintype "bidirectional"))
      (node (ref "J2") (pin "1") (pinfunction "1_1") (pintype "passive"))
      (node (ref "R64") (pin "2") (pinfunction "2_2") (pintype "passive"))
    )
    (net (code "195") (name "UART_TX") (class "Default")
      (node (ref "IC27") (pin "5") (pinfunction "Y_5") (pintype "bidirectional"))
      (node (ref "J2") (pin "4") (pinfunction "4_4") (pintype "passive"))
      (node (ref "R65") (pin "1") (pinfunction "1_1") (pintype "passive"))
    )
    (net (code "196") (name "UC_IO0") (class "Default")
      (node (ref "IC16") (pin "20") (pinfunction "AN45/C1INA/RPB5/RB5_20") (pintype "bidirectional"))
      (node (ref "IC25") (pin "11") (pinfunction "PC1/OC0B/XCK0/SCL_11") (pintype "bidirectional"))
    )
    (net (code "197") (name "UC_IO1") (class "Default")
      (node (ref "IC16") (pin "21") (pinfunction "AN4/C1INB/RB4_21") (pintype "bidirectional"))
      (node (ref "IC25") (pin "15") (pinfunction "PC5/OC1B/MOSI/XCK1_15") (pintype "bidirectional"))
    )
    (net (code "198") (name "UC_IO2") (class "Default")
      (node (ref "IC16") (pin "10") (pinfunction "AN14/C1IND/ECOL/RPG6/SCK2/RG6_10") (pintype "bidirectional"))
      (node (ref "IC25") (pin "16") (pinfunction "PC6/MISO/RXD1_16") (pintype "bidirectional"))
    )
    (net (code "199") (name "UC_IO3") (class "Default")
      (node (ref "IC16") (pin "24") (pinfunction "PGEC1/AN1/RPB1/RB1_24") (pintype "bidirectional"))
      (node (ref "IC25") (pin "17") (pinfunction "PC7/SCK/TXD1/CLKO/EVO_17") (pintype "bidirectional"))
      (node (ref "IC33") (pin "1") (pinfunction "OE_1") (pintype "bidirectional"))
      (node (ref "IC34") (pin "1") (pinfunction "OE_1") (pintype "bidirectional"))
      (node (ref "IC35") (pin "1") (pinfunction "~{OE}_1") (pintype "bidirectional"))
      (node (ref "R89") (pin "1") (pinfunction "1_1") (pintype "passive"))
    )
    (net (code "200") (name "UC_IO4") (class "Default")
      (node (ref "IC16") (pin "23") (pinfunction "AN2/C2INB/RPB2/RB2_23") (pintype "bidirectional"))
      (node (ref "IC25") (pin "25") (pinfunction "~XCK1MOSIPD5_25") (pintype "bidirectional"))
    )
    (net (code "201") (name "USB") (class "Default")
      (node (ref "IC16") (pin "85") (pinfunction "EBID11/ETXD1/RPF0/PMD11/RF0_85") (pintype "bidirectional"))
      (node (ref "R77") (pin "2") (pinfunction "2_2") (pintype "passive"))
    )
    (net (code "202") (name "USB5V") (class "Default")
      (node (ref "C111") (pin "1") (pinfunction "1_1") (pintype "passive"))
      (node (ref "C112") (pin "+") (pinfunction "+_+") (pintype "passive"))
      (node (ref "C114") (pin "1") (pinfunction "1_1") (pintype "passive"))
      (node (ref "C117") (pin "1") (pinfunction "1_1") (pintype "passive"))
      (node (ref "IC19") (pin "20") (pinfunction "VCC_20") (pintype "power_in"))
      (node (ref "IC19") (pin "4") (pinfunction "VCCIO_4") (pintype "power_in"))
      (node (ref "IC21") (pin "1") (pinfunction "VDD1_1") (pintype "bidirectional"))
      (node (ref "IC21") (pin "7") (pinfunction "NC/EN_7") (pintype "bidirectional"))
      (node (ref "L10") (pin "1") (pinfunction "1_1") (pintype "passive"))
      (node (ref "R58") (pin "2") (pinfunction "2_2") (pintype "passive"))
      (node (ref "R59") (pin "2") (pinfunction "2_2") (pintype "passive"))
    )
    (net (code "203") (name "USBDM") (class "Default")
      (node (ref "C108") (pin "1") (pinfunction "1_1") (pintype "passive"))
      (node (ref "IC17") (pin "P$6") (pinfunction "IO1_P$6") (pintype "bidirectional"))
      (node (ref "IC19") (pin "16") (pinfunction "USBDM_16") (pintype "bidirectional"))
    )
    (net (code "204") (name "USBDP") (class "Default")
      (node (ref "C107") (pin "1") (pinfunction "1_1") (pintype "passive"))
      (node (ref "IC17") (pin "P$4") (pinfunction "IO2_P$4") (pintype "bidirectional"))
      (node (ref "IC19") (pin "15") (pinfunction "USBDP_15") (pintype "bidirectional"))
    )
    (net (code "205") (name "V+") (class "Default")
      (node (ref "C11") (pin "1") (pinfunction "1_1") (pintype "passive"))
      (node (ref "C2") (pin "+") (pinfunction "+_+") (pintype "passive"))
      (node (ref "IC2") (pin "17") (pinfunction "PVIN1_17") (pintype "bidirectional"))
      (node (ref "IC2") (pin "18") (pinfunction "PVINSYS_18") (pintype "bidirectional"))
      (node (ref "IC2") (pin "19") (pinfunction "PVIN2_19") (pintype "bidirectional"))
      (node (ref "JACK") (pin "P1") (pinfunction "1_P1") (pintype "passive"))
      (node (ref "L11") (pin "1") (pinfunction "1_1") (pintype "passive"))
      (node (ref "L5") (pin "1") (pinfunction "1_1") (pintype "passive"))
      (node (ref "L6") (pin "1") (pinfunction "1_1") (pintype "passive"))
      (node (ref "L9") (pin "1") (pinfunction "1_1") (pintype "passive"))
    )
    (net (code "206") (name "VBUS") (class "Default")
      (node (ref "IC16") (pin "51") (pinfunction "VBUS_51") (pintype "bidirectional"))
      (node (ref "L13") (pin "1") (pinfunction "1_1") (pintype "passive"))
    )
    (net (code "207") (name "VCC") (class "Default")
      (node (ref "C100") (pin "1") (pinfunction "1_1") (pintype "passive"))
      (node (ref "C102") (pin "1") (pinfunction "1_1") (pintype "passive"))
      (node (ref "C139") (pin "1") (pinfunction "1_1") (pintype "passive"))
      (node (ref "C84") (pin "1") (pinfunction "1_1") (pintype "passive"))
      (node (ref "C86") (pin "1") (pinfunction "1_1") (pintype "passive"))
      (node (ref "C88") (pin "1") (pinfunction "1_1") (pintype "passive"))
      (node (ref "C89") (pin "1") (pinfunction "1_1") (pintype "passive"))
      (node (ref "C92") (pin "1") (pinfunction "1_1") (pintype "passive"))
      (node (ref "C93") (pin "1") (pinfunction "1_1") (pintype "passive"))
      (node (ref "C94") (pin "1") (pinfunction "1_1") (pintype "passive"))
      (node (ref "C95") (pin "1") (pinfunction "1_1") (pintype "passive"))
      (node (ref "C96") (pin "1") (pinfunction "1_1") (pintype "passive"))
      (node (ref "C97") (pin "1") (pinfunction "1_1") (pintype "passive"))
      (node (ref "C98") (pin "1") (pinfunction "1_1") (pintype "passive"))
      (node (ref "C99") (pin "1") (pinfunction "1_1") (pintype "passive"))
      (node (ref "IC13") (pin "P12") (pinfunction "VCC_P12") (pintype "bidirectional"))
      (node (ref "IC13") (pin "P37") (pinfunction "VCC_P37") (pintype "bidirectional"))
      (node (ref "IC13") (pin "P39") (pinfunction "VCC_P39") (pintype "bidirectional"))
      (node (ref "IC16") (pin "14") (pinfunction "VDD_14") (pintype "bidirectional"))
      (node (ref "IC16") (pin "30") (pinfunction "AVDD_30") (pintype "bidirectional"))
      (node (ref "IC16") (pin "37") (pinfunction "VDD_37") (pintype "bidirectional"))
      (node (ref "IC16") (pin "46") (pinfunction "VDD_46") (pintype "bidirectional"))
      (node (ref "IC16") (pin "52") (pinfunction "VUSB3V3_52") (pintype "bidirectional"))
      (node (ref "IC16") (pin "62") (pinfunction "VDD_62") (pintype "bidirectional"))
      (node (ref "IC16") (pin "74") (pinfunction "VDD_74") (pintype "bidirectional"))
      (node (ref "IC16") (pin "83") (pinfunction "VDD_83") (pintype "bidirectional"))
      (node (ref "IC16") (pin "93") (pinfunction "VDD_93") (pintype "bidirectional"))
      (node (ref "IC18") (pin "5") (pinfunction "OUT_5") (pintype "bidirectional"))
      (node (ref "JP1") (pin "2") (pinfunction "2_2") (pintype "passive"))
      (node (ref "OSC1") (pin "P$4") (pinfunction "VDD_P$4") (pintype "passive"))
      (node (ref "OSC3") (pin "P$1") (pinfunction "EOH_P$1") (pintype "bidirectional"))
      (node (ref "OSC3") (pin "P$4") (pinfunction "VCC_P$4") (pintype "bidirectional"))
      (node (ref "R56") (pin "2") (pinfunction "2_2") (pintype "passive"))
      (node (ref "R80") (pin "2") (pinfunction "2_2") (pintype "passive"))
    )
    (net (code "208") (name "VCCINT") (class "Default")
      (node (ref "C120") (pin "1") (pinfunction "1_1") (pintype "passive"))
      (node (ref "C133") (pin "1") (pinfunction "1_1") (pintype "passive"))
      (node (ref "C134") (pin "1") (pinfunction "1_1") (pintype "passive"))
      (node (ref "IC23") (pin "5") (pinfunction "P$5_5") (pintype "bidirectional"))
      (node (ref "IC28") (pin "5") (pinfunction "P$5_5") (pintype "bidirectional"))
      (node (ref "IC29") (pin "5") (pinfunction "P$5_5") (pintype "bidirectional"))
      (node (ref "JP2") (pin "2") (pinfunction "2_2") (pintype "passive"))
    )
    (net (code "209") (name "VCCIO") (class "Default")
      (node (ref "C104") (pin "1") (pinfunction "1_1") (pintype "passive"))
      (node (ref "C105") (pin "1") (pinfunction "1_1") (pintype "passive"))
      (node (ref "C116") (pin "1") (pinfunction "1_1") (pintype "passive"))
      (node (ref "C118") (pin "1") (pinfunction "1_1") (pintype "passive"))
      (node (ref "C119") (pin "1") (pinfunction "1_1") (pintype "passive"))
      (node (ref "C121") (pin "1") (pinfunction "1_1") (pintype "passive"))
      (node (ref "C123") (pin "1") (pinfunction "1_1") (pintype "passive"))
      (node (ref "C124") (pin "1") (pinfunction "1_1") (pintype "passive"))
      (node (ref "C125") (pin "1") (pinfunction "1_1") (pintype "passive"))
      (node (ref "C126") (pin "1") (pinfunction "1_1") (pintype "passive"))
      (node (ref "C127") (pin "1") (pinfunction "1_1") (pintype "passive"))
      (node (ref "C128") (pin "1") (pinfunction "1_1") (pintype "passive"))
      (node (ref "C130") (pin "1") (pinfunction "1_1") (pintype "passive"))
      (node (ref "C132") (pin "1") (pinfunction "1_1") (pintype "passive"))
      (node (ref "C135") (pin "1") (pinfunction "1_1") (pintype "passive"))
      (node (ref "C136") (pin "1") (pinfunction "1_1") (pintype "passive"))
      (node (ref "C143") (pin "1") (pinfunction "1_1") (pintype "passive"))
      (node (ref "C146") (pin "1") (pinfunction "1_1") (pintype "passive"))
      (node (ref "C147") (pin "1") (pinfunction "1_1") (pintype "passive"))
      (node (ref "CLKIN") (pin "1") (pinfunction "1_1") (pintype "passive"))
      (node (ref "IC20") (pin "5") (pinfunction "OUT_5") (pintype "bidirectional"))
      (node (ref "IC21") (pin "10") (pinfunction "NC/EN_10") (pintype "bidirectional"))
      (node (ref "IC21") (pin "16") (pinfunction "VDD2_16") (pintype "bidirectional"))
      (node (ref "IC22") (pin "5") (pinfunction "P$5_5") (pintype "bidirectional"))
      (node (ref "IC24") (pin "5") (pinfunction "P$5_5") (pintype "bidirectional"))
      (node (ref "IC25") (pin "19") (pinfunction "VCC_19") (pintype "power_in"))
      (node (ref "IC25") (pin "31") (pinfunction "VCC_31") (pintype "power_in"))
      (node (ref "IC25") (pin "9") (pinfunction "VCC_9") (pintype "power_in"))
      (node (ref "IC26") (pin "1") (pinfunction "VDD1_1") (pintype "bidirectional"))
      (node (ref "IC26") (pin "7") (pinfunction "NC/EN_7") (pintype "bidirectional"))
      (node (ref "IC27") (pin "1") (pinfunction "VCC_1") (pintype "bidirectional"))
      (node (ref "IC30") (pin "5") (pinfunction "P$5_5") (pintype "bidirectional"))
      (node (ref "IC31") (pin "5") (pinfunction "P$5_5") (pintype "bidirectional"))
      (node (ref "IC33") (pin "5") (pinfunction "VCC_5") (pintype "bidirectional"))
      (node (ref "IC34") (pin "5") (pinfunction "VCC_5") (pintype "bidirectional"))
      (node (ref "IC35") (pin "5") (pinfunction "VCC_5") (pintype "bidirectional"))
      (node (ref "IC37") (pin "5") (pinfunction "V+_5") (pintype "power_in"))
      (node (ref "IC38") (pin "5") (pinfunction "V+_5") (pintype "power_in"))
      (node (ref "JP2") (pin "3") (pinfunction "3_3") (pintype "passive"))
      (node (ref "L12") (pin "2") (pinfunction "2_2") (pintype "passive"))
      (node (ref "OSC2") (pin "P$4") (pinfunction "VDD_P$4") (pintype "passive"))
      (node (ref "PDI") (pin "2") (pinfunction "2_2") (pintype "passive"))
      (node (ref "R9") (pin "2") (pinfunction "2_2") (pintype "passive"))
    )
    (net (code "210") (name "VDD") (class "Default")
      (node (ref "C129") (pin "1") (pinfunction "1_1") (pintype "passive"))
      (node (ref "IC26") (pin "10") (pinfunction "NC/EN_10") (pintype "bidirectional"))
      (node (ref "IC26") (pin "11") (pinfunction "B4_11") (pintype "bidirectional"))
      (node (ref "IC26") (pin "16") (pinfunction "VDD2_16") (pintype "bidirectional"))
      (node (ref "J1") (pin "4") (pinfunction "4_4") (pintype "passive"))
    )
    (net (code "211") (name "VREF") (class "Default")
      (node (ref "C34") (pin "1") (pinfunction "1_1") (pintype "passive"))
      (node (ref "C35") (pin "+") (pinfunction "+_+") (pintype "passive"))
      (node (ref "R21") (pin "1") (pinfunction "1_1") (pintype "passive"))
      (node (ref "R22") (pin "2") (pinfunction "2_2") (pintype "passive"))
      (node (ref "R24") (pin "2") (pinfunction "2_2") (pintype "passive"))
      (node (ref "R25") (pin "2") (pinfunction "2_2") (pintype "passive"))
      (node (ref "R40") (pin "2") (pinfunction "2_2") (pintype "passive"))
      (node (ref "R41") (pin "2") (pinfunction "2_2") (pintype "passive"))
    )
    (net (code "212") (name "WE") (class "Default")
      (node (ref "IC13") (pin "P18") (pinfunction "WE#_P18") (pintype "bidirectional"))
      (node (ref "IC16") (pin "8") (pinfunction "~{EBIWE}/AN20/RPC3/PMWR/RC3_8") (pintype "bidirectional"))
    )
    (net (code "213") (name "WP") (class "Default")
      (node (ref "IC13") (pin "P19") (pinfunction "WP#_P19") (pintype "bidirectional"))
      (node (ref "IC16") (pin "12") (pinfunction "EBIA3/AN12/C2IND/ERXDV/ECRSDV..._12") (pintype "bidirectional"))
    )
    (net (code "214") (name "ZEROL") (class "Default")
      (node (ref "IC16") (pin "56") (pinfunction "RPF3/USBID/RF3_56") (pintype "bidirectional"))
      (node (ref "IC6") (pin "P21") (pinfunction "ZEROL_P21") (pintype "bidirectional"))
    )
    (net (code "215") (name "ZEROR") (class "Default")
      (node (ref "IC16") (pin "58") (pinfunction "EBIRDY2/RPF8/SCL3/RF8_58") (pintype "bidirectional"))
      (node (ref "IC6") (pin "P20") (pinfunction "ZEROR_P20") (pintype "bidirectional"))
    )
    (net (code "216") (name "unconnected-(IC2-SEQ-Pad5)") (class "Default")
      (node (ref "IC2") (pin "5") (pinfunction "SEQ_5") (pintype "bidirectional"))
    )
    (net (code "217") (name "unconnected-(IC2-SS-Pad10)") (class "Default")
      (node (ref "IC2") (pin "10") (pinfunction "SS_10") (pintype "bidirectional"))
    )
    (net (code "218") (name "unconnected-(IC4-~{ERR}-Pad6)") (class "Default")
      (node (ref "IC4") (pin "6") (pinfunction "~{ERR}_6") (pintype "bidirectional"))
    )
    (net (code "219") (name "unconnected-(IC5-~{ERR}-Pad6)") (class "Default")
      (node (ref "IC5") (pin "6") (pinfunction "~{ERR}_6") (pintype "bidirectional"))
    )
    (net (code "220") (name "unconnected-(IC6-DSD_LDATA-PadP7)") (class "Default")
      (node (ref "IC6") (pin "P7") (pinfunction "DSD_LDATA_P7") (pintype "bidirectional"))
    )
    (net (code "221") (name "unconnected-(IC6-DSD_RDATA-PadP8)") (class "Default")
      (node (ref "IC6") (pin "P8") (pinfunction "DSD_RDATA_P8") (pintype "bidirectional"))
    )
    (net (code "222") (name "unconnected-(IC6-DSD_SCLK-PadP6)") (class "Default")
      (node (ref "IC6") (pin "P6") (pinfunction "DSD_SCLK_P6") (pintype "bidirectional"))
    )
    (net (code "223") (name "unconnected-(IC6-EF_RDATA-PadP5)") (class "Default")
      (node (ref "IC6") (pin "P5") (pinfunction "EF_RDATA_P5") (pintype "bidirectional"))
    )
    (net (code "224") (name "unconnected-(IC7-COMP-Pad8)") (class "Default")
      (node (ref "IC7") (pin "8") (pinfunction "COMP_8") (pintype "bidirectional"))
    )
    (net (code "225") (name "unconnected-(IC7-NL+-Pad1)") (class "Default")
      (node (ref "IC7") (pin "1") (pinfunction "NL+_1") (pintype "bidirectional"))
    )
    (net (code "226") (name "unconnected-(IC7-NL--Pad5)") (class "Default")
      (node (ref "IC7") (pin "5") (pinfunction "NL-_5") (pintype "bidirectional"))
    )
    (net (code "227") (name "unconnected-(IC8-COMP-Pad8)") (class "Default")
      (node (ref "IC8") (pin "8") (pinfunction "COMP_8") (pintype "bidirectional"))
    )
    (net (code "228") (name "unconnected-(IC8-NL+-Pad1)") (class "Default")
      (node (ref "IC8") (pin "1") (pinfunction "NL+_1") (pintype "bidirectional"))
    )
    (net (code "229") (name "unconnected-(IC8-NL--Pad5)") (class "Default")
      (node (ref "IC8") (pin "5") (pinfunction "NL-_5") (pintype "bidirectional"))
    )
    (net (code "230") (name "unconnected-(IC9-COMP-Pad8)") (class "Default")
      (node (ref "IC9") (pin "8") (pinfunction "COMP_8") (pintype "bidirectional"))
    )
    (net (code "231") (name "unconnected-(IC9-NL+-Pad1)") (class "Default")
      (node (ref "IC9") (pin "1") (pinfunction "NL+_1") (pintype "bidirectional"))
    )
    (net (code "232") (name "unconnected-(IC9-NL--Pad5)") (class "Default")
      (node (ref "IC9") (pin "5") (pinfunction "NL-_5") (pintype "bidirectional"))
    )
    (net (code "233") (name "unconnected-(IC10-COMP-Pad8)") (class "Default")
      (node (ref "IC10") (pin "8") (pinfunction "COMP_8") (pintype "bidirectional"))
    )
    (net (code "234") (name "unconnected-(IC10-NL+-Pad1)") (class "Default")
      (node (ref "IC10") (pin "1") (pinfunction "NL+_1") (pintype "bidirectional"))
    )
    (net (code "235") (name "unconnected-(IC10-NL--Pad5)") (class "Default")
      (node (ref "IC10") (pin "5") (pinfunction "NL-_5") (pintype "bidirectional"))
    )
    (net (code "236") (name "unconnected-(IC11-COMP-Pad8)") (class "Default")
      (node (ref "IC11") (pin "8") (pinfunction "COMP_8") (pintype "bidirectional"))
    )
    (net (code "237") (name "unconnected-(IC11-NL+-Pad1)") (class "Default")
      (node (ref "IC11") (pin "1") (pinfunction "NL+_1") (pintype "bidirectional"))
    )
    (net (code "238") (name "unconnected-(IC11-NL--Pad5)") (class "Default")
      (node (ref "IC11") (pin "5") (pinfunction "NL-_5") (pintype "bidirectional"))
    )
    (net (code "239") (name "unconnected-(IC12-COMP-Pad8)") (class "Default")
      (node (ref "IC12") (pin "8") (pinfunction "COMP_8") (pintype "bidirectional"))
    )
    (net (code "240") (name "unconnected-(IC12-NL+-Pad1)") (class "Default")
      (node (ref "IC12") (pin "1") (pinfunction "NL+_1") (pintype "bidirectional"))
    )
    (net (code "241") (name "unconnected-(IC12-NL--Pad5)") (class "Default")
      (node (ref "IC12") (pin "5") (pinfunction "NL-_5") (pintype "bidirectional"))
    )
    (net (code "242") (name "unconnected-(IC13-NC-PadP1)") (class "Default")
      (node (ref "IC13") (pin "P1") (pinfunction "NC_P1") (pintype "bidirectional"))
    )
    (net (code "243") (name "unconnected-(IC13-NC-PadP2)") (class "Default")
      (node (ref "IC13") (pin "P2") (pinfunction "NC_P2") (pintype "bidirectional"))
    )
    (net (code "244") (name "unconnected-(IC13-NC-PadP3)") (class "Default")
      (node (ref "IC13") (pin "P3") (pinfunction "NC_P3") (pintype "bidirectional"))
    )
    (net (code "245") (name "unconnected-(IC13-NC-PadP4)") (class "Default")
      (node (ref "IC13") (pin "P4") (pinfunction "NC_P4") (pintype "bidirectional"))
    )
    (net (code "246") (name "unconnected-(IC13-NC-PadP5)") (class "Default")
      (node (ref "IC13") (pin "P5") (pinfunction "NC_P5") (pintype "bidirectional"))
    )
    (net (code "247") (name "unconnected-(IC13-NC-PadP6)") (class "Default")
      (node (ref "IC13") (pin "P6") (pinfunction "NC_P6") (pintype "bidirectional"))
    )
    (net (code "248") (name "unconnected-(IC13-NC-PadP10)") (class "Default")
      (node (ref "IC13") (pin "P10") (pinfunction "NC_P10") (pintype "bidirectional"))
    )
    (net (code "249") (name "unconnected-(IC13-NC-PadP11)") (class "Default")
      (node (ref "IC13") (pin "P11") (pinfunction "NC_P11") (pintype "bidirectional"))
    )
    (net (code "250") (name "unconnected-(IC13-NC-PadP14)") (class "Default")
      (node (ref "IC13") (pin "P14") (pinfunction "NC_P14") (pintype "bidirectional"))
    )
    (net (code "251") (name "unconnected-(IC13-NC-PadP15)") (class "Default")
      (node (ref "IC13") (pin "P15") (pinfunction "NC_P15") (pintype "bidirectional"))
    )
    (net (code "252") (name "unconnected-(IC13-NC-PadP20)") (class "Default")
      (node (ref "IC13") (pin "P20") (pinfunction "NC_P20") (pintype "bidirectional"))
    )
    (net (code "253") (name "unconnected-(IC13-NC-PadP21)") (class "Default")
      (node (ref "IC13") (pin "P21") (pinfunction "NC_P21") (pintype "bidirectional"))
    )
    (net (code "254") (name "unconnected-(IC13-NC-PadP22)") (class "Default")
      (node (ref "IC13") (pin "P22") (pinfunction "NC_P22") (pintype "bidirectional"))
    )
    (net (code "255") (name "unconnected-(IC13-NC-PadP23)") (class "Default")
      (node (ref "IC13") (pin "P23") (pinfunction "NC_P23") (pintype "bidirectional"))
    )
    (net (code "256") (name "unconnected-(IC13-NC-PadP24)") (class "Default")
      (node (ref "IC13") (pin "P24") (pinfunction "NC_P24") (pintype "bidirectional"))
    )
    (net (code "257") (name "unconnected-(IC13-NC-PadP35)") (class "Default")
      (node (ref "IC13") (pin "P35") (pinfunction "NC_P35") (pintype "bidirectional"))
    )
    (net (code "258") (name "unconnected-(IC13-NC-PadP38)") (class "Default")
      (node (ref "IC13") (pin "P38") (pinfunction "NC_P38") (pintype "bidirectional"))
    )
    (net (code "259") (name "unconnected-(IC13-VCC-PadP34)") (class "Default")
      (node (ref "IC13") (pin "P34") (pinfunction "VCC_P34") (pintype "bidirectional"))
    )
    (net (code "260") (name "unconnected-(IC16-AETXCLK{slash}RPA14{slash}SCL1{slash}RA14-Pad66)") (class "Default")
      (node (ref "IC16") (pin "66") (pinfunction "AETXCLK/RPA14/SCL1/RA14_66") (pintype "bidirectional"))
    )
    (net (code "261") (name "unconnected-(IC16-AETXEN{slash}RPA15{slash}SDA1{slash}RA15-Pad67)") (class "Default")
      (node (ref "IC16") (pin "67") (pinfunction "AETXEN/RPA15/SDA1/RA15_67") (pintype "bidirectional"))
    )
    (net (code "262") (name "unconnected-(IC16-AN6{slash}ERXERR{slash}AETXERR{slash}RB11-Pad35)") (class "Default")
      (node (ref "IC16") (pin "35") (pinfunction "AN6/ERXERR/AETXERR/RB11_35") (pintype "input"))
    )
    (net (code "263") (name "unconnected-(IC16-AN23{slash}AERXERR{slash}RG15-Pad1)") (class "Default")
      (node (ref "IC16") (pin "1") (pinfunction "AN23/AERXERR/RG15_1") (pintype "bidirectional"))
    )
    (net (code "264") (name "unconnected-(IC16-AN25{slash}AERXD0{slash}RPE8{slash}RE8-Pad18)") (class "Default")
      (node (ref "IC16") (pin "18") (pinfunction "AN25/AERXD0/RPE8/RE8_18") (pintype "bidirectional"))
    )
    (net (code "265") (name "unconnected-(IC16-AN26{slash}AERXD1{slash}RPE9{slash}RE9-Pad19)") (class "Default")
      (node (ref "IC16") (pin "19") (pinfunction "AN26/AERXD1/RPE9/RE9_19") (pintype "bidirectional"))
    )
    (net (code "266") (name "unconnected-(IC16-AN32{slash}AETXD0{slash}RPD14{slash}RD14-Pad47)") (class "Default")
      (node (ref "IC16") (pin "47") (pinfunction "AN32/AETXD0/RPD14/RD14_47") (pintype "bidirectional"))
    )
    (net (code "267") (name "unconnected-(IC16-AN33{slash}AETXD1{slash}RPD15{slash}SCK6{slash}RD15-Pad48)") (class "Default")
      (node (ref "IC16") (pin "48") (pinfunction "AN33/AETXD1/RPD15/SCK6/RD15_48") (pintype "bidirectional"))
    )
    (net (code "268") (name "unconnected-(IC16-EBIA0{slash}AN10{slash}ERXD3{slash}AETXD2{slash}RPB15{slash}OCFB{slash}PMA0{slash}RB15-Pad44)") (class "Default")
      (node (ref "IC16") (pin "44") (pinfunction "EBIA0/AN10/ERXD3/AETXD2/RPB15/OCFB/PMA0/RB15_44") (pintype "bidirectional"))
    )
    (net (code "269") (name "unconnected-(IC16-EBIA1{slash}AN9{slash}ERXD2{slash}AETXD3{slash}RPB14{slash}SCK3{slash}PMA1{slash}RB14-Pad43)") (class "Default")
      (node (ref "IC16") (pin "43") (pinfunction "EBIA1/AN9/ERXD2/AETXD3/RPB14/SCK3/PMA1/RB14_43") (pintype "bidirectional"))
    )
    (net (code "270") (name "unconnected-(IC16-EBIA6{slash}AN22{slash}RPC1{slash}PMA6{slash}RC1-Pad6)") (class "Default")
      (node (ref "IC16") (pin "6") (pinfunction "EBIA6/AN22/RPC1/PMA6/RC1_6") (pintype "bidirectional"))
    )
    (net (code "271") (name "unconnected-(IC16-EBIA9{slash}RPF4{slash}SDA5{slash}PMA9{slash}RF4-Pad64)") (class "Default")
      (node (ref "IC16") (pin "64") (pinfunction "EBIA9/RPF4/SDA5/PMA9/RF4_64") (pintype "bidirectional"))
    )
    (net (code "272") (name "unconnected-(IC16-EBID8{slash}RPG0{slash}PMD8{slash}RG0-Pad88)") (class "Default")
      (node (ref "IC16") (pin "88") (pinfunction "EBID8/RPG0/PMD8/RG0_88") (pintype "input"))
    )
    (net (code "273") (name "unconnected-(IC16-EBID9{slash}ETXERR{slash}RPG1{slash}PMD9{slash}RG1-Pad87)") (class "Default")
      (node (ref "IC16") (pin "87") (pinfunction "EBID9/ETXERR/RPG1/PMD9/RG1_87") (pintype "bidirectional"))
    )
    (net (code "274") (name "unconnected-(IC16-EBID15{slash}ETXCLK{slash}RPD3...-Pad78)") (class "Default")
      (node (ref "IC16") (pin "78") (pinfunction "EBID15/ETXCLK/RPD3..._78") (pintype "bidirectional"))
    )
    (net (code "275") (name "unconnected-(IC16-OSC2{slash}CLKO{slash}RC15-Pad50)") (class "Default")
      (node (ref "IC16") (pin "50") (pinfunction "OSC2/CLKO/RC15_50") (pintype "bidirectional"))
    )
    (net (code "276") (name "unconnected-(IC16-TDI{slash}EBIA18{slash}AN30{slash}RPF13{slash}SCK5{slash}RF13-Pad39)") (class "Default")
      (node (ref "IC16") (pin "39") (pinfunction "TDI/EBIA18/AN30/RPF13/SCK5/RF13_39") (pintype "bidirectional"))
    )
    (net (code "277") (name "unconnected-(IC16-TDO{slash}EBIA17{slash}AN31{slash}RPF12{slash}RF12-Pad40)") (class "Default")
      (node (ref "IC16") (pin "40") (pinfunction "TDO/EBIA17/AN31/RPF12/RF12_40") (pintype "bidirectional"))
    )
    (net (code "278") (name "unconnected-(IC16-VREF+{slash}CVREF+{slash}AN28{slash}AERXD3{slash}RA10-Pad29)") (class "Default")
      (node (ref "IC16") (pin "29") (pinfunction "VREF+/CVREF+/AN28/AERXD3/RA10_29") (pintype "bidirectional"))
    )
    (net (code "279") (name "unconnected-(IC16-VREF-{slash}CVREF-{slash}AN27{slash}AERXD2{slash}RA9-Pad28)") (class "Default")
      (node (ref "IC16") (pin "28") (pinfunction "VREF-/CVREF-/AN27/AERXD2/RA9_28") (pintype "bidirectional"))
    )
    (net (code "280") (name "unconnected-(IC16-~{SQICS0}{slash}RPD4{slash}RD4-Pad81)") (class "Default")
      (node (ref "IC16") (pin "81") (pinfunction "~{SQICS0}/RPD4/RD4_81") (pintype "bidirectional"))
    )
    (net (code "281") (name "unconnected-(IC16-~{SQICS1}{slash}RPD5{slash}RD5-Pad82)") (class "Default")
      (node (ref "IC16") (pin "82") (pinfunction "~{SQICS1}/RPD5/RD5_82") (pintype "bidirectional"))
    )
    (net (code "282") (name "unconnected-(IC18-N{slash}C-Pad4)") (class "Default")
      (node (ref "IC18") (pin "4") (pinfunction "N/C_4") (pintype "bidirectional"))
    )
    (net (code "283") (name "unconnected-(IC19-CBUS2-Pad13)") (class "Default")
      (node (ref "IC19") (pin "13") (pinfunction "CBUS2_13") (pintype "bidirectional"))
    )
    (net (code "284") (name "unconnected-(IC19-CBUS3-Pad14)") (class "Default")
      (node (ref "IC19") (pin "14") (pinfunction "CBUS3_14") (pintype "bidirectional"))
    )
    (net (code "285") (name "unconnected-(IC19-CBUS4-Pad12)") (class "Default")
      (node (ref "IC19") (pin "12") (pinfunction "CBUS4_12") (pintype "bidirectional"))
    )
    (net (code "286") (name "unconnected-(IC19-OSCI-Pad27)") (class "Default")
      (node (ref "IC19") (pin "27") (pinfunction "OSCI_27") (pintype "input"))
    )
    (net (code "287") (name "unconnected-(IC19-OSCO-Pad28)") (class "Default")
      (node (ref "IC19") (pin "28") (pinfunction "OSCO_28") (pintype "output"))
    )
    (net (code "288") (name "unconnected-(IC19-~{DCD}-Pad10)") (class "Default")
      (node (ref "IC19") (pin "10") (pinfunction "~{DCD}_10") (pintype "input"))
    )
    (net (code "289") (name "unconnected-(IC19-~{DSR}-Pad9)") (class "Default")
      (node (ref "IC19") (pin "9") (pinfunction "~{DSR}_9") (pintype "input"))
    )
    (net (code "290") (name "unconnected-(IC19-~{DTR}-Pad2)") (class "Default")
      (node (ref "IC19") (pin "2") (pinfunction "~{DTR}_2") (pintype "output"))
    )
    (net (code "291") (name "unconnected-(IC19-~{RESET}-Pad19)") (class "Default")
      (node (ref "IC19") (pin "19") (pinfunction "~{RESET}_19") (pintype "input"))
    )
    (net (code "292") (name "unconnected-(IC19-~{RI}-Pad6)") (class "Default")
      (node (ref "IC19") (pin "6") (pinfunction "~{RI}_6") (pintype "input"))
    )
    (net (code "293") (name "unconnected-(IC20-N{slash}C-Pad4)") (class "Default")
      (node (ref "IC20") (pin "4") (pinfunction "N/C_4") (pintype "bidirectional"))
    )
    (net (code "294") (name "unconnected-(IC26-B1-Pad14)") (class "Default")
      (node (ref "IC26") (pin "14") (pinfunction "B1_14") (pintype "bidirectional"))
    )
    (net (code "295") (name "unconnected-(J1-Pad2)") (class "Default")
      (node (ref "J1") (pin "2") (pinfunction "2_2") (pintype "passive"))
    )
    (net (code "296") (name "unconnected-(J1-Pad6)") (class "Default")
      (node (ref "J1") (pin "6") (pinfunction "6_6") (pintype "passive"))
    )
    (net (code "297") (name "unconnected-(J1-Pad7)") (class "Default")
      (node (ref "J1") (pin "7") (pinfunction "7_7") (pintype "passive"))
    )
    (net (code "298") (name "unconnected-(J1-Pad8)") (class "Default")
      (node (ref "J1") (pin "8") (pinfunction "8_8") (pintype "passive"))
    )
    (net (code "299") (name "unconnected-(J2-Pad5)") (class "Default")
      (node (ref "J2") (pin "5") (pinfunction "5_5") (pintype "passive"))
    )
    (net (code "300") (name "unconnected-(J2-Pad6)") (class "Default")
      (node (ref "J2") (pin "6") (pinfunction "6_6") (pintype "passive"))
    )
    (net (code "301") (name "unconnected-(J2-Pad7)") (class "Default")
      (node (ref "J2") (pin "7") (pinfunction "7_7") (pintype "passive"))
    )
    (net (code "302") (name "unconnected-(J2-Pad8)") (class "Default")
      (node (ref "J2") (pin "8") (pinfunction "8_8") (pintype "passive"))
    )
    (net (code "303") (name "unconnected-(J3-3-PadP3)") (class "Default")
      (node (ref "J3") (pin "P3") (pinfunction "3_P3") (pintype "passive"))
    )
    (net (code "304") (name "unconnected-(J4-3-PadP3)") (class "Default")
      (node (ref "J4") (pin "P3") (pinfunction "3_P3") (pintype "passive"))
    )
    (net (code "305") (name "unconnected-(JP1-Pad6)") (class "Default")
      (node (ref "JP1") (pin "6") (pinfunction "6_6") (pintype "passive"))
    )
    (net (code "306") (name "unconnected-(OSC1-STANDBY#-PadP$1)") (class "Default")
      (node (ref "OSC1") (pin "P$1") (pinfunction "STANDBY#_P$1") (pintype "passive"))
    )
    (net (code "307") (name "unconnected-(OSC2-STANDBY#-PadP$1)") (class "Default")
      (node (ref "OSC2") (pin "P$1") (pinfunction "STANDBY#_P$1") (pintype "passive"))
    )
    (net (code "308") (name "unconnected-(PDI-Pad3)") (class "Default")
      (node (ref "PDI") (pin "3") (pinfunction "3_3") (pintype "passive"))
    )
    (net (code "309") (name "unconnected-(PDI-Pad4)") (class "Default")
      (node (ref "PDI") (pin "4") (pinfunction "4_4") (pintype "passive"))
    )
    (net (code "310") (name "unconnected-(USB1-4-PadP$4)") (class "Default")
      (node (ref "USB1") (pin "P$4") (pinfunction "4_P$4") (pintype "bidirectional"))
    )
    (net (code "311") (name "unconnected-(USB1-P$2-PadSHIELD_1)") (class "Default")
      (node (ref "USB1") (pin "SHIELD_1") (pinfunction "P$2_SHIELD_1") (pintype "bidirectional"))
    )
    (net (code "312") (name "unconnected-(USB1-P$3-PadSHIELD_2)") (class "Default")
      (node (ref "USB1") (pin "SHIELD_2") (pinfunction "P$3_SHIELD_2") (pintype "bidirectional"))
    )
    (net (code "313") (name "unconnected-(USB1-P$5-PadP$6)") (class "Default")
      (node (ref "USB1") (pin "P$6") (pinfunction "P$5_P$6") (pintype "bidirectional"))
    )
    (net (code "314") (name "unconnected-(USB1-P$6-PadP$7)") (class "Default")
      (node (ref "USB1") (pin "P$7") (pinfunction "P$6_P$7") (pintype "bidirectional"))
    )
    (net (code "315") (name "unconnected-(USB2-4-PadP$4)") (class "Default")
      (node (ref "USB2") (pin "P$4") (pinfunction "4_P$4") (pintype "bidirectional"))
    )
    (net (code "316") (name "unconnected-(USB2-P$2-PadSHIELD_2)") (class "Default")
      (node (ref "USB2") (pin "SHIELD_2") (pinfunction "P$2_SHIELD_2") (pintype "bidirectional"))
    )
    (net (code "317") (name "unconnected-(USB2-P$3-PadSHIELD_3)") (class "Default")
      (node (ref "USB2") (pin "SHIELD_3") (pinfunction "P$3_SHIELD_3") (pintype "bidirectional"))
    )
    (net (code "318") (name "~{MCLR}") (class "Default")
      (node (ref "IC16") (pin "15") (pinfunction "~{MCLR}_15") (pintype "bidirectional"))
      (node (ref "JP1") (pin "1") (pinfunction "1_1") (pintype "passive"))
      (node (ref "R57") (pin "1") (pinfunction "1_1") (pintype "passive"))
      (node (ref "SW1") (pin "O") (pinfunction "O_O") (pintype "passive"))
    )
    (net (code "319") (name "~{SS1}") (class "Default")
      (node (ref "IC16") (pin "32") (pinfunction "EBIA10/AN48/RPB8/PMA10/RB8_32") (pintype "bidirectional"))
      (node (ref "IC6") (pin "P25") (pinfunction "~{CLATCH}_P25") (pintype "bidirectional"))
    )
    (net (code "320") (name "~{UART_RX}") (class "Default")
      (node (ref "IC27") (pin "7") (pinfunction "B_7") (pintype "bidirectional"))
      (node (ref "J2") (pin "2") (pinfunction "2_2") (pintype "passive"))
      (node (ref "R64") (pin "1") (pinfunction "1_1") (pintype "passive"))
    )
    (net (code "321") (name "~{UART_TX}") (class "Default")
      (node (ref "IC27") (pin "6") (pinfunction "Z_6") (pintype "bidirectional"))
      (node (ref "J2") (pin "3") (pinfunction "3_3") (pintype "passive"))
      (node (ref "R65") (pin "2") (pinfunction "2_2") (pintype "passive"))
    )
  )
)
